# 016-5_spdif-simple_main_revb_sch-pcb.net
KiCad netlist of a schematic drawn in EAGLE
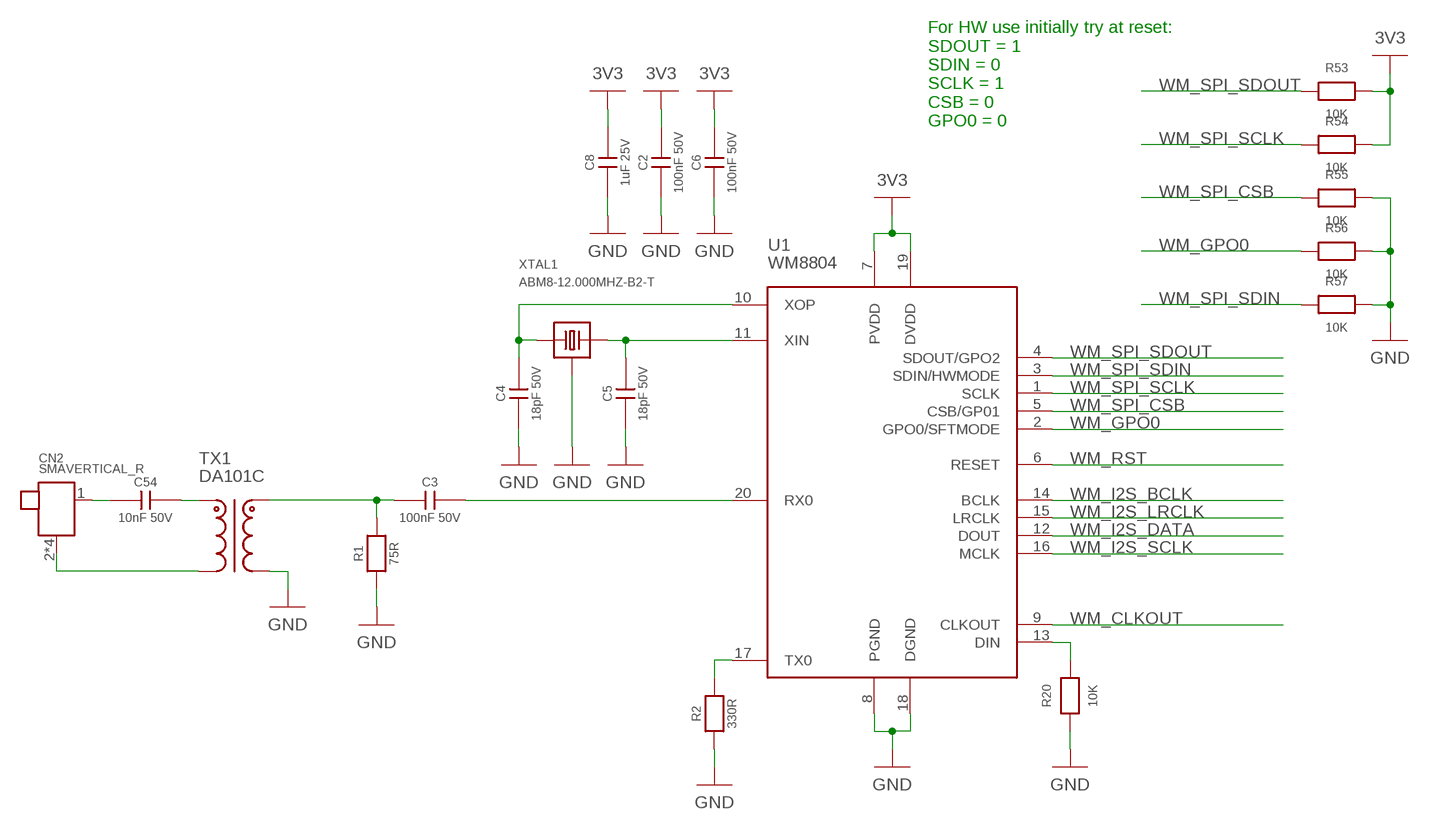
[diagram p0: schematic, sheet 1]
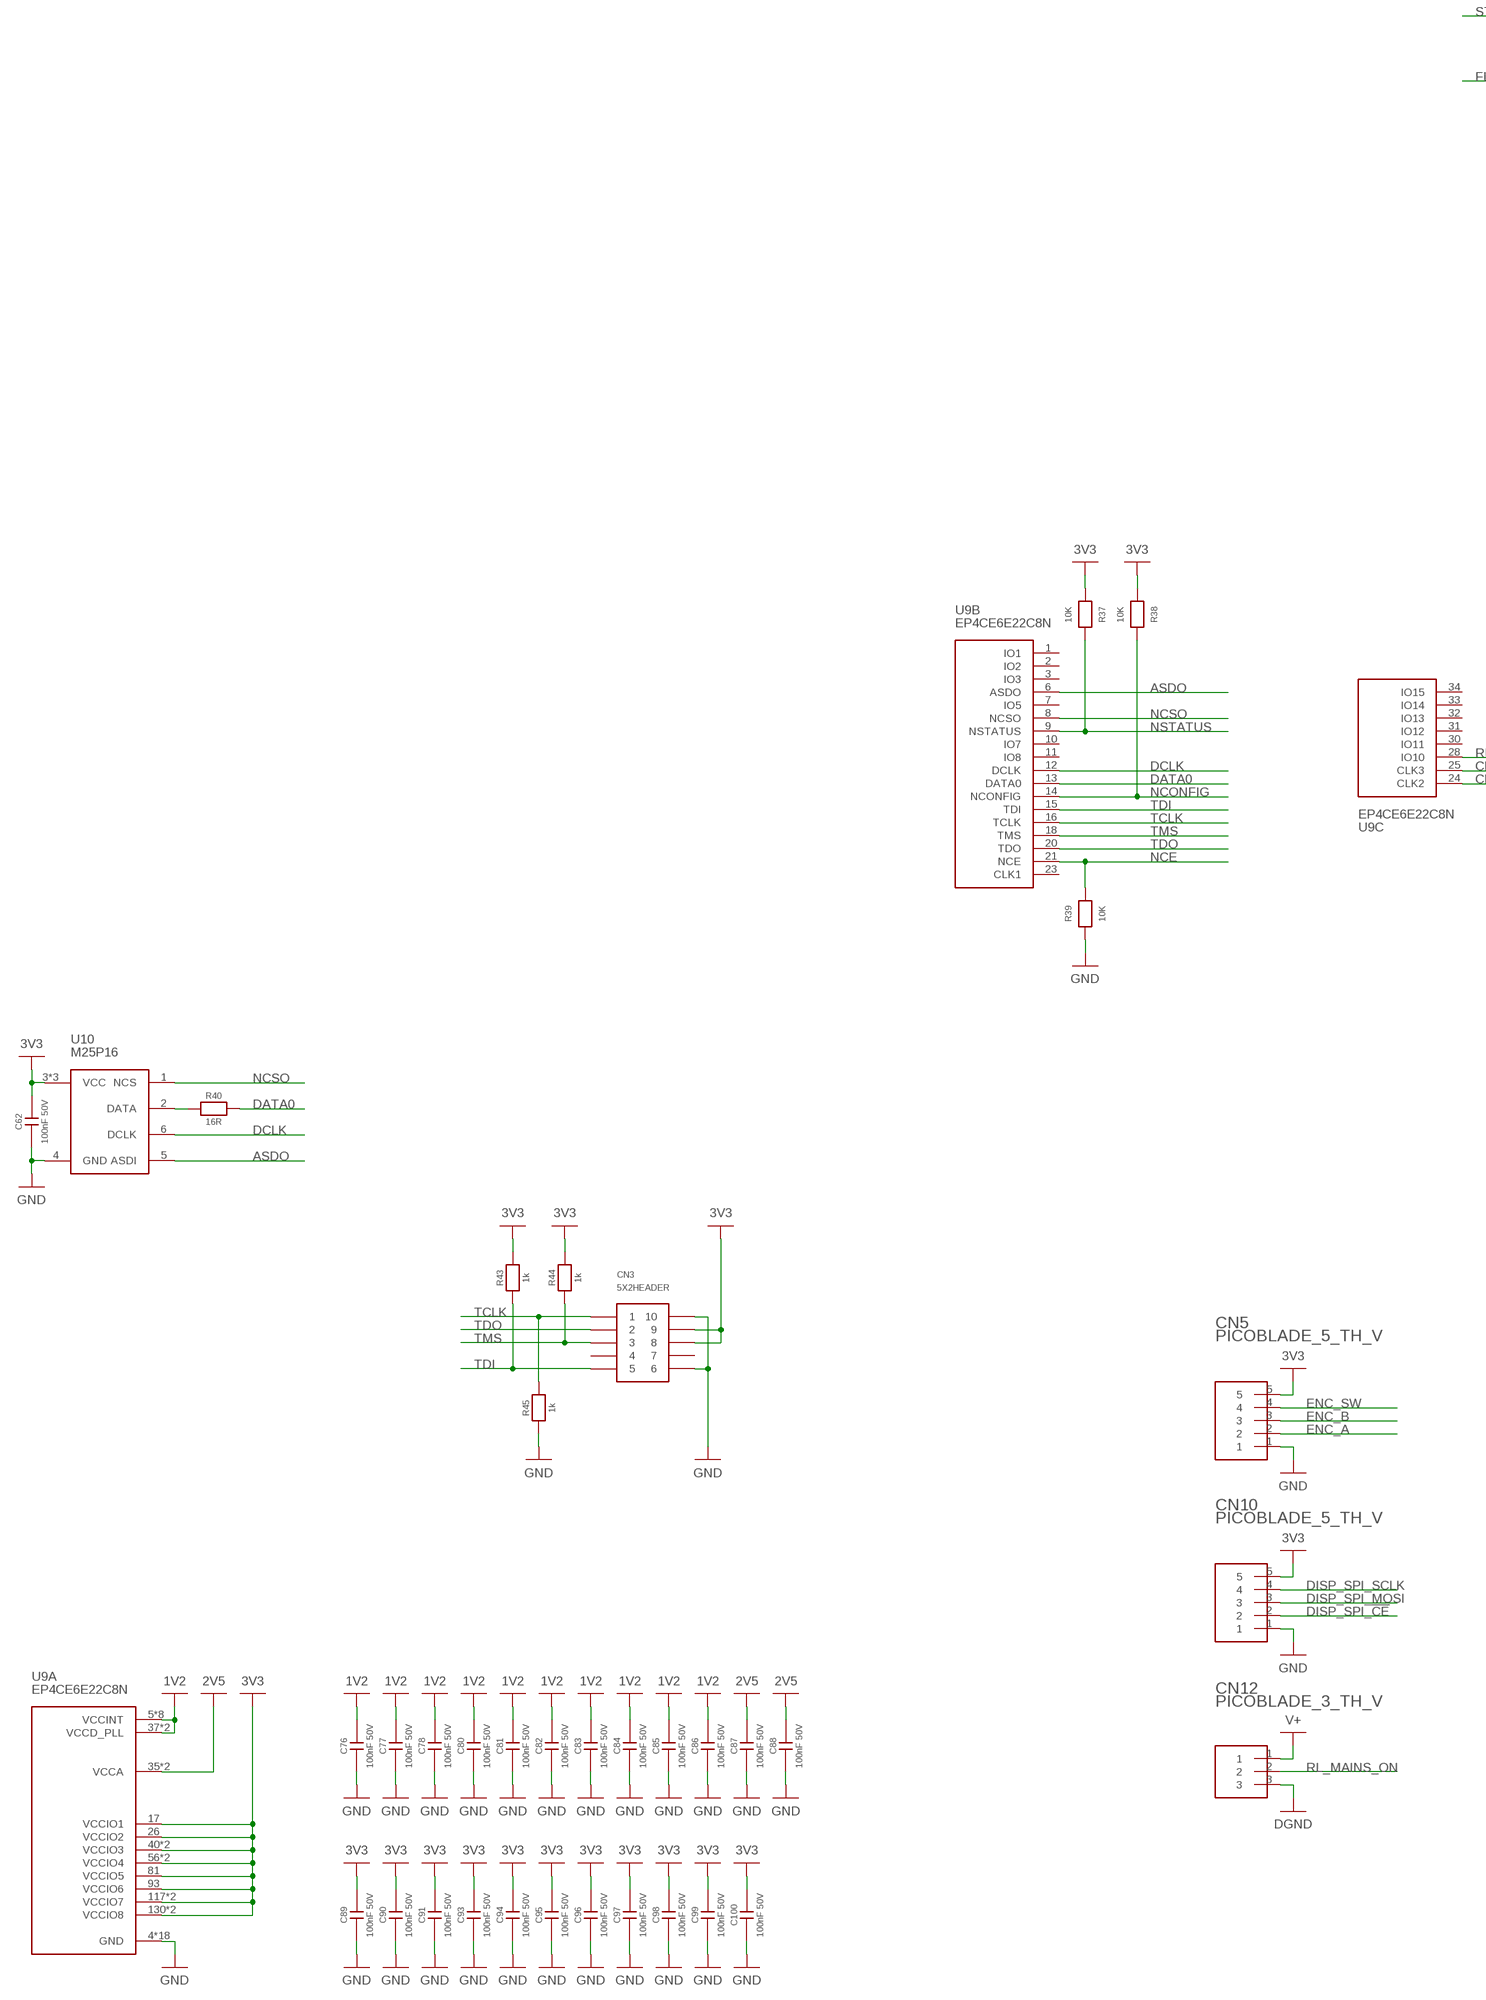
[diagram p1: schematic, sheet 2, part 1 of 2]
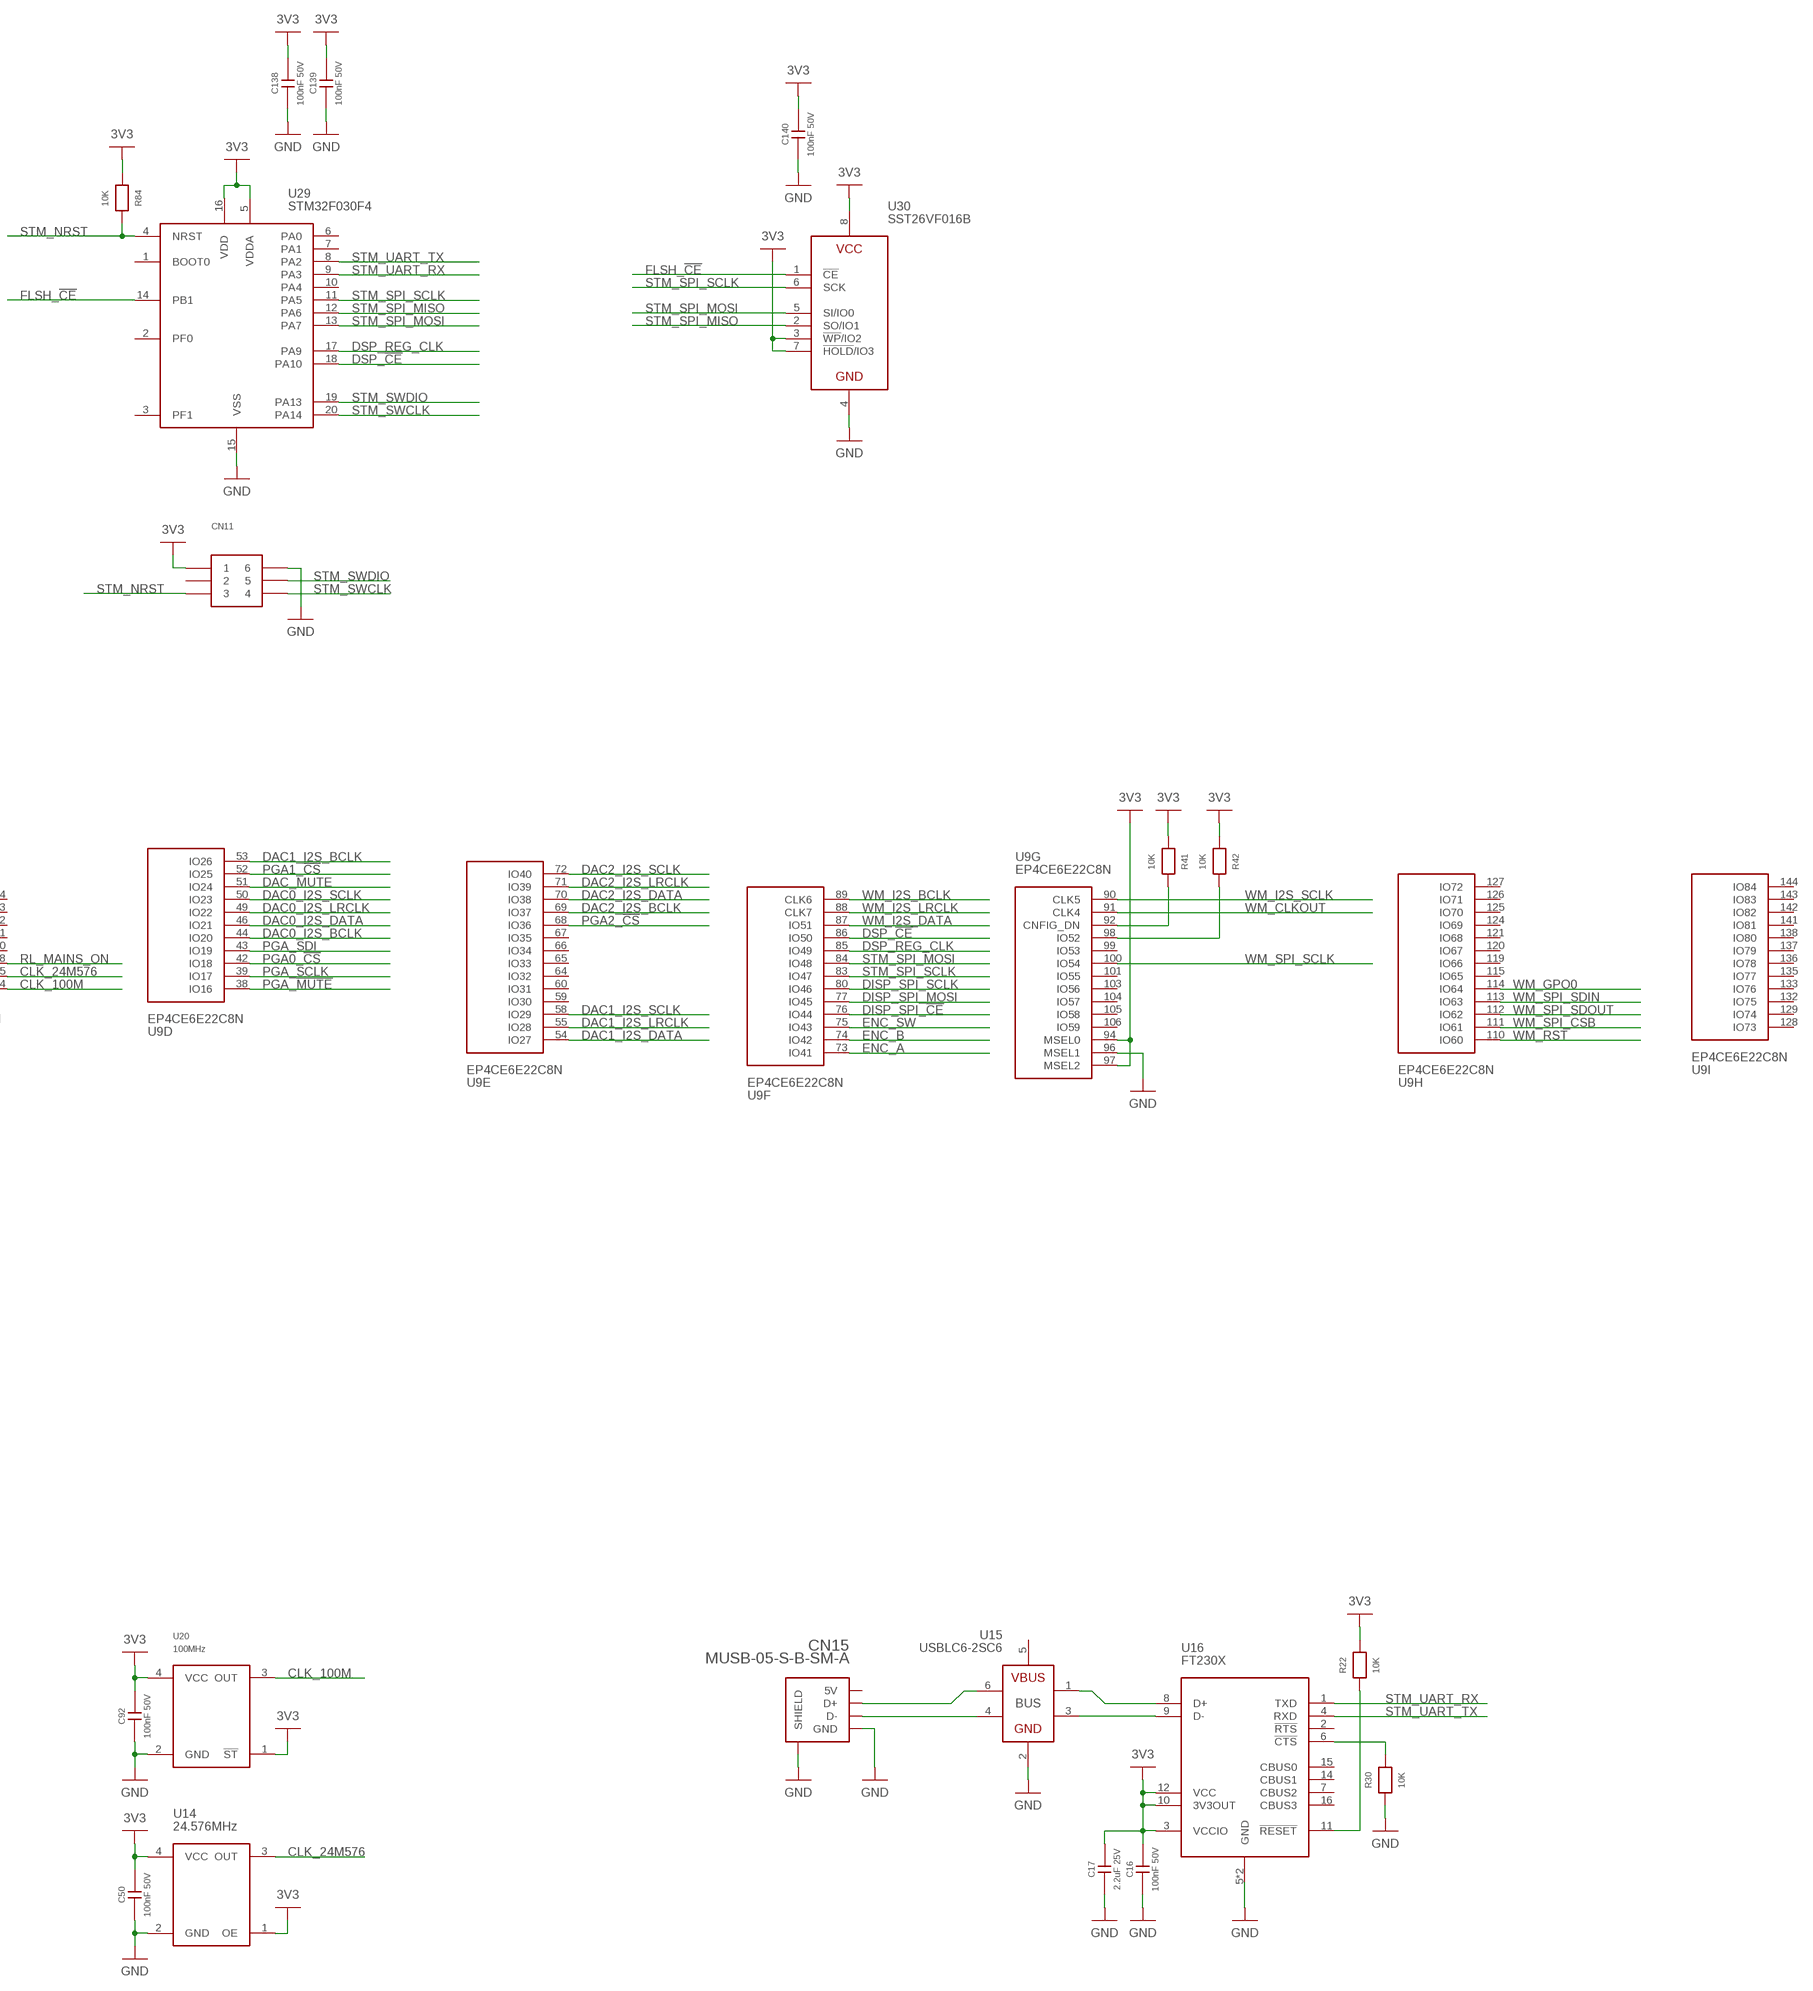
[diagram p2: schematic, sheet 2, part 2 of 2]
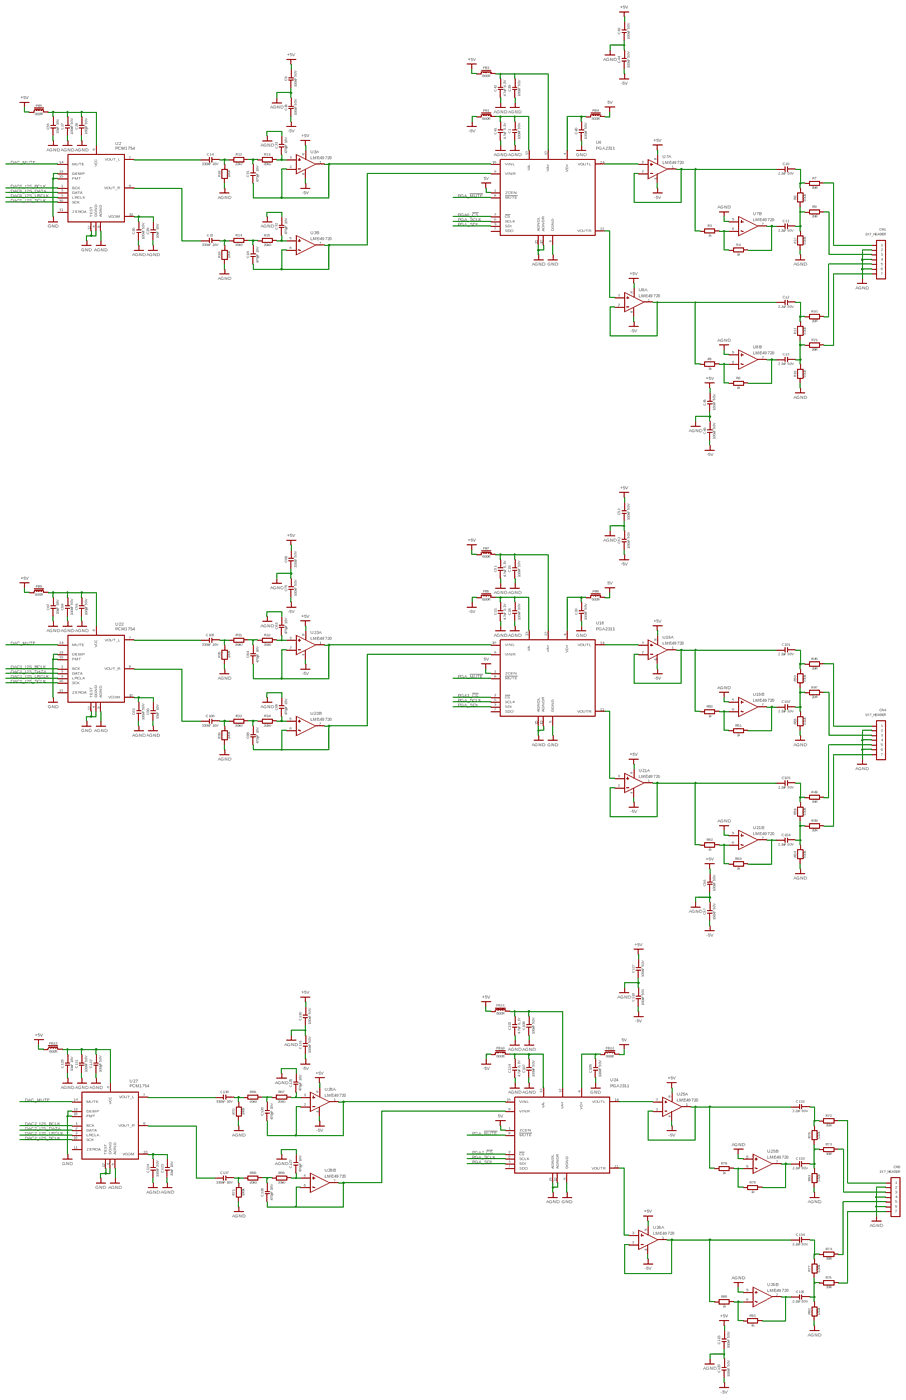
[diagram p3: schematic, sheet 3, overview]
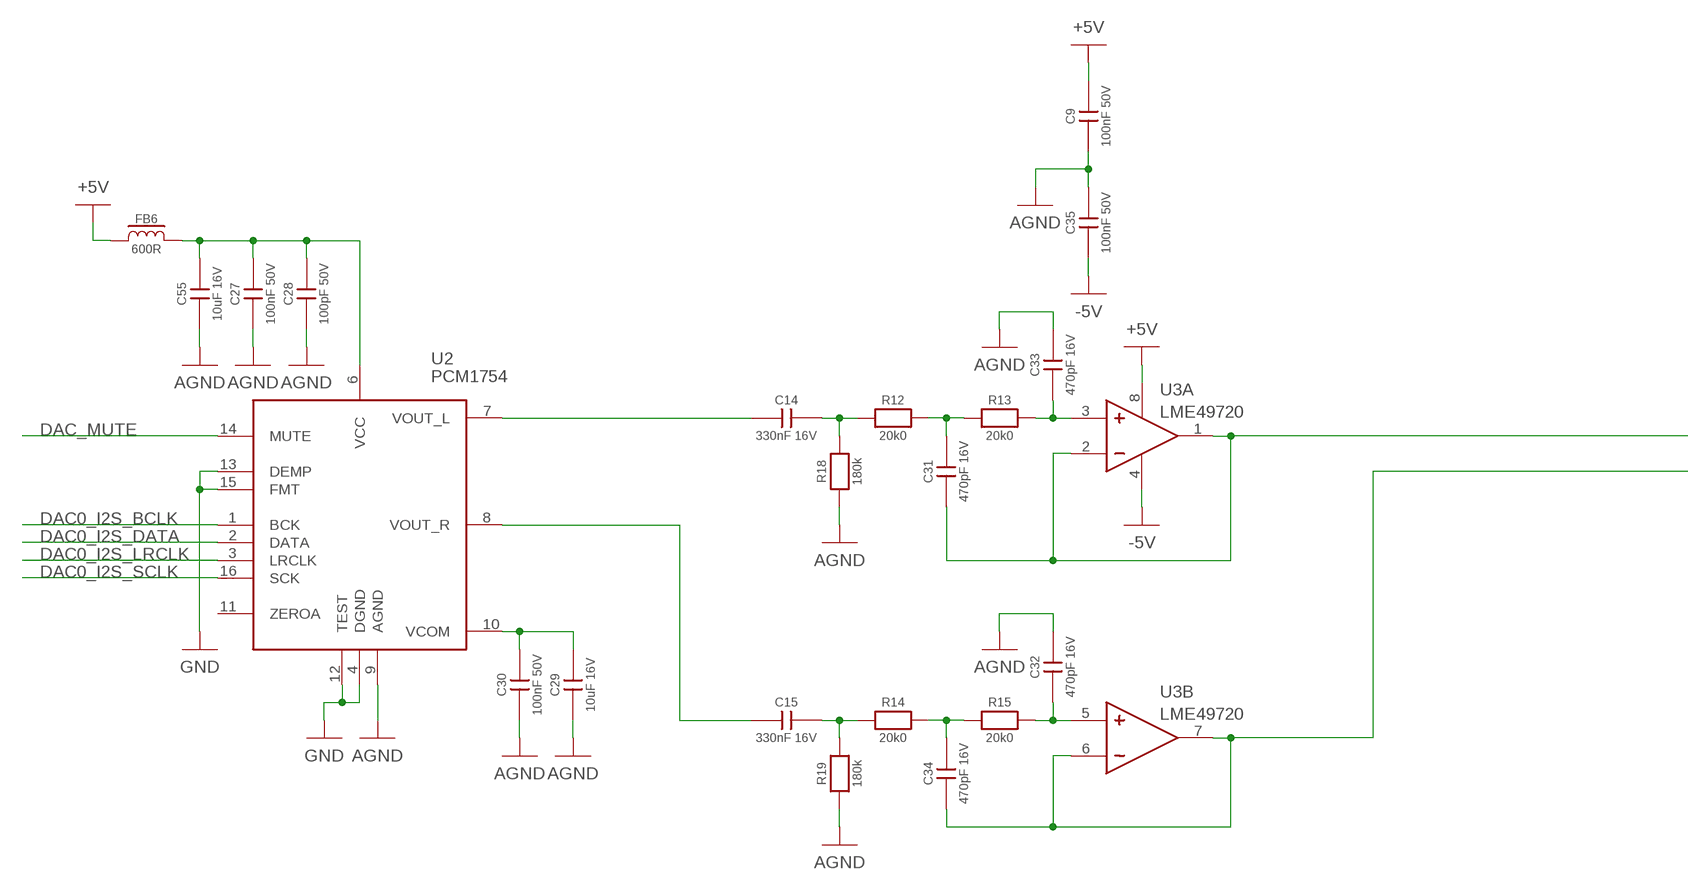
[diagram p4: schematic, sheet 3, part 1 of 4]
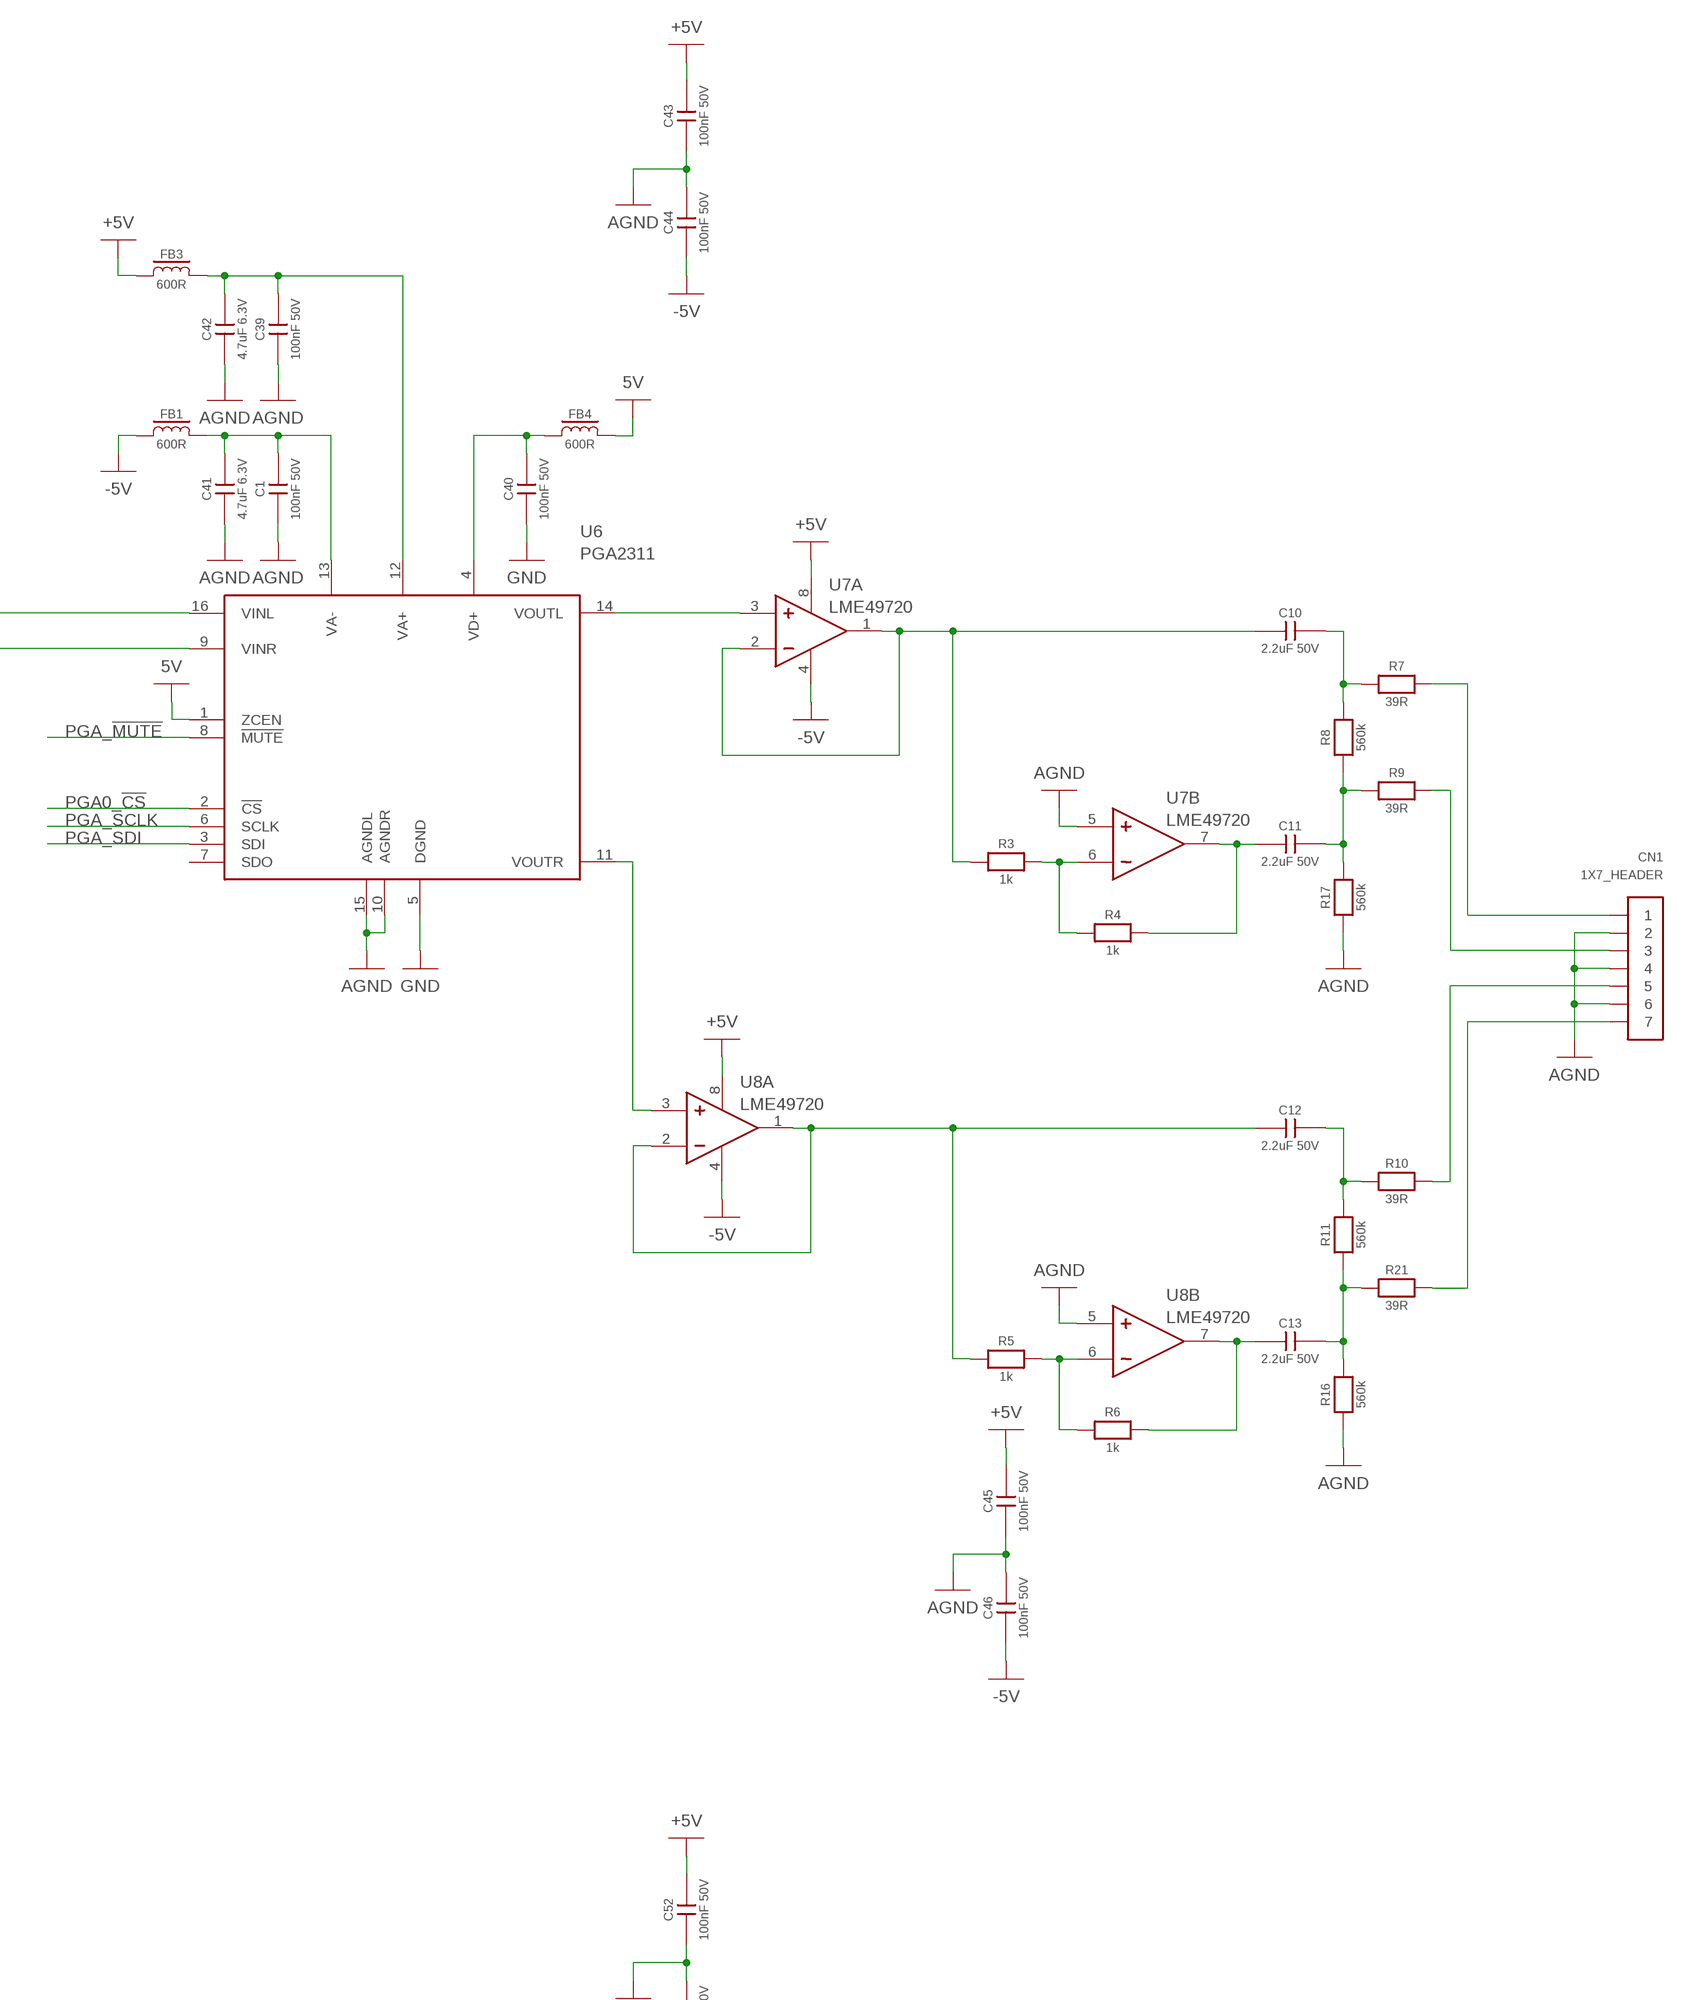
[diagram p5: schematic, sheet 3, part 2 of 4]
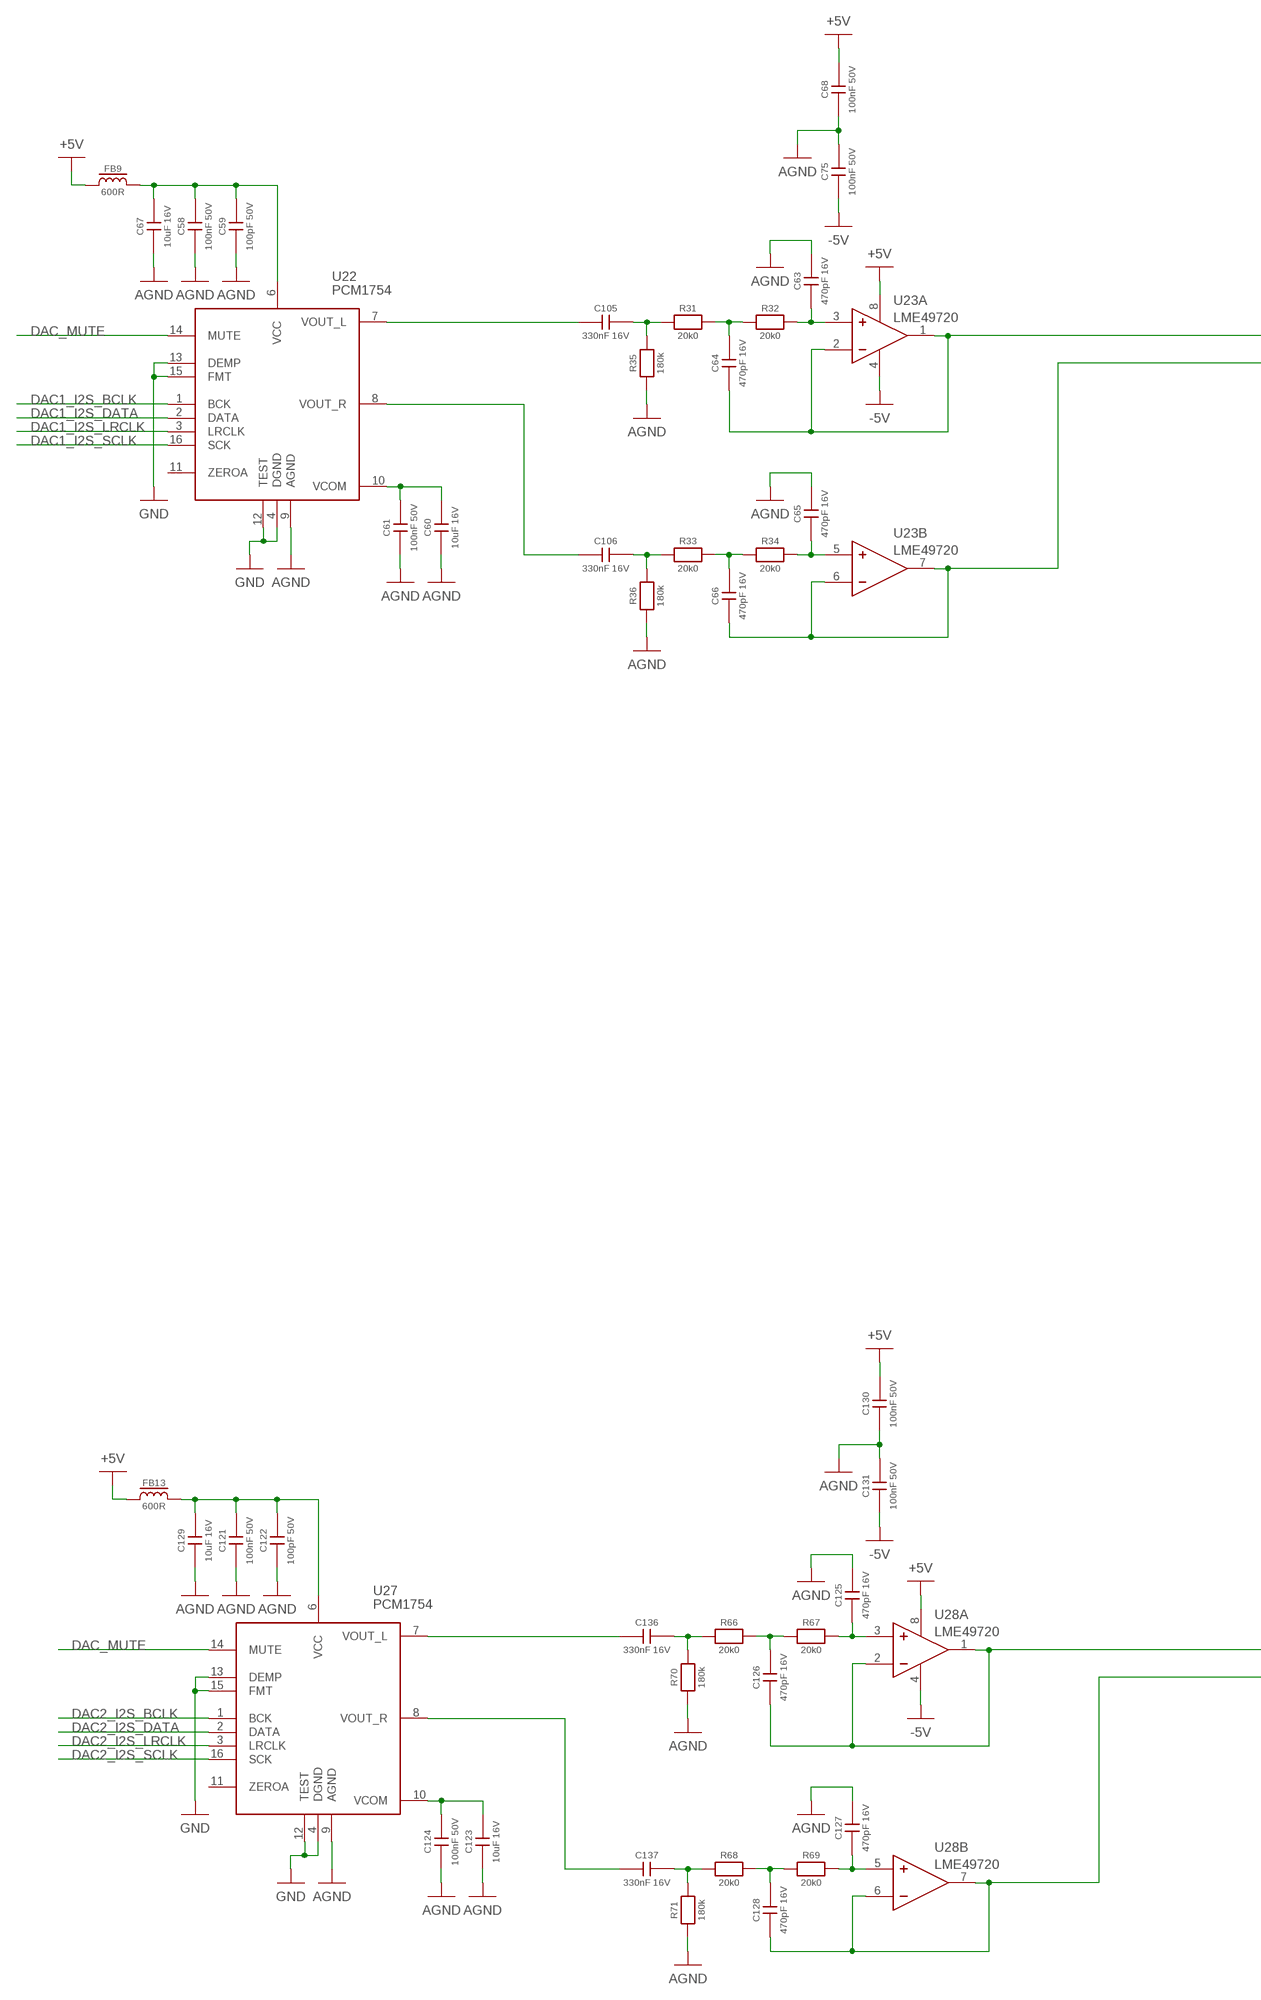
[diagram p6: schematic, sheet 3, part 3 of 4]
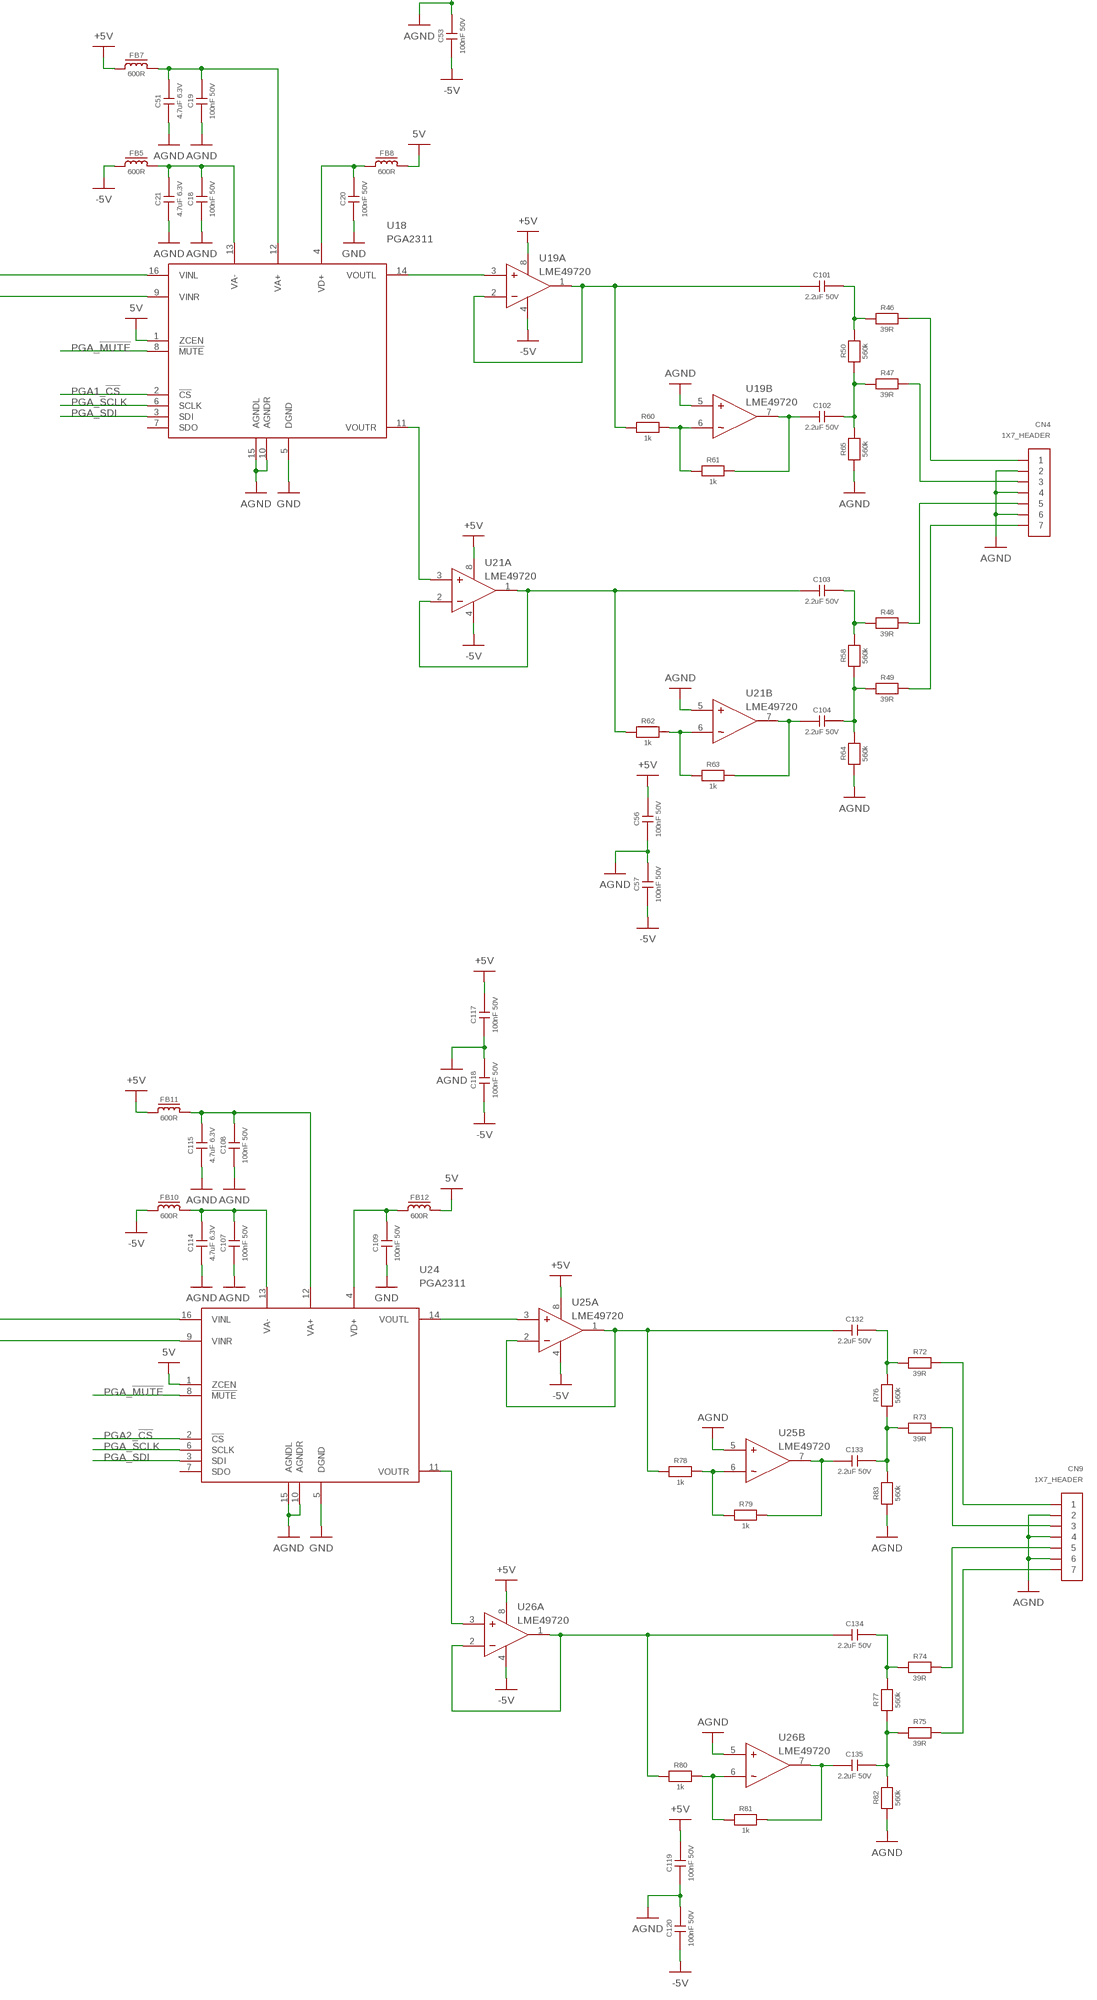
[diagram p7: schematic, sheet 3, part 4 of 4]
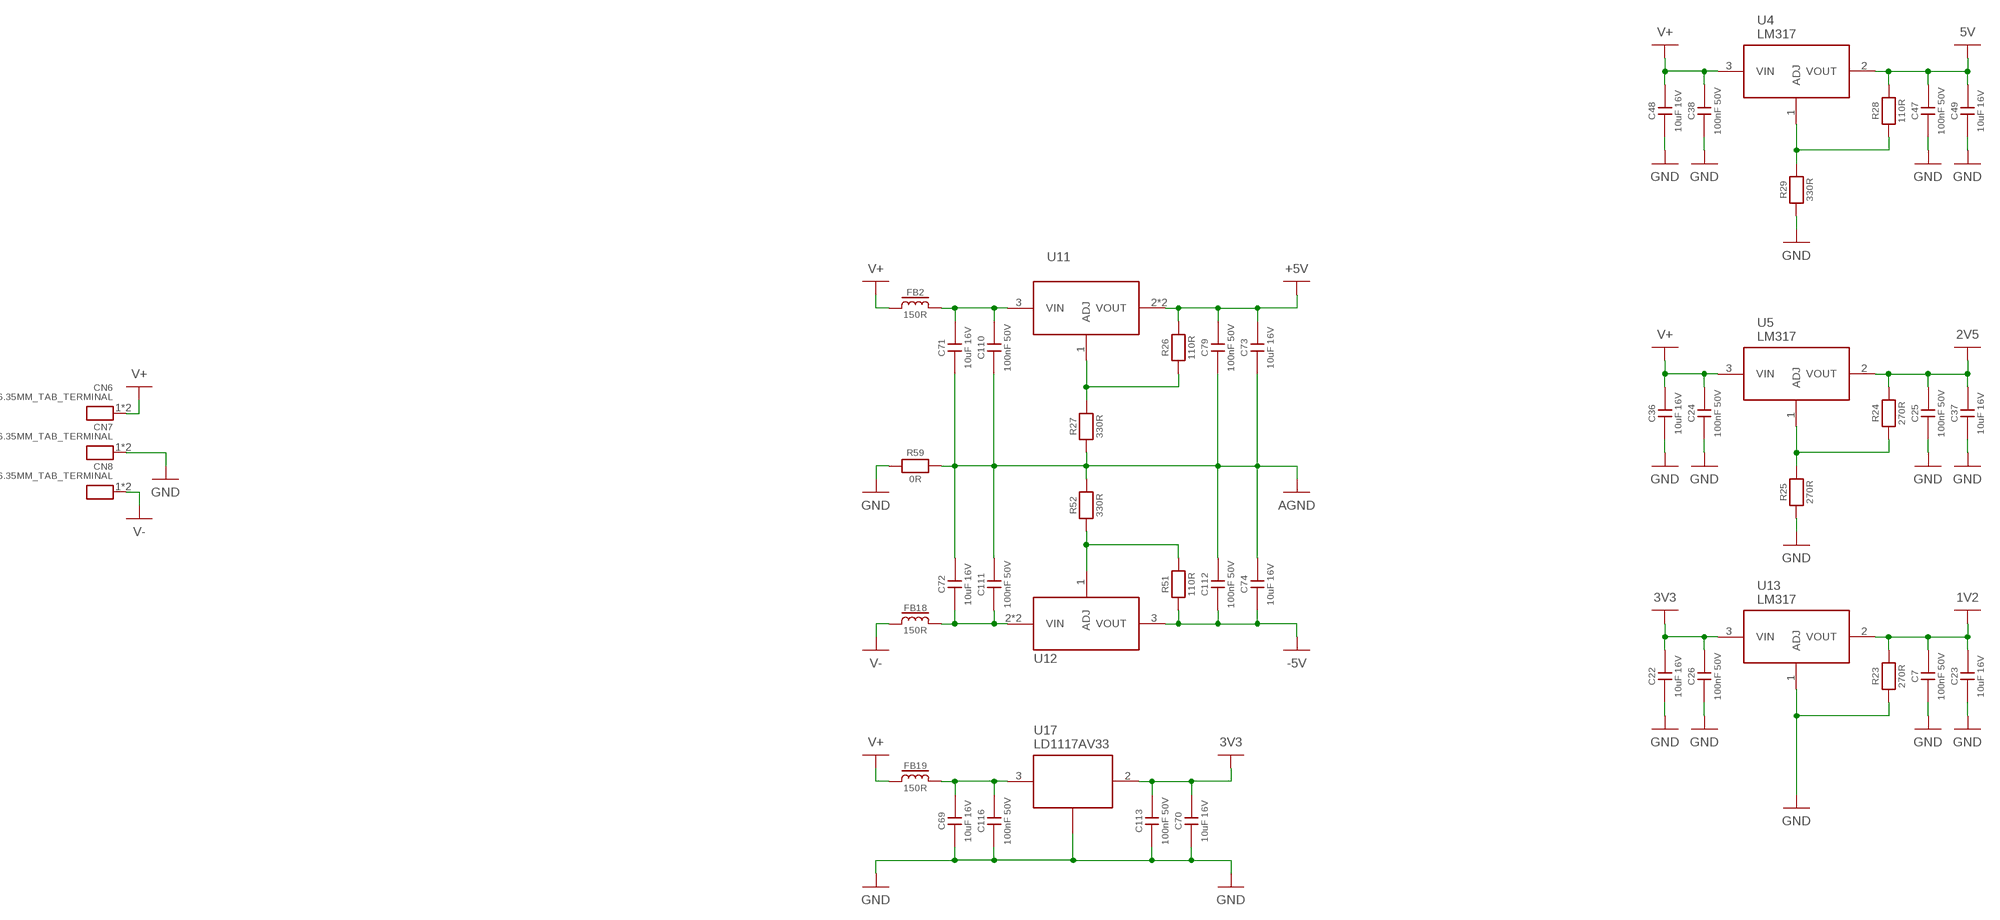
[diagram p8: schematic, sheet 4]
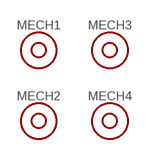
[diagram p9: schematic, sheet 5]

(export (version "E")
  (design (tool "Eeschema 10.0.6"))
  (components
    (comp (ref "C1")
      (value "100nF 50V")
      (footprint "eagle-import:0603")
      (libsource (lib "eagle-import") (part "VJ0603Y104KXACW1BC"))
    )
    (comp (ref "C9")
      (value "100nF 50V")
      (footprint "eagle-import:0603")
      (fields (field (name "FARNELL") "2407338") (field (name "PRICE_PER") "0.0085"))
      (libsource (lib "eagle-import") (part "VJ0603Y104KXACW1BC"))
    )
    (comp (ref "C10")
      (value "2.2uF 50V")
      (footprint "eagle-import:5X7.2BOX")
      (libsource (lib "eagle-import") (part "MKS2B042201F00KSSD"))
    )
    (comp (ref "C11")
      (value "2.2uF 50V")
      (footprint "eagle-import:5X7.2BOX")
      (libsource (lib "eagle-import") (part "MKS2B042201F00KSSD"))
    )
    (comp (ref "C12")
      (value "2.2uF 50V")
      (footprint "eagle-import:5X7.2BOX")
      (libsource (lib "eagle-import") (part "MKS2B042201F00KSSD"))
    )
    (comp (ref "C13")
      (value "2.2uF 50V")
      (footprint "eagle-import:5X7.2BOX")
      (libsource (lib "eagle-import") (part "MKS2B042201F00KSSD"))
    )
    (comp (ref "C14")
      (value "330nF 16V")
      (footprint "eagle-import:1206")
      (libsource (lib "eagle-import") (part "ECPU1C334MA5"))
    )
    (comp (ref "C15")
      (value "330nF 16V")
      (footprint "eagle-import:1206")
      (libsource (lib "eagle-import") (part "ECPU1C334MA5"))
    )
    (comp (ref "C18")
      (value "100nF 50V")
      (footprint "eagle-import:0603")
      (libsource (lib "eagle-import") (part "VJ0603Y104KXACW1BC"))
    )
    (comp (ref "C19")
      (value "100nF 50V")
      (footprint "eagle-import:0603")
      (libsource (lib "eagle-import") (part "VJ0603Y104KXACW1BC"))
    )
    (comp (ref "C20")
      (value "100nF 50V")
      (footprint "eagle-import:0603")
      (libsource (lib "eagle-import") (part "VJ0603Y104KXACW1BC"))
    )
    (comp (ref "C21")
      (value "4.7uF 6.3V")
      (footprint "eagle-import:0603")
      (libsource (lib "eagle-import") (part "GRM188R60J475ME19D"))
    )
    (comp (ref "C27")
      (value "100nF 50V")
      (footprint "eagle-import:0603")
      (libsource (lib "eagle-import") (part "VJ0603Y104KXACW1BC"))
    )
    (comp (ref "C28")
      (value "100pF 50V")
      (footprint "eagle-import:0603")
      (libsource (lib "eagle-import") (part "C0603C101K5GACTU"))
    )
    (comp (ref "C29")
      (value "10uF 16V")
      (footprint "eagle-import:1206")
      (libsource (lib "eagle-import") (part "MC1206B106K160CT"))
    )
    (comp (ref "C30")
      (value "100nF 50V")
      (footprint "eagle-import:0603")
      (libsource (lib "eagle-import") (part "VJ0603Y104KXACW1BC"))
    )
    (comp (ref "C31")
      (value "470pF 16V")
      (footprint "eagle-import:0603")
      (libsource (lib "eagle-import") (part "ECHU1C471GX5"))
    )
    (comp (ref "C32")
      (value "470pF 16V")
      (footprint "eagle-import:0603")
      (libsource (lib "eagle-import") (part "ECHU1C471GX5"))
    )
    (comp (ref "C33")
      (value "470pF 16V")
      (footprint "eagle-import:0603")
      (libsource (lib "eagle-import") (part "ECHU1C471GX5"))
    )
    (comp (ref "C34")
      (value "470pF 16V")
      (footprint "eagle-import:0603")
      (libsource (lib "eagle-import") (part "ECHU1C471GX5"))
    )
    (comp (ref "C35")
      (value "100nF 50V")
      (footprint "eagle-import:0603")
      (fields (field (name "FARNELL") "2407338") (field (name "PRICE_PER") "0.0085"))
      (libsource (lib "eagle-import") (part "VJ0603Y104KXACW1BC"))
    )
    (comp (ref "C39")
      (value "100nF 50V")
      (footprint "eagle-import:0603")
      (libsource (lib "eagle-import") (part "VJ0603Y104KXACW1BC"))
    )
    (comp (ref "C40")
      (value "100nF 50V")
      (footprint "eagle-import:0603")
      (libsource (lib "eagle-import") (part "VJ0603Y104KXACW1BC"))
    )
    (comp (ref "C41")
      (value "4.7uF 6.3V")
      (footprint "eagle-import:0603")
      (libsource (lib "eagle-import") (part "GRM188R60J475ME19D"))
    )
    (comp (ref "C42")
      (value "4.7uF 6.3V")
      (footprint "eagle-import:0603")
      (libsource (lib "eagle-import") (part "GRM188R60J475ME19D"))
    )
    (comp (ref "C43")
      (value "100nF 50V")
      (footprint "eagle-import:0603")
      (fields (field (name "FARNELL") "2407338") (field (name "PRICE_PER") "0.0085"))
      (libsource (lib "eagle-import") (part "VJ0603Y104KXACW1BC"))
    )
    (comp (ref "C44")
      (value "100nF 50V")
      (footprint "eagle-import:0603")
      (fields (field (name "FARNELL") "2407338") (field (name "PRICE_PER") "0.0085"))
      (libsource (lib "eagle-import") (part "VJ0603Y104KXACW1BC"))
    )
    (comp (ref "C45")
      (value "100nF 50V")
      (footprint "eagle-import:0603")
      (fields (field (name "FARNELL") "2407338") (field (name "PRICE_PER") "0.0085"))
      (libsource (lib "eagle-import") (part "VJ0603Y104KXACW1BC"))
    )
    (comp (ref "C46")
      (value "100nF 50V")
      (footprint "eagle-import:0603")
      (fields (field (name "FARNELL") "2407338") (field (name "PRICE_PER") "0.0085"))
      (libsource (lib "eagle-import") (part "VJ0603Y104KXACW1BC"))
    )
    (comp (ref "C51")
      (value "4.7uF 6.3V")
      (footprint "eagle-import:0603")
      (libsource (lib "eagle-import") (part "GRM188R60J475ME19D"))
    )
    (comp (ref "C52")
      (value "100nF 50V")
      (footprint "eagle-import:0603")
      (fields (field (name "FARNELL") "2407338") (field (name "PRICE_PER") "0.0085"))
      (libsource (lib "eagle-import") (part "VJ0603Y104KXACW1BC"))
    )
    (comp (ref "C53")
      (value "100nF 50V")
      (footprint "eagle-import:0603")
      (fields (field (name "FARNELL") "2407338") (field (name "PRICE_PER") "0.0085"))
      (libsource (lib "eagle-import") (part "VJ0603Y104KXACW1BC"))
    )
    (comp (ref "C55")
      (value "10uF 16V")
      (footprint "eagle-import:1206")
      (libsource (lib "eagle-import") (part "MC1206B106K160CT"))
    )
    (comp (ref "C56")
      (value "100nF 50V")
      (footprint "eagle-import:0603")
      (fields (field (name "FARNELL") "2407338") (field (name "PRICE_PER") "0.0085"))
      (libsource (lib "eagle-import") (part "VJ0603Y104KXACW1BC"))
    )
    (comp (ref "C57")
      (value "100nF 50V")
      (footprint "eagle-import:0603")
      (fields (field (name "FARNELL") "2407338") (field (name "PRICE_PER") "0.0085"))
      (libsource (lib "eagle-import") (part "VJ0603Y104KXACW1BC"))
    )
    (comp (ref "C58")
      (value "100nF 50V")
      (footprint "eagle-import:0603")
      (libsource (lib "eagle-import") (part "VJ0603Y104KXACW1BC"))
    )
    (comp (ref "C59")
      (value "100pF 50V")
      (footprint "eagle-import:0603")
      (libsource (lib "eagle-import") (part "C0603C101K5GACTU"))
    )
    (comp (ref "C60")
      (value "10uF 16V")
      (footprint "eagle-import:1206")
      (libsource (lib "eagle-import") (part "MC1206B106K160CT"))
    )
    (comp (ref "C61")
      (value "100nF 50V")
      (footprint "eagle-import:0603")
      (libsource (lib "eagle-import") (part "VJ0603Y104KXACW1BC"))
    )
    (comp (ref "C63")
      (value "470pF 16V")
      (footprint "eagle-import:0603")
      (libsource (lib "eagle-import") (part "ECHU1C471GX5"))
    )
    (comp (ref "C64")
      (value "470pF 16V")
      (footprint "eagle-import:0603")
      (libsource (lib "eagle-import") (part "ECHU1C471GX5"))
    )
    (comp (ref "C65")
      (value "470pF 16V")
      (footprint "eagle-import:0603")
      (libsource (lib "eagle-import") (part "ECHU1C471GX5"))
    )
    (comp (ref "C66")
      (value "470pF 16V")
      (footprint "eagle-import:0603")
      (libsource (lib "eagle-import") (part "ECHU1C471GX5"))
    )
    (comp (ref "C67")
      (value "10uF 16V")
      (footprint "eagle-import:1206")
      (libsource (lib "eagle-import") (part "MC1206B106K160CT"))
    )
    (comp (ref "C68")
      (value "100nF 50V")
      (footprint "eagle-import:0603")
      (fields (field (name "FARNELL") "2407338") (field (name "PRICE_PER") "0.0085"))
      (libsource (lib "eagle-import") (part "VJ0603Y104KXACW1BC"))
    )
    (comp (ref "C75")
      (value "100nF 50V")
      (footprint "eagle-import:0603")
      (fields (field (name "FARNELL") "2407338") (field (name "PRICE_PER") "0.0085"))
      (libsource (lib "eagle-import") (part "VJ0603Y104KXACW1BC"))
    )
    (comp (ref "C101")
      (value "2.2uF 50V")
      (footprint "eagle-import:5X7.2BOX")
      (libsource (lib "eagle-import") (part "MKS2B042201F00KSSD"))
    )
    (comp (ref "C102")
      (value "2.2uF 50V")
      (footprint "eagle-import:5X7.2BOX")
      (libsource (lib "eagle-import") (part "MKS2B042201F00KSSD"))
    )
    (comp (ref "C103")
      (value "2.2uF 50V")
      (footprint "eagle-import:5X7.2BOX")
      (libsource (lib "eagle-import") (part "MKS2B042201F00KSSD"))
    )
    (comp (ref "C104")
      (value "2.2uF 50V")
      (footprint "eagle-import:5X7.2BOX")
      (libsource (lib "eagle-import") (part "MKS2B042201F00KSSD"))
    )
    (comp (ref "C105")
      (value "330nF 16V")
      (footprint "eagle-import:1206")
      (libsource (lib "eagle-import") (part "ECPU1C334MA5"))
    )
    (comp (ref "C106")
      (value "330nF 16V")
      (footprint "eagle-import:1206")
      (libsource (lib "eagle-import") (part "ECPU1C334MA5"))
    )
    (comp (ref "C107")
      (value "100nF 50V")
      (footprint "eagle-import:0603")
      (libsource (lib "eagle-import") (part "VJ0603Y104KXACW1BC"))
    )
    (comp (ref "C108")
      (value "100nF 50V")
      (footprint "eagle-import:0603")
      (libsource (lib "eagle-import") (part "VJ0603Y104KXACW1BC"))
    )
    (comp (ref "C109")
      (value "100nF 50V")
      (footprint "eagle-import:0603")
      (libsource (lib "eagle-import") (part "VJ0603Y104KXACW1BC"))
    )
    (comp (ref "C114")
      (value "4.7uF 6.3V")
      (footprint "eagle-import:0603")
      (libsource (lib "eagle-import") (part "GRM188R60J475ME19D"))
    )
    (comp (ref "C115")
      (value "4.7uF 6.3V")
      (footprint "eagle-import:0603")
      (libsource (lib "eagle-import") (part "GRM188R60J475ME19D"))
    )
    (comp (ref "C117")
      (value "100nF 50V")
      (footprint "eagle-import:0603")
      (fields (field (name "FARNELL") "2407338") (field (name "PRICE_PER") "0.0085"))
      (libsource (lib "eagle-import") (part "VJ0603Y104KXACW1BC"))
    )
    (comp (ref "C118")
      (value "100nF 50V")
      (footprint "eagle-import:0603")
      (fields (field (name "FARNELL") "2407338") (field (name "PRICE_PER") "0.0085"))
      (libsource (lib "eagle-import") (part "VJ0603Y104KXACW1BC"))
    )
    (comp (ref "C119")
      (value "100nF 50V")
      (footprint "eagle-import:0603")
      (fields (field (name "FARNELL") "2407338") (field (name "PRICE_PER") "0.0085"))
      (libsource (lib "eagle-import") (part "VJ0603Y104KXACW1BC"))
    )
    (comp (ref "C120")
      (value "100nF 50V")
      (footprint "eagle-import:0603")
      (fields (field (name "FARNELL") "2407338") (field (name "PRICE_PER") "0.0085"))
      (libsource (lib "eagle-import") (part "VJ0603Y104KXACW1BC"))
    )
    (comp (ref "C121")
      (value "100nF 50V")
      (footprint "eagle-import:0603")
      (libsource (lib "eagle-import") (part "VJ0603Y104KXACW1BC"))
    )
    (comp (ref "C122")
      (value "100pF 50V")
      (footprint "eagle-import:0603")
      (libsource (lib "eagle-import") (part "C0603C101K5GACTU"))
    )
    (comp (ref "C123")
      (value "10uF 16V")
      (footprint "eagle-import:1206")
      (libsource (lib "eagle-import") (part "MC1206B106K160CT"))
    )
    (comp (ref "C124")
      (value "100nF 50V")
      (footprint "eagle-import:0603")
      (libsource (lib "eagle-import") (part "VJ0603Y104KXACW1BC"))
    )
    (comp (ref "C125")
      (value "470pF 16V")
      (footprint "eagle-import:0603")
      (libsource (lib "eagle-import") (part "ECHU1C471GX5"))
    )
    (comp (ref "C126")
      (value "470pF 16V")
      (footprint "eagle-import:0603")
      (libsource (lib "eagle-import") (part "ECHU1C471GX5"))
    )
    (comp (ref "C127")
      (value "470pF 16V")
      (footprint "eagle-import:0603")
      (libsource (lib "eagle-import") (part "ECHU1C471GX5"))
    )
    (comp (ref "C128")
      (value "470pF 16V")
      (footprint "eagle-import:0603")
      (libsource (lib "eagle-import") (part "ECHU1C471GX5"))
    )
    (comp (ref "C129")
      (value "10uF 16V")
      (footprint "eagle-import:1206")
      (libsource (lib "eagle-import") (part "MC1206B106K160CT"))
    )
    (comp (ref "C130")
      (value "100nF 50V")
      (footprint "eagle-import:0603")
      (fields (field (name "FARNELL") "2407338") (field (name "PRICE_PER") "0.0085"))
      (libsource (lib "eagle-import") (part "VJ0603Y104KXACW1BC"))
    )
    (comp (ref "C131")
      (value "100nF 50V")
      (footprint "eagle-import:0603")
      (fields (field (name "FARNELL") "2407338") (field (name "PRICE_PER") "0.0085"))
      (libsource (lib "eagle-import") (part "VJ0603Y104KXACW1BC"))
    )
    (comp (ref "C132")
      (value "2.2uF 50V")
      (footprint "eagle-import:5X7.2BOX")
      (libsource (lib "eagle-import") (part "MKS2B042201F00KSSD"))
    )
    (comp (ref "C133")
      (value "2.2uF 50V")
      (footprint "eagle-import:5X7.2BOX")
      (libsource (lib "eagle-import") (part "MKS2B042201F00KSSD"))
    )
    (comp (ref "C134")
      (value "2.2uF 50V")
      (footprint "eagle-import:5X7.2BOX")
      (libsource (lib "eagle-import") (part "MKS2B042201F00KSSD"))
    )
    (comp (ref "C135")
      (value "2.2uF 50V")
      (footprint "eagle-import:5X7.2BOX")
      (libsource (lib "eagle-import") (part "MKS2B042201F00KSSD"))
    )
    (comp (ref "C136")
      (value "330nF 16V")
      (footprint "eagle-import:1206")
      (libsource (lib "eagle-import") (part "ECPU1C334MA5"))
    )
    (comp (ref "C137")
      (value "330nF 16V")
      (footprint "eagle-import:1206")
      (libsource (lib "eagle-import") (part "ECPU1C334MA5"))
    )
    (comp (ref "CN1")
      (value "1X7_HEADER")
      (footprint "eagle-import:7PIN_HEADER")
      (libsource (lib "eagle-import") (part "1X7_HEADER"))
    )
    (comp (ref "CN4")
      (value "1X7_HEADER")
      (footprint "eagle-import:7PIN_HEADER")
      (libsource (lib "eagle-import") (part "1X7_HEADER"))
    )
    (comp (ref "CN9")
      (value "1X7_HEADER")
      (footprint "eagle-import:7PIN_HEADER")
      (libsource (lib "eagle-import") (part "1X7_HEADER"))
    )
    (comp (ref "FB1")
      (value "600R")
      (footprint "eagle-import:0603")
      (libsource (lib "eagle-import") (part "742792651"))
    )
    (comp (ref "FB3")
      (value "600R")
      (footprint "eagle-import:0603")
      (libsource (lib "eagle-import") (part "742792651"))
    )
    (comp (ref "FB4")
      (value "600R")
      (footprint "eagle-import:0603")
      (fields (field (name "FARNELL") "1635706"))
      (libsource (lib "eagle-import") (part "742792651"))
    )
    (comp (ref "FB5")
      (value "600R")
      (footprint "eagle-import:0603")
      (libsource (lib "eagle-import") (part "742792651"))
    )
    (comp (ref "FB6")
      (value "600R")
      (footprint "eagle-import:0603")
      (libsource (lib "eagle-import") (part "742792651"))
    )
    (comp (ref "FB7")
      (value "600R")
      (footprint "eagle-import:0603")
      (libsource (lib "eagle-import") (part "742792651"))
    )
    (comp (ref "FB8")
      (value "600R")
      (footprint "eagle-import:0603")
      (fields (field (name "FARNELL") "1635706"))
      (libsource (lib "eagle-import") (part "742792651"))
    )
    (comp (ref "FB9")
      (value "600R")
      (footprint "eagle-import:0603")
      (libsource (lib "eagle-import") (part "742792651"))
    )
    (comp (ref "FB10")
      (value "600R")
      (footprint "eagle-import:0603")
      (libsource (lib "eagle-import") (part "742792651"))
    )
    (comp (ref "FB11")
      (value "600R")
      (footprint "eagle-import:0603")
      (libsource (lib "eagle-import") (part "742792651"))
    )
    (comp (ref "FB12")
      (value "600R")
      (footprint "eagle-import:0603")
      (fields (field (name "FARNELL") "1635706"))
      (libsource (lib "eagle-import") (part "742792651"))
    )
    (comp (ref "FB13")
      (value "600R")
      (footprint "eagle-import:0603")
      (libsource (lib "eagle-import") (part "742792651"))
    )
    (comp (ref "R3")
      (value "1k")
      (footprint "eagle-import:0603")
      (libsource (lib "eagle-import") (part "CRCW06031K00FKEA"))
    )
    (comp (ref "R4")
      (value "1k")
      (footprint "eagle-import:0603")
      (libsource (lib "eagle-import") (part "CRCW06031K00FKEA"))
    )
    (comp (ref "R5")
      (value "1k")
      (footprint "eagle-import:0603")
      (libsource (lib "eagle-import") (part "CRCW06031K00FKEA"))
    )
    (comp (ref "R6")
      (value "1k")
      (footprint "eagle-import:0603")
      (libsource (lib "eagle-import") (part "CRCW06031K00FKEA"))
    )
    (comp (ref "R7")
      (value "39R")
      (footprint "eagle-import:0603")
      (libsource (lib "eagle-import") (part "CRCW060339R0FKEA"))
    )
    (comp (ref "R8")
      (value "560k")
      (footprint "eagle-import:0603")
      (libsource (lib "eagle-import") (part "CRCW0603560KFKEA"))
    )
    (comp (ref "R9")
      (value "39R")
      (footprint "eagle-import:0603")
      (libsource (lib "eagle-import") (part "CRCW060339R0FKEA"))
    )
    (comp (ref "R10")
      (value "39R")
      (footprint "eagle-import:0603")
      (libsource (lib "eagle-import") (part "CRCW060339R0FKEA"))
    )
    (comp (ref "R11")
      (value "560k")
      (footprint "eagle-import:0603")
      (libsource (lib "eagle-import") (part "CRCW0603560KFKEA"))
    )
    (comp (ref "R12")
      (value "20k0")
      (footprint "eagle-import:0603")
      (libsource (lib "eagle-import") (part "CRCW060320K0FKEA"))
    )
    (comp (ref "R13")
      (value "20k0")
      (footprint "eagle-import:0603")
      (libsource (lib "eagle-import") (part "CRCW060320K0FKEA"))
    )
    (comp (ref "R14")
      (value "20k0")
      (footprint "eagle-import:0603")
      (libsource (lib "eagle-import") (part "CRCW060320K0FKEA"))
    )
    (comp (ref "R15")
      (value "20k0")
      (footprint "eagle-import:0603")
      (libsource (lib "eagle-import") (part "CRCW060320K0FKEA"))
    )
    (comp (ref "R16")
      (value "560k")
      (footprint "eagle-import:0603")
      (libsource (lib "eagle-import") (part "CRCW0603560KFKEA"))
    )
    (comp (ref "R17")
      (value "560k")
      (footprint "eagle-import:0603")
      (libsource (lib "eagle-import") (part "CRCW0603560KFKEA"))
    )
    (comp (ref "R18")
      (value "180k")
      (footprint "eagle-import:0603")
      (libsource (lib "eagle-import") (part "CRCW0603180KFKEA"))
    )
    (comp (ref "R19")
      (value "180k")
      (footprint "eagle-import:0603")
      (libsource (lib "eagle-import") (part "CRCW0603180KFKEA"))
    )
    (comp (ref "R21")
      (value "39R")
      (footprint "eagle-import:0603")
      (libsource (lib "eagle-import") (part "CRCW060339R0FKEA"))
    )
    (comp (ref "R31")
      (value "20k0")
      (footprint "eagle-import:0603")
      (libsource (lib "eagle-import") (part "CRCW060320K0FKEA"))
    )
    (comp (ref "R32")
      (value "20k0")
      (footprint "eagle-import:0603")
      (libsource (lib "eagle-import") (part "CRCW060320K0FKEA"))
    )
    (comp (ref "R33")
      (value "20k0")
      (footprint "eagle-import:0603")
      (libsource (lib "eagle-import") (part "CRCW060320K0FKEA"))
    )
    (comp (ref "R34")
      (value "20k0")
      (footprint "eagle-import:0603")
      (libsource (lib "eagle-import") (part "CRCW060320K0FKEA"))
    )
    (comp (ref "R35")
      (value "180k")
      (footprint "eagle-import:0603")
      (libsource (lib "eagle-import") (part "CRCW0603180KFKEA"))
    )
    (comp (ref "R36")
      (value "180k")
      (footprint "eagle-import:0603")
      (libsource (lib "eagle-import") (part "CRCW0603180KFKEA"))
    )
    (comp (ref "R46")
      (value "39R")
      (footprint "eagle-import:0603")
      (libsource (lib "eagle-import") (part "CRCW060339R0FKEA"))
    )
    (comp (ref "R47")
      (value "39R")
      (footprint "eagle-import:0603")
      (libsource (lib "eagle-import") (part "CRCW060339R0FKEA"))
    )
    (comp (ref "R48")
      (value "39R")
      (footprint "eagle-import:0603")
      (libsource (lib "eagle-import") (part "CRCW060339R0FKEA"))
    )
    (comp (ref "R49")
      (value "39R")
      (footprint "eagle-import:0603")
      (libsource (lib "eagle-import") (part "CRCW060339R0FKEA"))
    )
    (comp (ref "R50")
      (value "560k")
      (footprint "eagle-import:0603")
      (libsource (lib "eagle-import") (part "CRCW0603560KFKEA"))
    )
    (comp (ref "R58")
      (value "560k")
      (footprint "eagle-import:0603")
      (libsource (lib "eagle-import") (part "CRCW0603560KFKEA"))
    )
    (comp (ref "R60")
      (value "1k")
      (footprint "eagle-import:0603")
      (libsource (lib "eagle-import") (part "CRCW06031K00FKEA"))
    )
    (comp (ref "R61")
      (value "1k")
      (footprint "eagle-import:0603")
      (libsource (lib "eagle-import") (part "CRCW06031K00FKEA"))
    )
    (comp (ref "R62")
      (value "1k")
      (footprint "eagle-import:0603")
      (libsource (lib "eagle-import") (part "CRCW06031K00FKEA"))
    )
    (comp (ref "R63")
      (value "1k")
      (footprint "eagle-import:0603")
      (libsource (lib "eagle-import") (part "CRCW06031K00FKEA"))
    )
    (comp (ref "R64")
      (value "560k")
      (footprint "eagle-import:0603")
      (libsource (lib "eagle-import") (part "CRCW0603560KFKEA"))
    )
    (comp (ref "R65")
      (value "560k")
      (footprint "eagle-import:0603")
      (libsource (lib "eagle-import") (part "CRCW0603560KFKEA"))
    )
    (comp (ref "R66")
      (value "20k0")
      (footprint "eagle-import:0603")
      (libsource (lib "eagle-import") (part "CRCW060320K0FKEA"))
    )
    (comp (ref "R67")
      (value "20k0")
      (footprint "eagle-import:0603")
      (libsource (lib "eagle-import") (part "CRCW060320K0FKEA"))
    )
    (comp (ref "R68")
      (value "20k0")
      (footprint "eagle-import:0603")
      (libsource (lib "eagle-import") (part "CRCW060320K0FKEA"))
    )
    (comp (ref "R69")
      (value "20k0")
      (footprint "eagle-import:0603")
      (libsource (lib "eagle-import") (part "CRCW060320K0FKEA"))
    )
    (comp (ref "R70")
      (value "180k")
      (footprint "eagle-import:0603")
      (libsource (lib "eagle-import") (part "CRCW0603180KFKEA"))
    )
    (comp (ref "R71")
      (value "180k")
      (footprint "eagle-import:0603")
      (libsource (lib "eagle-import") (part "CRCW0603180KFKEA"))
    )
    (comp (ref "R72")
      (value "39R")
      (footprint "eagle-import:0603")
      (libsource (lib "eagle-import") (part "CRCW060339R0FKEA"))
    )
    (comp (ref "R73")
      (value "39R")
      (footprint "eagle-import:0603")
      (libsource (lib "eagle-import") (part "CRCW060339R0FKEA"))
    )
    (comp (ref "R74")
      (value "39R")
      (footprint "eagle-import:0603")
      (libsource (lib "eagle-import") (part "CRCW060339R0FKEA"))
    )
    (comp (ref "R75")
      (value "39R")
      (footprint "eagle-import:0603")
      (libsource (lib "eagle-import") (part "CRCW060339R0FKEA"))
    )
    (comp (ref "R76")
      (value "560k")
      (footprint "eagle-import:0603")
      (libsource (lib "eagle-import") (part "CRCW0603560KFKEA"))
    )
    (comp (ref "R77")
      (value "560k")
      (footprint "eagle-import:0603")
      (libsource (lib "eagle-import") (part "CRCW0603560KFKEA"))
    )
    (comp (ref "R78")
      (value "1k")
      (footprint "eagle-import:0603")
      (libsource (lib "eagle-import") (part "CRCW06031K00FKEA"))
    )
    (comp (ref "R79")
      (value "1k")
      (footprint "eagle-import:0603")
      (libsource (lib "eagle-import") (part "CRCW06031K00FKEA"))
    )
    (comp (ref "R80")
      (value "1k")
      (footprint "eagle-import:0603")
      (libsource (lib "eagle-import") (part "CRCW06031K00FKEA"))
    )
    (comp (ref "R81")
      (value "1k")
      (footprint "eagle-import:0603")
      (libsource (lib "eagle-import") (part "CRCW06031K00FKEA"))
    )
    (comp (ref "R82")
      (value "560k")
      (footprint "eagle-import:0603")
      (libsource (lib "eagle-import") (part "CRCW0603560KFKEA"))
    )
    (comp (ref "R83")
      (value "560k")
      (footprint "eagle-import:0603")
      (libsource (lib "eagle-import") (part "CRCW0603560KFKEA"))
    )
    (comp (ref "U2")
      (value "PCM1754")
      (footprint "eagle-import:SSOP16-4MM@1")
      (libsource (lib "eagle-import") (part "PCM1754"))
    )
    (comp (ref "U3")
      (value "LME49720")
      (footprint "eagle-import:SO8")
      (libsource (lib "eagle-import") (part "LME49720MA/NOPB"))
    )
    (comp (ref "U6")
      (value "PGA2311")
      (footprint "eagle-import:SOL16")
      (libsource (lib "eagle-import") (part "PGA2311UA"))
    )
    (comp (ref "U7")
      (value "LME49720")
      (footprint "eagle-import:SO8")
      (libsource (lib "eagle-import") (part "LME49720MA/NOPB"))
    )
    (comp (ref "U8")
      (value "LME49720")
      (footprint "eagle-import:SO8")
      (libsource (lib "eagle-import") (part "LME49720MA/NOPB"))
    )
    (comp (ref "U18")
      (value "PGA2311")
      (footprint "eagle-import:SOL16")
      (libsource (lib "eagle-import") (part "PGA2311UA"))
    )
    (comp (ref "U19")
      (value "LME49720")
      (footprint "eagle-import:SO8")
      (libsource (lib "eagle-import") (part "LME49720MA/NOPB"))
    )
    (comp (ref "U21")
      (value "LME49720")
      (footprint "eagle-import:SO8")
      (libsource (lib "eagle-import") (part "LME49720MA/NOPB"))
    )
    (comp (ref "U22")
      (value "PCM1754")
      (footprint "eagle-import:SSOP16-4MM@1")
      (libsource (lib "eagle-import") (part "PCM1754"))
    )
    (comp (ref "U23")
      (value "LME49720")
      (footprint "eagle-import:SO8")
      (libsource (lib "eagle-import") (part "LME49720MA/NOPB"))
    )
    (comp (ref "U24")
      (value "PGA2311")
      (footprint "eagle-import:SOL16")
      (libsource (lib "eagle-import") (part "PGA2311UA"))
    )
    (comp (ref "U25")
      (value "LME49720")
      (footprint "eagle-import:SO8")
      (libsource (lib "eagle-import") (part "LME49720MA/NOPB"))
    )
    (comp (ref "U26")
      (value "LME49720")
      (footprint "eagle-import:SO8")
      (libsource (lib "eagle-import") (part "LME49720MA/NOPB"))
    )
    (comp (ref "U27")
      (value "PCM1754")
      (footprint "eagle-import:SSOP16-4MM@1")
      (libsource (lib "eagle-import") (part "PCM1754"))
    )
    (comp (ref "U28")
      (value "LME49720")
      (footprint "eagle-import:SO8")
      (libsource (lib "eagle-import") (part "LME49720MA/NOPB"))
    )
    (comp (ref "MECH1")
      (value "6mm x 3mm")
      (footprint "eagle-import:MOUNTHOLE_6X3")
      (libsource (lib "eagle-import") (part "MOUNTHOLE"))
    )
    (comp (ref "MECH2")
      (value "6mm x 3mm")
      (footprint "eagle-import:MOUNTHOLE_6X3")
      (libsource (lib "eagle-import") (part "MOUNTHOLE"))
    )
    (comp (ref "MECH3")
      (value "6mm x 3mm")
      (footprint "eagle-import:MOUNTHOLE_6X3")
      (libsource (lib "eagle-import") (part "MOUNTHOLE"))
    )
    (comp (ref "MECH4")
      (value "6mm x 3mm")
      (footprint "eagle-import:MOUNTHOLE_6X3")
      (libsource (lib "eagle-import") (part "MOUNTHOLE"))
    )
    (comp (ref "C7")
      (value "100nF 50V")
      (footprint "eagle-import:0603")
      (fields (field (name "FARNELL") "2407338") (field (name "PRICE_PER") "0.0085"))
      (libsource (lib "eagle-import") (part "VJ0603Y104KXACW1BC"))
    )
    (comp (ref "C22")
      (value "10uF 16V")
      (footprint "eagle-import:1206")
      (libsource (lib "eagle-import") (part "MC1206B106K160CT"))
    )
    (comp (ref "C23")
      (value "10uF 16V")
      (footprint "eagle-import:1206")
      (libsource (lib "eagle-import") (part "MC1206B106K160CT"))
    )
    (comp (ref "C24")
      (value "100nF 50V")
      (footprint "eagle-import:0603")
      (fields (field (name "FARNELL") "2407338") (field (name "PRICE_PER") "0.0085"))
      (libsource (lib "eagle-import") (part "VJ0603Y104KXACW1BC"))
    )
    (comp (ref "C25")
      (value "100nF 50V")
      (footprint "eagle-import:0603")
      (fields (field (name "FARNELL") "2407338") (field (name "PRICE_PER") "0.0085"))
      (libsource (lib "eagle-import") (part "VJ0603Y104KXACW1BC"))
    )
    (comp (ref "C26")
      (value "100nF 50V")
      (footprint "eagle-import:0603")
      (fields (field (name "FARNELL") "2407338") (field (name "PRICE_PER") "0.0085"))
      (libsource (lib "eagle-import") (part "VJ0603Y104KXACW1BC"))
    )
    (comp (ref "C36")
      (value "10uF 16V")
      (footprint "eagle-import:1206")
      (libsource (lib "eagle-import") (part "MC1206B106K160CT"))
    )
    (comp (ref "C37")
      (value "10uF 16V")
      (footprint "eagle-import:1206")
      (libsource (lib "eagle-import") (part "MC1206B106K160CT"))
    )
    (comp (ref "C38")
      (value "100nF 50V")
      (footprint "eagle-import:0603")
      (fields (field (name "FARNELL") "2407338") (field (name "PRICE_PER") "0.0085"))
      (libsource (lib "eagle-import") (part "VJ0603Y104KXACW1BC"))
    )
    (comp (ref "C47")
      (value "100nF 50V")
      (footprint "eagle-import:0603")
      (fields (field (name "FARNELL") "2407338") (field (name "PRICE_PER") "0.0085"))
      (libsource (lib "eagle-import") (part "VJ0603Y104KXACW1BC"))
    )
    (comp (ref "C48")
      (value "10uF 16V")
      (footprint "eagle-import:1206")
      (libsource (lib "eagle-import") (part "MC1206B106K160CT"))
    )
    (comp (ref "C49")
      (value "10uF 16V")
      (footprint "eagle-import:1206")
      (libsource (lib "eagle-import") (part "MC1206B106K160CT"))
    )
    (comp (ref "C69")
      (value "10uF 16V")
      (footprint "eagle-import:1206")
      (libsource (lib "eagle-import") (part "MC1206B106K160CT"))
    )
    (comp (ref "C70")
      (value "10uF 16V")
      (footprint "eagle-import:1206")
      (libsource (lib "eagle-import") (part "MC1206B106K160CT"))
    )
    (comp (ref "C71")
      (value "10uF 16V")
      (footprint "eagle-import:1206")
      (libsource (lib "eagle-import") (part "MC1206B106K160CT"))
    )
    (comp (ref "C72")
      (value "10uF 16V")
      (footprint "eagle-import:1206")
      (libsource (lib "eagle-import") (part "MC1206B106K160CT"))
    )
    (comp (ref "C73")
      (value "10uF 16V")
      (footprint "eagle-import:1206")
      (libsource (lib "eagle-import") (part "MC1206B106K160CT"))
    )
    (comp (ref "C74")
      (value "10uF 16V")
      (footprint "eagle-import:1206")
      (libsource (lib "eagle-import") (part "MC1206B106K160CT"))
    )
    (comp (ref "C79")
      (value "100nF 50V")
      (footprint "eagle-import:0603")
      (libsource (lib "eagle-import") (part "VJ0603Y104KXACW1BC"))
    )
    (comp (ref "C110")
      (value "100nF 50V")
      (footprint "eagle-import:0603")
      (libsource (lib "eagle-import") (part "VJ0603Y104KXACW1BC"))
    )
    (comp (ref "C111")
      (value "100nF 50V")
      (footprint "eagle-import:0603")
      (libsource (lib "eagle-import") (part "VJ0603Y104KXACW1BC"))
    )
    (comp (ref "C112")
      (value "100nF 50V")
      (footprint "eagle-import:0603")
      (libsource (lib "eagle-import") (part "VJ0603Y104KXACW1BC"))
    )
    (comp (ref "C113")
      (value "100nF 50V")
      (footprint "eagle-import:0603")
      (libsource (lib "eagle-import") (part "VJ0603Y104KXACW1BC"))
    )
    (comp (ref "C116")
      (value "100nF 50V")
      (footprint "eagle-import:0603")
      (libsource (lib "eagle-import") (part "VJ0603Y104KXACW1BC"))
    )
    (comp (ref "CN6")
      (value "6.35MM_TAB_TERMINAL")
      (footprint "eagle-import:6.35MM_TERMINAL")
      (libsource (lib "eagle-import") (part "6.35MM_TAB_TERMINAL"))
    )
    (comp (ref "CN7")
      (value "6.35MM_TAB_TERMINAL")
      (footprint "eagle-import:6.35MM_TERMINAL")
      (libsource (lib "eagle-import") (part "6.35MM_TAB_TERMINAL"))
    )
    (comp (ref "CN8")
      (value "6.35MM_TAB_TERMINAL")
      (footprint "eagle-import:6.35MM_TERMINAL")
      (libsource (lib "eagle-import") (part "6.35MM_TAB_TERMINAL"))
    )
    (comp (ref "FB2")
      (value "150R")
      (footprint "eagle-import:1206")
      (libsource (lib "eagle-import") (part "LI1206H151R-10"))
    )
    (comp (ref "FB18")
      (value "150R")
      (footprint "eagle-import:1206")
      (libsource (lib "eagle-import") (part "LI1206H151R-10"))
    )
    (comp (ref "FB19")
      (value "150R")
      (footprint "eagle-import:1206")
      (libsource (lib "eagle-import") (part "LI1206H151R-10"))
    )
    (comp (ref "R23")
      (value "270R")
      (footprint "eagle-import:0603")
      (libsource (lib "eagle-import") (part "CRCW0603270RFKEA"))
    )
    (comp (ref "R24")
      (value "270R")
      (footprint "eagle-import:0603")
      (libsource (lib "eagle-import") (part "CRCW0603270RFKEA"))
    )
    (comp (ref "R25")
      (value "270R")
      (footprint "eagle-import:0603")
      (libsource (lib "eagle-import") (part "CRCW0603270RFKEA"))
    )
    (comp (ref "R26")
      (value "110R")
      (footprint "eagle-import:0603")
      (libsource (lib "eagle-import") (part "CRCW0603110RFKEA"))
    )
    (comp (ref "R27")
      (value "330R")
      (footprint "eagle-import:0603")
      (libsource (lib "eagle-import") (part "CRCW0603330RFKEA"))
    )
    (comp (ref "R28")
      (value "110R")
      (footprint "eagle-import:0603")
      (libsource (lib "eagle-import") (part "CRCW0603110RFKEA"))
    )
    (comp (ref "R29")
      (value "330R")
      (footprint "eagle-import:0603")
      (libsource (lib "eagle-import") (part "CRCW0603330RFKEA"))
    )
    (comp (ref "R51")
      (value "110R")
      (footprint "eagle-import:0603")
      (libsource (lib "eagle-import") (part "CRCW0603110RFKEA"))
    )
    (comp (ref "R52")
      (value "330R")
      (footprint "eagle-import:0603")
      (libsource (lib "eagle-import") (part "CRCW0603330RFKEA"))
    )
    (comp (ref "R59")
      (value "0R")
      (footprint "eagle-import:0603")
      (libsource (lib "eagle-import") (part "CRCW06030000Z0EA"))
    )
    (comp (ref "U4")
      (value "LM317")
      (footprint "eagle-import:SOT89")
      (libsource (lib "eagle-import") (part "LM317LCPK"))
    )
    (comp (ref "U5")
      (value "LM317")
      (footprint "eagle-import:SOT89")
      (libsource (lib "eagle-import") (part "LM317LCPK"))
    )
    (comp (ref "U11")
      (value "LM317MQDCYR")
      (footprint "eagle-import:SOT223")
      (libsource (lib "eagle-import") (part "LM317MQDCYR"))
    )
    (comp (ref "U12")
      (value "LM337IMP")
      (footprint "eagle-import:SOT223")
      (libsource (lib "eagle-import") (part "LM337IMP"))
    )
    (comp (ref "U13")
      (value "LM317")
      (footprint "eagle-import:SOT89")
      (libsource (lib "eagle-import") (part "LM317LCPK"))
    )
    (comp (ref "U17")
      (value "LD1117AV33")
      (footprint "eagle-import:TO220")
      (libsource (lib "eagle-import") (part "LD1117AV33"))
    )
    (comp (ref "C2")
      (value "100nF 50V")
      (footprint "eagle-import:0603")
      (libsource (lib "eagle-import") (part "VJ0603Y104KXACW1BC"))
    )
    (comp (ref "C3")
      (value "100nF 50V")
      (footprint "eagle-import:0603")
      (libsource (lib "eagle-import") (part "VJ0603Y104KXACW1BC"))
    )
    (comp (ref "C4")
      (value "18pF 50V")
      (footprint "eagle-import:0603")
      (libsource (lib "eagle-import") (part "MC0603N180J500CT"))
    )
    (comp (ref "C5")
      (value "18pF 50V")
      (footprint "eagle-import:0603")
      (libsource (lib "eagle-import") (part "MC0603N180J500CT"))
    )
    (comp (ref "C6")
      (value "100nF 50V")
      (footprint "eagle-import:0603")
      (fields (field (name "FARNELL") "2407338") (field (name "PRICE_PER") "0.0085"))
      (libsource (lib "eagle-import") (part "VJ0603Y104KXACW1BC"))
    )
    (comp (ref "C8")
      (value "1uF 25V")
      (footprint "eagle-import:0603")
      (libsource (lib "eagle-import") (part "MC0603X105K250CT"))
    )
    (comp (ref "C54")
      (value "10nF 50V")
      (footprint "eagle-import:0603")
      (libsource (lib "eagle-import") (part "MC0603B103K500CT"))
    )
    (comp (ref "CN2")
      (value "SMAVERTICAL_R")
      (footprint "eagle-import:SMAVERTICAL")
      (libsource (lib "eagle-import") (part "SMAVERTICAL_R"))
    )
    (comp (ref "R1")
      (value "75R")
      (footprint "eagle-import:0603")
      (libsource (lib "eagle-import") (part "CRCW060375R0FKEA"))
    )
    (comp (ref "R2")
      (value "330R")
      (footprint "eagle-import:0603")
      (libsource (lib "eagle-import") (part "CRCW0603330RFKEA"))
    )
    (comp (ref "R20")
      (value "10K")
      (footprint "eagle-import:0603")
      (fields (field (name "FARNELL") "1469748") (field (name "PRICE_PER") "0.0095"))
      (libsource (lib "eagle-import") (part "CRCW060310K0FKEA"))
    )
    (comp (ref "R53")
      (value "10K")
      (footprint "eagle-import:0603")
      (libsource (lib "eagle-import") (part "CRCW060310K0FKEA"))
    )
    (comp (ref "R54")
      (value "10K")
      (footprint "eagle-import:0603")
      (libsource (lib "eagle-import") (part "CRCW060310K0FKEA"))
    )
    (comp (ref "R55")
      (value "10K")
      (footprint "eagle-import:0603")
      (libsource (lib "eagle-import") (part "CRCW060310K0FKEA"))
    )
    (comp (ref "R56")
      (value "10K")
      (footprint "eagle-import:0603")
      (libsource (lib "eagle-import") (part "CRCW060310K0FKEA"))
    )
    (comp (ref "R57")
      (value "10K")
      (footprint "eagle-import:0603")
      (libsource (lib "eagle-import") (part "CRCW060310K0FKEA"))
    )
    (comp (ref "TX1")
      (value "DA101C")
      (footprint "eagle-import:DA10XC")
      (libsource (lib "eagle-import") (part "DA101C"))
    )
    (comp (ref "U1")
      (value "WM8804")
      (footprint "eagle-import:SSOP20-5MM")
      (libsource (lib "eagle-import") (part "WM8804GEDS/RV"))
    )
    (comp (ref "XTAL1")
      (value "ABM8-12.000MHZ-B2-T")
      (footprint "eagle-import:3.2X3.5SMD")
      (libsource (lib "eagle-import") (part "ABM8-12.000MHZ-B2-T"))
    )
    (comp (ref "C16")
      (value "100nF 50V")
      (footprint "eagle-import:0603")
      (fields (field (name "FARNELL") "2407338") (field (name "PRICE_PER") "0.0085"))
      (libsource (lib "eagle-import") (part "VJ0603Y104KXACW1BC"))
    )
    (comp (ref "C17")
      (value "2.2uF 25V")
      (footprint "eagle-import:0603")
      (fields (field (name "FARNELL") "1845734") (field (name "PRICE_PER") "0.0832"))
      (libsource (lib "eagle-import") (part "GRM188R61E225KA12D"))
    )
    (comp (ref "C50")
      (value "100nF 50V")
      (footprint "eagle-import:0603")
      (fields (field (name "FARNELL") "2407338") (field (name "PRICE_PER") "0.0085"))
      (libsource (lib "eagle-import") (part "VJ0603Y104KXACW1BC"))
    )
    (comp (ref "C62")
      (value "100nF 50V")
      (footprint "eagle-import:0603")
      (libsource (lib "eagle-import") (part "VJ0603Y104KXACW1BC"))
    )
    (comp (ref "C76")
      (value "100nF 50V")
      (footprint "eagle-import:0603")
      (fields (field (name "FARNELL") "2407338") (field (name "PRICE_PER") "0.0085"))
      (libsource (lib "eagle-import") (part "VJ0603Y104KXACW1BC"))
    )
    (comp (ref "C77")
      (value "100nF 50V")
      (footprint "eagle-import:0603")
      (fields (field (name "FARNELL") "2407338") (field (name "PRICE_PER") "0.0085"))
      (libsource (lib "eagle-import") (part "VJ0603Y104KXACW1BC"))
    )
    (comp (ref "C78")
      (value "100nF 50V")
      (footprint "eagle-import:0603")
      (fields (field (name "FARNELL") "2407338") (field (name "PRICE_PER") "0.0085"))
      (libsource (lib "eagle-import") (part "VJ0603Y104KXACW1BC"))
    )
    (comp (ref "C80")
      (value "100nF 50V")
      (footprint "eagle-import:0603")
      (fields (field (name "FARNELL") "2407338") (field (name "PRICE_PER") "0.0085"))
      (libsource (lib "eagle-import") (part "VJ0603Y104KXACW1BC"))
    )
    (comp (ref "C81")
      (value "100nF 50V")
      (footprint "eagle-import:0603")
      (fields (field (name "FARNELL") "2407338") (field (name "PRICE_PER") "0.0085"))
      (libsource (lib "eagle-import") (part "VJ0603Y104KXACW1BC"))
    )
    (comp (ref "C82")
      (value "100nF 50V")
      (footprint "eagle-import:0603")
      (fields (field (name "FARNELL") "2407338") (field (name "PRICE_PER") "0.0085"))
      (libsource (lib "eagle-import") (part "VJ0603Y104KXACW1BC"))
    )
    (comp (ref "C83")
      (value "100nF 50V")
      (footprint "eagle-import:0603")
      (fields (field (name "FARNELL") "2407338") (field (name "PRICE_PER") "0.0085"))
      (libsource (lib "eagle-import") (part "VJ0603Y104KXACW1BC"))
    )
    (comp (ref "C84")
      (value "100nF 50V")
      (footprint "eagle-import:0603")
      (fields (field (name "FARNELL") "2407338") (field (name "PRICE_PER") "0.0085"))
      (libsource (lib "eagle-import") (part "VJ0603Y104KXACW1BC"))
    )
    (comp (ref "C85")
      (value "100nF 50V")
      (footprint "eagle-import:0603")
      (fields (field (name "FARNELL") "2407338") (field (name "PRICE_PER") "0.0085"))
      (libsource (lib "eagle-import") (part "VJ0603Y104KXACW1BC"))
    )
    (comp (ref "C86")
      (value "100nF 50V")
      (footprint "eagle-import:0603")
      (fields (field (name "FARNELL") "2407338") (field (name "PRICE_PER") "0.0085"))
      (libsource (lib "eagle-import") (part "VJ0603Y104KXACW1BC"))
    )
    (comp (ref "C87")
      (value "100nF 50V")
      (footprint "eagle-import:0603")
      (fields (field (name "FARNELL") "2407338") (field (name "PRICE_PER") "0.0085"))
      (libsource (lib "eagle-import") (part "VJ0603Y104KXACW1BC"))
    )
    (comp (ref "C88")
      (value "100nF 50V")
      (footprint "eagle-import:0603")
      (fields (field (name "FARNELL") "2407338") (field (name "PRICE_PER") "0.0085"))
      (libsource (lib "eagle-import") (part "VJ0603Y104KXACW1BC"))
    )
    (comp (ref "C89")
      (value "100nF 50V")
      (footprint "eagle-import:0603")
      (fields (field (name "FARNELL") "2407338") (field (name "PRICE_PER") "0.0085"))
      (libsource (lib "eagle-import") (part "VJ0603Y104KXACW1BC"))
    )
    (comp (ref "C90")
      (value "100nF 50V")
      (footprint "eagle-import:0603")
      (fields (field (name "FARNELL") "2407338") (field (name "PRICE_PER") "0.0085"))
      (libsource (lib "eagle-import") (part "VJ0603Y104KXACW1BC"))
    )
    (comp (ref "C91")
      (value "100nF 50V")
      (footprint "eagle-import:0603")
      (fields (field (name "FARNELL") "2407338") (field (name "PRICE_PER") "0.0085"))
      (libsource (lib "eagle-import") (part "VJ0603Y104KXACW1BC"))
    )
    (comp (ref "C92")
      (value "100nF 50V")
      (footprint "eagle-import:0603")
      (fields (field (name "FARNELL") "2407338") (field (name "PRICE_PER") "0.0085"))
      (libsource (lib "eagle-import") (part "VJ0603Y104KXACW1BC"))
    )
    (comp (ref "C93")
      (value "100nF 50V")
      (footprint "eagle-import:0603")
      (fields (field (name "FARNELL") "2407338") (field (name "PRICE_PER") "0.0085"))
      (libsource (lib "eagle-import") (part "VJ0603Y104KXACW1BC"))
    )
    (comp (ref "C94")
      (value "100nF 50V")
      (footprint "eagle-import:0603")
      (fields (field (name "FARNELL") "2407338") (field (name "PRICE_PER") "0.0085"))
      (libsource (lib "eagle-import") (part "VJ0603Y104KXACW1BC"))
    )
    (comp (ref "C95")
      (value "100nF 50V")
      (footprint "eagle-import:0603")
      (fields (field (name "FARNELL") "2407338") (field (name "PRICE_PER") "0.0085"))
      (libsource (lib "eagle-import") (part "VJ0603Y104KXACW1BC"))
    )
    (comp (ref "C96")
      (value "100nF 50V")
      (footprint "eagle-import:0603")
      (fields (field (name "FARNELL") "2407338") (field (name "PRICE_PER") "0.0085"))
      (libsource (lib "eagle-import") (part "VJ0603Y104KXACW1BC"))
    )
    (comp (ref "C97")
      (value "100nF 50V")
      (footprint "eagle-import:0603")
      (fields (field (name "FARNELL") "2407338") (field (name "PRICE_PER") "0.0085"))
      (libsource (lib "eagle-import") (part "VJ0603Y104KXACW1BC"))
    )
    (comp (ref "C98")
      (value "100nF 50V")
      (footprint "eagle-import:0603")
      (fields (field (name "FARNELL") "2407338") (field (name "PRICE_PER") "0.0085"))
      (libsource (lib "eagle-import") (part "VJ0603Y104KXACW1BC"))
    )
    (comp (ref "C99")
      (value "100nF 50V")
      (footprint "eagle-import:0603")
      (fields (field (name "FARNELL") "2407338") (field (name "PRICE_PER") "0.0085"))
      (libsource (lib "eagle-import") (part "VJ0603Y104KXACW1BC"))
    )
    (comp (ref "C100")
      (value "100nF 50V")
      (footprint "eagle-import:0603")
      (fields (field (name "FARNELL") "2407338") (field (name "PRICE_PER") "0.0085"))
      (libsource (lib "eagle-import") (part "VJ0603Y104KXACW1BC"))
    )
    (comp (ref "C138")
      (value "100nF 50V")
      (footprint "eagle-import:0603")
      (fields (field (name "FARNELL") "2407338") (field (name "PRICE_PER") "0.0085"))
      (libsource (lib "eagle-import") (part "VJ0603Y104KXACW1BC"))
    )
    (comp (ref "C139")
      (value "100nF 50V")
      (footprint "eagle-import:0603")
      (fields (field (name "FARNELL") "2407338") (field (name "PRICE_PER") "0.0085"))
      (libsource (lib "eagle-import") (part "VJ0603Y104KXACW1BC"))
    )
    (comp (ref "C140")
      (value "100nF 50V")
      (footprint "eagle-import:0603")
      (fields (field (name "FARNELL") "2407338") (field (name "PRICE_PER") "0.0085"))
      (libsource (lib "eagle-import") (part "VJ0603Y104KXACW1BC"))
    )
    (comp (ref "CN3")
      (value "5X2HEADER")
      (footprint "eagle-import:5X2_2.54MMHEADER")
      (libsource (lib "eagle-import") (part "5X2HEADER"))
    )
    (comp (ref "CN5")
      (value "PICOBLADE_5_TH_V")
      (footprint "eagle-import:MOLEX_530470510")
      (libsource (lib "eagle-import") (part "PICOBLADE_5_TH_V"))
    )
    (comp (ref "CN10")
      (value "PICOBLADE_5_TH_V")
      (footprint "eagle-import:MOLEX_530470510")
      (libsource (lib "eagle-import") (part "PICOBLADE_5_TH_V"))
    )
    (comp (ref "CN11")
      (value "2X3_HEADER")
      (footprint "eagle-import:2X3HEADER")
      (libsource (lib "eagle-import") (part "2X3_HEADER"))
    )
    (comp (ref "CN12")
      (value "PICOBLADE_3_TH_V")
      (footprint "eagle-import:MOLEX_530470310")
      (libsource (lib "eagle-import") (part "PICOBLADE_3_TH_V"))
    )
    (comp (ref "CN15")
      (value "MUSB-05-S-B-SM-A")
      (footprint "eagle-import:MUSB-05-S-B-SM-A")
      (libsource (lib "eagle-import") (part "MUSB-05-S-B-SM-A"))
    )
    (comp (ref "R22")
      (value "10K")
      (footprint "eagle-import:0603")
      (fields (field (name "FARNELL") "1469748") (field (name "PRICE_PER") "0.0095"))
      (libsource (lib "eagle-import") (part "CRCW060310K0FKEA"))
    )
    (comp (ref "R30")
      (value "10K")
      (footprint "eagle-import:0603")
      (fields (field (name "FARNELL") "1469748") (field (name "PRICE_PER") "0.0095"))
      (libsource (lib "eagle-import") (part "CRCW060310K0FKEA"))
    )
    (comp (ref "R37")
      (value "10K")
      (footprint "eagle-import:0603")
      (libsource (lib "eagle-import") (part "CRCW060310K0FKEA"))
    )
    (comp (ref "R38")
      (value "10K")
      (footprint "eagle-import:0603")
      (libsource (lib "eagle-import") (part "CRCW060310K0FKEA"))
    )
    (comp (ref "R39")
      (value "10K")
      (footprint "eagle-import:0603")
      (libsource (lib "eagle-import") (part "CRCW060310K0FKEA"))
    )
    (comp (ref "R40")
      (value "16R")
      (footprint "eagle-import:0603")
      (libsource (lib "eagle-import") (part "CRCW060316R0FKEA"))
    )
    (comp (ref "R41")
      (value "10K")
      (footprint "eagle-import:0603")
      (fields (field (name "FARNELL") "1469748") (field (name "PRICE_PER") "0.0095"))
      (libsource (lib "eagle-import") (part "CRCW060310K0FKEA"))
    )
    (comp (ref "R42")
      (value "10K")
      (footprint "eagle-import:0603")
      (fields (field (name "FARNELL") "1469748") (field (name "PRICE_PER") "0.0095"))
      (libsource (lib "eagle-import") (part "CRCW060310K0FKEA"))
    )
    (comp (ref "R43")
      (value "1k")
      (footprint "eagle-import:0603")
      (libsource (lib "eagle-import") (part "CRCW06031K00FKEA"))
    )
    (comp (ref "R44")
      (value "1k")
      (footprint "eagle-import:0603")
      (libsource (lib "eagle-import") (part "CRCW06031K00FKEA"))
    )
    (comp (ref "R45")
      (value "1k")
      (footprint "eagle-import:0603")
      (libsource (lib "eagle-import") (part "CRCW06031K00FKEA"))
    )
    (comp (ref "R84")
      (value "10K")
      (footprint "eagle-import:0603")
      (libsource (lib "eagle-import") (part "CRCW060310K0FKEA"))
    )
    (comp (ref "U9")
      (value "EP4CE6E22C8N")
      (footprint "eagle-import:QFP144_PP")
      (libsource (lib "eagle-import") (part "EP4CE6E22C8N"))
    )
    (comp (ref "U10")
      (value "M25P16")
      (footprint "eagle-import:SO8")
      (libsource (lib "eagle-import") (part "M25P16-VMN6P"))
    )
    (comp (ref "U14")
      (value "24.576MHz")
      (footprint "eagle-import:ASEMB")
      (libsource (lib "eagle-import") (part "ASEMB-24.576MHZ"))
    )
    (comp (ref "U15")
      (value "USBLC6-2SC6")
      (footprint "eagle-import:SOT23-6")
      (libsource (lib "eagle-import") (part "USBLC6-2SC6"))
    )
    (comp (ref "U16")
      (value "FT230X")
      (footprint "eagle-import:SSOP16-4MM")
      (libsource (lib "eagle-import") (part "FT230XS"))
    )
    (comp (ref "U20")
      (value "100MHz")
      (footprint "eagle-import:5X3.2SEAM")
      (libsource (lib "eagle-import") (part "510BBA100M000BAG"))
    )
    (comp (ref "U29")
      (value "STM32F030F4")
      (footprint "eagle-import:SSOP20-4.5MM")
      (libsource (lib "eagle-import") (part "STM32F030F4"))
    )
    (comp (ref "U30")
      (value "SST26VF016B")
      (footprint "eagle-import:SO8")
      (libsource (lib "eagle-import") (part "SST26VF016B-104I/SN"))
    )
  )
  (nets
    (net (code "1") (name "+5V") (class "Default")
      (node (ref "C117") (pin "2") (pinfunction "2_2") (pintype "bidirectional"))
      (node (ref "C119") (pin "2") (pinfunction "2_2") (pintype "bidirectional"))
      (node (ref "C130") (pin "2") (pinfunction "2_2") (pintype "bidirectional"))
      (node (ref "C43") (pin "2") (pinfunction "2_2") (pintype "bidirectional"))
      (node (ref "C45") (pin "2") (pinfunction "2_2") (pintype "bidirectional"))
      (node (ref "C52") (pin "2") (pinfunction "2_2") (pintype "bidirectional"))
      (node (ref "C56") (pin "2") (pinfunction "2_2") (pintype "bidirectional"))
      (node (ref "C68") (pin "2") (pinfunction "2_2") (pintype "bidirectional"))
      (node (ref "C73") (pin "2") (pinfunction "2_2") (pintype "bidirectional"))
      (node (ref "C79") (pin "2") (pinfunction "2_2") (pintype "bidirectional"))
      (node (ref "C9") (pin "2") (pinfunction "2_2") (pintype "bidirectional"))
      (node (ref "FB11") (pin "1") (pinfunction "1_1") (pintype "bidirectional"))
      (node (ref "FB13") (pin "2") (pinfunction "2_2") (pintype "bidirectional"))
      (node (ref "FB3") (pin "1") (pinfunction "1_1") (pintype "bidirectional"))
      (node (ref "FB6") (pin "2") (pinfunction "2_2") (pintype "bidirectional"))
      (node (ref "FB7") (pin "1") (pinfunction "1_1") (pintype "bidirectional"))
      (node (ref "FB9") (pin "2") (pinfunction "2_2") (pintype "bidirectional"))
      (node (ref "R26") (pin "2") (pinfunction "2_2") (pintype "bidirectional"))
      (node (ref "U11") (pin "2") (pinfunction "VOUT_2") (pintype "bidirectional"))
      (node (ref "U11") (pin "4") (pinfunction "VOUT_4") (pintype "bidirectional"))
      (node (ref "U19") (pin "8") (pinfunction "V+_8") (pintype "bidirectional"))
      (node (ref "U21") (pin "8") (pinfunction "V+_8") (pintype "bidirectional"))
      (node (ref "U23") (pin "8") (pinfunction "V+_8") (pintype "bidirectional"))
      (node (ref "U25") (pin "8") (pinfunction "V+_8") (pintype "bidirectional"))
      (node (ref "U26") (pin "8") (pinfunction "V+_8") (pintype "bidirectional"))
      (node (ref "U28") (pin "8") (pinfunction "V+_8") (pintype "bidirectional"))
      (node (ref "U3") (pin "8") (pinfunction "V+_8") (pintype "bidirectional"))
      (node (ref "U7") (pin "8") (pinfunction "V+_8") (pintype "bidirectional"))
      (node (ref "U8") (pin "8") (pinfunction "V+_8") (pintype "bidirectional"))
    )
    (net (code "2") (name "-5V") (class "Default")
      (node (ref "C112") (pin "1") (pinfunction "1_1") (pintype "bidirectional"))
      (node (ref "C118") (pin "1") (pinfunction "1_1") (pintype "bidirectional"))
      (node (ref "C120") (pin "1") (pinfunction "1_1") (pintype "bidirectional"))
      (node (ref "C131") (pin "1") (pinfunction "1_1") (pintype "bidirectional"))
      (node (ref "C35") (pin "1") (pinfunction "1_1") (pintype "bidirectional"))
      (node (ref "C44") (pin "1") (pinfunction "1_1") (pintype "bidirectional"))
      (node (ref "C46") (pin "1") (pinfunction "1_1") (pintype "bidirectional"))
      (node (ref "C53") (pin "1") (pinfunction "1_1") (pintype "bidirectional"))
      (node (ref "C57") (pin "1") (pinfunction "1_1") (pintype "bidirectional"))
      (node (ref "C74") (pin "1") (pinfunction "1_1") (pintype "bidirectional"))
      (node (ref "C75") (pin "1") (pinfunction "1_1") (pintype "bidirectional"))
      (node (ref "FB1") (pin "1") (pinfunction "1_1") (pintype "bidirectional"))
      (node (ref "FB10") (pin "1") (pinfunction "1_1") (pintype "bidirectional"))
      (node (ref "FB5") (pin "1") (pinfunction "1_1") (pintype "bidirectional"))
      (node (ref "R51") (pin "1") (pinfunction "1_1") (pintype "bidirectional"))
      (node (ref "U12") (pin "3") (pinfunction "VOUT_3") (pintype "bidirectional"))
      (node (ref "U19") (pin "4") (pinfunction "V-_4") (pintype "bidirectional"))
      (node (ref "U21") (pin "4") (pinfunction "V-_4") (pintype "bidirectional"))
      (node (ref "U23") (pin "4") (pinfunction "V-_4") (pintype "bidirectional"))
      (node (ref "U25") (pin "4") (pinfunction "V-_4") (pintype "bidirectional"))
      (node (ref "U26") (pin "4") (pinfunction "V-_4") (pintype "bidirectional"))
      (node (ref "U28") (pin "4") (pinfunction "V-_4") (pintype "bidirectional"))
      (node (ref "U3") (pin "4") (pinfunction "V-_4") (pintype "bidirectional"))
      (node (ref "U7") (pin "4") (pinfunction "V-_4") (pintype "bidirectional"))
      (node (ref "U8") (pin "4") (pinfunction "V-_4") (pintype "bidirectional"))
    )
    (net (code "3") (name "1V2") (class "Default")
      (node (ref "C23") (pin "2") (pinfunction "2_2") (pintype "bidirectional"))
      (node (ref "C7") (pin "2") (pinfunction "2_2") (pintype "bidirectional"))
      (node (ref "C76") (pin "2") (pinfunction "2_2") (pintype "bidirectional"))
      (node (ref "C77") (pin "2") (pinfunction "2_2") (pintype "bidirectional"))
      (node (ref "C78") (pin "2") (pinfunction "2_2") (pintype "bidirectional"))
      (node (ref "C80") (pin "2") (pinfunction "2_2") (pintype "bidirectional"))
      (node (ref "C81") (pin "2") (pinfunction "2_2") (pintype "bidirectional"))
      (node (ref "C82") (pin "2") (pinfunction "2_2") (pintype "bidirectional"))
      (node (ref "C83") (pin "2") (pinfunction "2_2") (pintype "bidirectional"))
      (node (ref "C84") (pin "2") (pinfunction "2_2") (pintype "bidirectional"))
      (node (ref "C85") (pin "2") (pinfunction "2_2") (pintype "bidirectional"))
      (node (ref "C86") (pin "2") (pinfunction "2_2") (pintype "bidirectional"))
      (node (ref "R23") (pin "2") (pinfunction "2_2") (pintype "bidirectional"))
      (node (ref "U13") (pin "2") (pinfunction "VOUT_2") (pintype "bidirectional"))
      (node (ref "U9") (pin "102") (pinfunction "VCCINT_102") (pintype "bidirectional"))
      (node (ref "U9") (pin "109") (pinfunction "VCCD_PLL_109") (pintype "bidirectional"))
      (node (ref "U9") (pin "116") (pinfunction "VCCINT_116") (pintype "bidirectional"))
      (node (ref "U9") (pin "134") (pinfunction "VCCINT_134") (pintype "bidirectional"))
      (node (ref "U9") (pin "29") (pinfunction "VCCINT_29") (pintype "bidirectional"))
      (node (ref "U9") (pin "37") (pinfunction "VCCD_PLL_37") (pintype "bidirectional"))
      (node (ref "U9") (pin "45") (pinfunction "VCCINT_45") (pintype "bidirectional"))
      (node (ref "U9") (pin "5") (pinfunction "VCCINT_5") (pintype "bidirectional"))
      (node (ref "U9") (pin "61") (pinfunction "VCCINT_61") (pintype "bidirectional"))
      (node (ref "U9") (pin "78") (pinfunction "VCCINT_78") (pintype "bidirectional"))
    )
    (net (code "4") (name "2V5") (class "Default")
      (node (ref "C25") (pin "2") (pinfunction "2_2") (pintype "bidirectional"))
      (node (ref "C37") (pin "2") (pinfunction "2_2") (pintype "bidirectional"))
      (node (ref "C87") (pin "2") (pinfunction "2_2") (pintype "bidirectional"))
      (node (ref "C88") (pin "2") (pinfunction "2_2") (pintype "bidirectional"))
      (node (ref "R24") (pin "2") (pinfunction "2_2") (pintype "bidirectional"))
      (node (ref "U5") (pin "2") (pinfunction "VOUT_2") (pintype "bidirectional"))
      (node (ref "U9") (pin "107") (pinfunction "VCCA_107") (pintype "bidirectional"))
      (node (ref "U9") (pin "35") (pinfunction "VCCA_35") (pintype "bidirectional"))
    )
    (net (code "5") (name "3V3") (class "Default")
      (node (ref "C100") (pin "2") (pinfunction "2_2") (pintype "bidirectional"))
      (node (ref "C113") (pin "2") (pinfunction "2_2") (pintype "bidirectional"))
      (node (ref "C138") (pin "2") (pinfunction "2_2") (pintype "bidirectional"))
      (node (ref "C139") (pin "2") (pinfunction "2_2") (pintype "bidirectional"))
      (node (ref "C140") (pin "2") (pinfunction "2_2") (pintype "bidirectional"))
      (node (ref "C16") (pin "2") (pinfunction "2_2") (pintype "bidirectional"))
      (node (ref "C17") (pin "2") (pinfunction "2_2") (pintype "bidirectional"))
      (node (ref "C2") (pin "2") (pinfunction "2_2") (pintype "bidirectional"))
      (node (ref "C22") (pin "2") (pinfunction "2_2") (pintype "bidirectional"))
      (node (ref "C26") (pin "2") (pinfunction "2_2") (pintype "bidirectional"))
      (node (ref "C50") (pin "2") (pinfunction "2_2") (pintype "bidirectional"))
      (node (ref "C6") (pin "2") (pinfunction "2_2") (pintype "bidirectional"))
      (node (ref "C62") (pin "2") (pinfunction "2_2") (pintype "bidirectional"))
      (node (ref "C70") (pin "2") (pinfunction "2_2") (pintype "bidirectional"))
      (node (ref "C8") (pin "2") (pinfunction "2_2") (pintype "bidirectional"))
      (node (ref "C89") (pin "2") (pinfunction "2_2") (pintype "bidirectional"))
      (node (ref "C90") (pin "2") (pinfunction "2_2") (pintype "bidirectional"))
      (node (ref "C91") (pin "2") (pinfunction "2_2") (pintype "bidirectional"))
      (node (ref "C92") (pin "2") (pinfunction "2_2") (pintype "bidirectional"))
      (node (ref "C93") (pin "2") (pinfunction "2_2") (pintype "bidirectional"))
      (node (ref "C94") (pin "2") (pinfunction "2_2") (pintype "bidirectional"))
      (node (ref "C95") (pin "2") (pinfunction "2_2") (pintype "bidirectional"))
      (node (ref "C96") (pin "2") (pinfunction "2_2") (pintype "bidirectional"))
      (node (ref "C97") (pin "2") (pinfunction "2_2") (pintype "bidirectional"))
      (node (ref "C98") (pin "2") (pinfunction "2_2") (pintype "bidirectional"))
      (node (ref "C99") (pin "2") (pinfunction "2_2") (pintype "bidirectional"))
      (node (ref "CN10") (pin "5") (pinfunction "5_5") (pintype "bidirectional"))
      (node (ref "CN11") (pin "1") (pinfunction "1_1") (pintype "bidirectional"))
      (node (ref "CN3") (pin "8") (pinfunction "8_8") (pintype "bidirectional"))
      (node (ref "CN3") (pin "9") (pinfunction "9_9") (pintype "bidirectional"))
      (node (ref "CN5") (pin "5") (pinfunction "5_5") (pintype "bidirectional"))
      (node (ref "R22") (pin "2") (pinfunction "2_2") (pintype "bidirectional"))
      (node (ref "R37") (pin "1") (pinfunction "1_1") (pintype "bidirectional"))
      (node (ref "R38") (pin "1") (pinfunction "1_1") (pintype "bidirectional"))
      (node (ref "R41") (pin "1") (pinfunction "1_1") (pintype "bidirectional"))
      (node (ref "R42") (pin "1") (pinfunction "1_1") (pintype "bidirectional"))
      (node (ref "R43") (pin "2") (pinfunction "2_2") (pintype "bidirectional"))
      (node (ref "R44") (pin "2") (pinfunction "2_2") (pintype "bidirectional"))
      (node (ref "R53") (pin "2") (pinfunction "2_2") (pintype "bidirectional"))
      (node (ref "R54") (pin "2") (pinfunction "2_2") (pintype "bidirectional"))
      (node (ref "R84") (pin "1") (pinfunction "1_1") (pintype "bidirectional"))
      (node (ref "U1") (pin "19") (pinfunction "DVDD_19") (pintype "bidirectional"))
      (node (ref "U1") (pin "7") (pinfunction "PVDD_7") (pintype "bidirectional"))
      (node (ref "U10") (pin "3") (pinfunction "VCC_3") (pintype "bidirectional"))
      (node (ref "U10") (pin "7") (pinfunction "VCC_7") (pintype "bidirectional"))
      (node (ref "U10") (pin "8") (pinfunction "VCC_8") (pintype "bidirectional"))
      (node (ref "U13") (pin "3") (pinfunction "VIN_3") (pintype "bidirectional"))
      (node (ref "U14") (pin "1") (pinfunction "OE_1") (pintype "bidirectional"))
      (node (ref "U14") (pin "4") (pinfunction "VCC_4") (pintype "bidirectional"))
      (node (ref "U16") (pin "10") (pinfunction "3V3OUT_10") (pintype "bidirectional"))
      (node (ref "U16") (pin "12") (pinfunction "VCC_12") (pintype "bidirectional"))
      (node (ref "U16") (pin "3") (pinfunction "VCCIO_3") (pintype "bidirectional"))
      (node (ref "U17") (pin "2") (pinfunction "VOUT_2") (pintype "bidirectional"))
      (node (ref "U20") (pin "1") (pinfunction "~{ST}_1") (pintype "bidirectional"))
      (node (ref "U20") (pin "4") (pinfunction "VCC_4") (pintype "bidirectional"))
      (node (ref "U29") (pin "16") (pinfunction "VDD_16") (pintype "bidirectional"))
      (node (ref "U29") (pin "5") (pinfunction "VDDA_5") (pintype "bidirectional"))
      (node (ref "U30") (pin "3") (pinfunction "~{WP}/IO2_3") (pintype "bidirectional"))
      (node (ref "U30") (pin "7") (pinfunction "~{HOLD}/IO3_7") (pintype "bidirectional"))
      (node (ref "U30") (pin "8") (pinfunction "VCC_8") (pintype "bidirectional"))
      (node (ref "U9") (pin "117") (pinfunction "VCCIO7_117") (pintype "bidirectional"))
      (node (ref "U9") (pin "122") (pinfunction "VCCIO7_122") (pintype "bidirectional"))
      (node (ref "U9") (pin "130") (pinfunction "VCCIO8_130") (pintype "bidirectional"))
      (node (ref "U9") (pin "139") (pinfunction "VCCIO8_139") (pintype "bidirectional"))
      (node (ref "U9") (pin "17") (pinfunction "VCCIO1_17") (pintype "bidirectional"))
      (node (ref "U9") (pin "26") (pinfunction "VCCIO2_26") (pintype "bidirectional"))
      (node (ref "U9") (pin "40") (pinfunction "VCCIO3_40") (pintype "bidirectional"))
      (node (ref "U9") (pin "47") (pinfunction "VCCIO3_47") (pintype "bidirectional"))
      (node (ref "U9") (pin "56") (pinfunction "VCCIO4_56") (pintype "bidirectional"))
      (node (ref "U9") (pin "62") (pinfunction "VCCIO4_62") (pintype "bidirectional"))
      (node (ref "U9") (pin "81") (pinfunction "VCCIO5_81") (pintype "bidirectional"))
      (node (ref "U9") (pin "93") (pinfunction "VCCIO6_93") (pintype "bidirectional"))
      (node (ref "U9") (pin "94") (pinfunction "MSEL0_94") (pintype "bidirectional"))
      (node (ref "U9") (pin "97") (pinfunction "MSEL2_97") (pintype "bidirectional"))
    )
    (net (code "6") (name "5V") (class "Default")
      (node (ref "C47") (pin "2") (pinfunction "2_2") (pintype "bidirectional"))
      (node (ref "C49") (pin "2") (pinfunction "2_2") (pintype "bidirectional"))
      (node (ref "FB12") (pin "2") (pinfunction "2_2") (pintype "bidirectional"))
      (node (ref "FB4") (pin "2") (pinfunction "2_2") (pintype "bidirectional"))
      (node (ref "FB8") (pin "2") (pinfunction "2_2") (pintype "bidirectional"))
      (node (ref "R28") (pin "2") (pinfunction "2_2") (pintype "bidirectional"))
      (node (ref "U18") (pin "1") (pinfunction "ZCEN_1") (pintype "bidirectional"))
      (node (ref "U24") (pin "1") (pinfunction "ZCEN_1") (pintype "bidirectional"))
      (node (ref "U4") (pin "2") (pinfunction "VOUT_2") (pintype "bidirectional"))
      (node (ref "U6") (pin "1") (pinfunction "ZCEN_1") (pintype "bidirectional"))
    )
    (net (code "7") (name "AGND") (class "Default")
      (node (ref "C1") (pin "1") (pinfunction "1_1") (pintype "bidirectional"))
      (node (ref "C107") (pin "1") (pinfunction "1_1") (pintype "bidirectional"))
      (node (ref "C108") (pin "1") (pinfunction "1_1") (pintype "bidirectional"))
      (node (ref "C110") (pin "1") (pinfunction "1_1") (pintype "bidirectional"))
      (node (ref "C111") (pin "2") (pinfunction "2_2") (pintype "bidirectional"))
      (node (ref "C112") (pin "2") (pinfunction "2_2") (pintype "bidirectional"))
      (node (ref "C114") (pin "1") (pinfunction "1_1") (pintype "bidirectional"))
      (node (ref "C115") (pin "1") (pinfunction "1_1") (pintype "bidirectional"))
      (node (ref "C117") (pin "1") (pinfunction "1_1") (pintype "bidirectional"))
      (node (ref "C118") (pin "2") (pinfunction "2_2") (pintype "bidirectional"))
      (node (ref "C119") (pin "1") (pinfunction "1_1") (pintype "bidirectional"))
      (node (ref "C120") (pin "2") (pinfunction "2_2") (pintype "bidirectional"))
      (node (ref "C121") (pin "1") (pinfunction "1_1") (pintype "bidirectional"))
      (node (ref "C122") (pin "1") (pinfunction "1_1") (pintype "bidirectional"))
      (node (ref "C123") (pin "1") (pinfunction "1_1") (pintype "bidirectional"))
      (node (ref "C124") (pin "1") (pinfunction "1_1") (pintype "bidirectional"))
      (node (ref "C125") (pin "2") (pinfunction "2_2") (pintype "bidirectional"))
      (node (ref "C127") (pin "2") (pinfunction "2_2") (pintype "bidirectional"))
      (node (ref "C129") (pin "1") (pinfunction "1_1") (pintype "bidirectional"))
      (node (ref "C130") (pin "1") (pinfunction "1_1") (pintype "bidirectional"))
      (node (ref "C131") (pin "2") (pinfunction "2_2") (pintype "bidirectional"))
      (node (ref "C18") (pin "1") (pinfunction "1_1") (pintype "bidirectional"))
      (node (ref "C19") (pin "1") (pinfunction "1_1") (pintype "bidirectional"))
      (node (ref "C21") (pin "1") (pinfunction "1_1") (pintype "bidirectional"))
      (node (ref "C27") (pin "1") (pinfunction "1_1") (pintype "bidirectional"))
      (node (ref "C28") (pin "1") (pinfunction "1_1") (pintype "bidirectional"))
      (node (ref "C29") (pin "1") (pinfunction "1_1") (pintype "bidirectional"))
      (node (ref "C30") (pin "1") (pinfunction "1_1") (pintype "bidirectional"))
      (node (ref "C32") (pin "2") (pinfunction "2_2") (pintype "bidirectional"))
      (node (ref "C33") (pin "2") (pinfunction "2_2") (pintype "bidirectional"))
      (node (ref "C35") (pin "2") (pinfunction "2_2") (pintype "bidirectional"))
      (node (ref "C39") (pin "1") (pinfunction "1_1") (pintype "bidirectional"))
      (node (ref "C41") (pin "1") (pinfunction "1_1") (pintype "bidirectional"))
      (node (ref "C42") (pin "1") (pinfunction "1_1") (pintype "bidirectional"))
      (node (ref "C43") (pin "1") (pinfunction "1_1") (pintype "bidirectional"))
      (node (ref "C44") (pin "2") (pinfunction "2_2") (pintype "bidirectional"))
      (node (ref "C45") (pin "1") (pinfunction "1_1") (pintype "bidirectional"))
      (node (ref "C46") (pin "2") (pinfunction "2_2") (pintype "bidirectional"))
      (node (ref "C51") (pin "1") (pinfunction "1_1") (pintype "bidirectional"))
      (node (ref "C52") (pin "1") (pinfunction "1_1") (pintype "bidirectional"))
      (node (ref "C53") (pin "2") (pinfunction "2_2") (pintype "bidirectional"))
      (node (ref "C55") (pin "1") (pinfunction "1_1") (pintype "bidirectional"))
      (node (ref "C56") (pin "1") (pinfunction "1_1") (pintype "bidirectional"))
      (node (ref "C57") (pin "2") (pinfunction "2_2") (pintype "bidirectional"))
      (node (ref "C58") (pin "1") (pinfunction "1_1") (pintype "bidirectional"))
      (node (ref "C59") (pin "1") (pinfunction "1_1") (pintype "bidirectional"))
      (node (ref "C60") (pin "1") (pinfunction "1_1") (pintype "bidirectional"))
      (node (ref "C61") (pin "1") (pinfunction "1_1") (pintype "bidirectional"))
      (node (ref "C63") (pin "2") (pinfunction "2_2") (pintype "bidirectional"))
      (node (ref "C65") (pin "2") (pinfunction "2_2") (pintype "bidirectional"))
      (node (ref "C67") (pin "1") (pinfunction "1_1") (pintype "bidirectional"))
      (node (ref "C68") (pin "1") (pinfunction "1_1") (pintype "bidirectional"))
      (node (ref "C71") (pin "1") (pinfunction "1_1") (pintype "bidirectional"))
      (node (ref "C72") (pin "2") (pinfunction "2_2") (pintype "bidirectional"))
      (node (ref "C73") (pin "1") (pinfunction "1_1") (pintype "bidirectional"))
      (node (ref "C74") (pin "2") (pinfunction "2_2") (pintype "bidirectional"))
      (node (ref "C75") (pin "2") (pinfunction "2_2") (pintype "bidirectional"))
      (node (ref "C79") (pin "1") (pinfunction "1_1") (pintype "bidirectional"))
      (node (ref "C9") (pin "1") (pinfunction "1_1") (pintype "bidirectional"))
      (node (ref "CN1") (pin "2") (pinfunction "2_2") (pintype "bidirectional"))
      (node (ref "CN1") (pin "4") (pinfunction "4_4") (pintype "bidirectional"))
      (node (ref "CN1") (pin "6") (pinfunction "6_6") (pintype "bidirectional"))
      (node (ref "CN4") (pin "2") (pinfunction "2_2") (pintype "bidirectional"))
      (node (ref "CN4") (pin "4") (pinfunction "4_4") (pintype "bidirectional"))
      (node (ref "CN4") (pin "6") (pinfunction "6_6") (pintype "bidirectional"))
      (node (ref "CN9") (pin "2") (pinfunction "2_2") (pintype "bidirectional"))
      (node (ref "CN9") (pin "4") (pinfunction "4_4") (pintype "bidirectional"))
      (node (ref "CN9") (pin "6") (pinfunction "6_6") (pintype "bidirectional"))
      (node (ref "R16") (pin "1") (pinfunction "1_1") (pintype "bidirectional"))
      (node (ref "R17") (pin "1") (pinfunction "1_1") (pintype "bidirectional"))
      (node (ref "R18") (pin "1") (pinfunction "1_1") (pintype "bidirectional"))
      (node (ref "R19") (pin "1") (pinfunction "1_1") (pintype "bidirectional"))
      (node (ref "R27") (pin "1") (pinfunction "1_1") (pintype "bidirectional"))
      (node (ref "R35") (pin "1") (pinfunction "1_1") (pintype "bidirectional"))
      (node (ref "R36") (pin "1") (pinfunction "1_1") (pintype "bidirectional"))
      (node (ref "R52") (pin "2") (pinfunction "2_2") (pintype "bidirectional"))
      (node (ref "R59") (pin "2") (pinfunction "2_2") (pintype "bidirectional"))
      (node (ref "R64") (pin "1") (pinfunction "1_1") (pintype "bidirectional"))
      (node (ref "R65") (pin "1") (pinfunction "1_1") (pintype "bidirectional"))
      (node (ref "R70") (pin "1") (pinfunction "1_1") (pintype "bidirectional"))
      (node (ref "R71") (pin "1") (pinfunction "1_1") (pintype "bidirectional"))
      (node (ref "R82") (pin "1") (pinfunction "1_1") (pintype "bidirectional"))
      (node (ref "R83") (pin "1") (pinfunction "1_1") (pintype "bidirectional"))
      (node (ref "U18") (pin "10") (pinfunction "AGNDR_10") (pintype "bidirectional"))
      (node (ref "U18") (pin "15") (pinfunction "AGNDL_15") (pintype "bidirectional"))
      (node (ref "U19") (pin "5") (pinfunction "+_5") (pintype "bidirectional"))
      (node (ref "U2") (pin "9") (pinfunction "AGND_9") (pintype "bidirectional"))
      (node (ref "U21") (pin "5") (pinfunction "+_5") (pintype "bidirectional"))
      (node (ref "U22") (pin "9") (pinfunction "AGND_9") (pintype "bidirectional"))
      (node (ref "U24") (pin "10") (pinfunction "AGNDR_10") (pintype "bidirectional"))
      (node (ref "U24") (pin "15") (pinfunction "AGNDL_15") (pintype "bidirectional"))
      (node (ref "U25") (pin "5") (pinfunction "+_5") (pintype "bidirectional"))
      (node (ref "U26") (pin "5") (pinfunction "+_5") (pintype "bidirectional"))
      (node (ref "U27") (pin "9") (pinfunction "AGND_9") (pintype "bidirectional"))
      (node (ref "U6") (pin "10") (pinfunction "AGNDR_10") (pintype "bidirectional"))
      (node (ref "U6") (pin "15") (pinfunction "AGNDL_15") (pintype "bidirectional"))
      (node (ref "U7") (pin "5") (pinfunction "+_5") (pintype "bidirectional"))
      (node (ref "U8") (pin "5") (pinfunction "+_5") (pintype "bidirectional"))
    )
    (net (code "8") (name "ASDO") (class "Default")
      (node (ref "U10") (pin "5") (pinfunction "ASDI_5") (pintype "bidirectional"))
      (node (ref "U9") (pin "6") (pinfunction "ASDO_6") (pintype "bidirectional"))
    )
    (net (code "9") (name "CLK_24M576") (class "Default")
      (node (ref "U14") (pin "3") (pinfunction "OUT_3") (pintype "bidirectional"))
      (node (ref "U9") (pin "25") (pinfunction "CLK3_25") (pintype "bidirectional"))
    )
    (net (code "10") (name "CLK_100M") (class "Default")
      (node (ref "U20") (pin "3") (pinfunction "OUT_3") (pintype "bidirectional"))
      (node (ref "U9") (pin "24") (pinfunction "CLK2_24") (pintype "bidirectional"))
    )
    (net (code "11") (name "DAC0_I2S_BCLK") (class "Default")
      (node (ref "U2") (pin "1") (pinfunction "BCK_1") (pintype "bidirectional"))
      (node (ref "U9") (pin "44") (pinfunction "IO20_44") (pintype "bidirectional"))
    )
    (net (code "12") (name "DAC0_I2S_DATA") (class "Default")
      (node (ref "U2") (pin "2") (pinfunction "DATA_2") (pintype "bidirectional"))
      (node (ref "U9") (pin "46") (pinfunction "IO21_46") (pintype "bidirectional"))
    )
    (net (code "13") (name "DAC0_I2S_LRCLK") (class "Default")
      (node (ref "U2") (pin "3") (pinfunction "LRCLK_3") (pintype "bidirectional"))
      (node (ref "U9") (pin "49") (pinfunction "IO22_49") (pintype "bidirectional"))
    )
    (net (code "14") (name "DAC0_I2S_SCLK") (class "Default")
      (node (ref "U2") (pin "16") (pinfunction "SCK_16") (pintype "bidirectional"))
      (node (ref "U9") (pin "50") (pinfunction "IO23_50") (pintype "bidirectional"))
    )
    (net (code "15") (name "DAC1_I2S_BCLK") (class "Default")
      (node (ref "U22") (pin "1") (pinfunction "BCK_1") (pintype "bidirectional"))
      (node (ref "U9") (pin "53") (pinfunction "IO26_53") (pintype "bidirectional"))
    )
    (net (code "16") (name "DAC1_I2S_DATA") (class "Default")
      (node (ref "U22") (pin "2") (pinfunction "DATA_2") (pintype "bidirectional"))
      (node (ref "U9") (pin "54") (pinfunction "IO27_54") (pintype "bidirectional"))
    )
    (net (code "17") (name "DAC1_I2S_LRCLK") (class "Default")
      (node (ref "U22") (pin "3") (pinfunction "LRCLK_3") (pintype "bidirectional"))
      (node (ref "U9") (pin "55") (pinfunction "IO28_55") (pintype "bidirectional"))
    )
    (net (code "18") (name "DAC1_I2S_SCLK") (class "Default")
      (node (ref "U22") (pin "16") (pinfunction "SCK_16") (pintype "bidirectional"))
      (node (ref "U9") (pin "58") (pinfunction "IO29_58") (pintype "bidirectional"))
    )
    (net (code "19") (name "DAC2_I2S_BCLK") (class "Default")
      (node (ref "U27") (pin "1") (pinfunction "BCK_1") (pintype "bidirectional"))
      (node (ref "U9") (pin "69") (pinfunction "IO37_69") (pintype "bidirectional"))
    )
    (net (code "20") (name "DAC2_I2S_DATA") (class "Default")
      (node (ref "U27") (pin "2") (pinfunction "DATA_2") (pintype "bidirectional"))
      (node (ref "U9") (pin "70") (pinfunction "IO38_70") (pintype "bidirectional"))
    )
    (net (code "21") (name "DAC2_I2S_LRCLK") (class "Default")
      (node (ref "U27") (pin "3") (pinfunction "LRCLK_3") (pintype "bidirectional"))
      (node (ref "U9") (pin "71") (pinfunction "IO39_71") (pintype "bidirectional"))
    )
    (net (code "22") (name "DAC2_I2S_SCLK") (class "Default")
      (node (ref "U27") (pin "16") (pinfunction "SCK_16") (pintype "bidirectional"))
      (node (ref "U9") (pin "72") (pinfunction "IO40_72") (pintype "bidirectional"))
    )
    (net (code "23") (name "DAC_MUTE") (class "Default")
      (node (ref "U2") (pin "14") (pinfunction "MUTE_14") (pintype "bidirectional"))
      (node (ref "U22") (pin "14") (pinfunction "MUTE_14") (pintype "bidirectional"))
      (node (ref "U27") (pin "14") (pinfunction "MUTE_14") (pintype "bidirectional"))
      (node (ref "U9") (pin "51") (pinfunction "IO24_51") (pintype "bidirectional"))
    )
    (net (code "24") (name "DATA0") (class "Default")
      (node (ref "R40") (pin "2") (pinfunction "2_2") (pintype "bidirectional"))
      (node (ref "U9") (pin "13") (pinfunction "DATA0_13") (pintype "bidirectional"))
    )
    (net (code "25") (name "DCLK") (class "Default")
      (node (ref "U10") (pin "6") (pinfunction "DCLK_6") (pintype "bidirectional"))
      (node (ref "U9") (pin "12") (pinfunction "DCLK_12") (pintype "bidirectional"))
    )
    (net (code "26") (name "DGND") (class "Default")
      (node (ref "CN12") (pin "3") (pinfunction "3_3") (pintype "bidirectional"))
    )
    (net (code "27") (name "DISP_SPI_MOSI") (class "Default")
      (node (ref "CN10") (pin "3") (pinfunction "3_3") (pintype "bidirectional"))
      (node (ref "U9") (pin "77") (pinfunction "IO45_77") (pintype "bidirectional"))
    )
    (net (code "28") (name "DISP_SPI_SCLK") (class "Default")
      (node (ref "CN10") (pin "4") (pinfunction "4_4") (pintype "bidirectional"))
      (node (ref "U9") (pin "80") (pinfunction "IO46_80") (pintype "bidirectional"))
    )
    (net (code "29") (name "DISP_SPI_~{CE}") (class "Default")
      (node (ref "CN10") (pin "2") (pinfunction "2_2") (pintype "bidirectional"))
      (node (ref "U9") (pin "76") (pinfunction "IO44_76") (pintype "bidirectional"))
    )
    (net (code "30") (name "DSP_REG_CLK") (class "Default")
      (node (ref "U29") (pin "17") (pinfunction "PA9_17") (pintype "bidirectional"))
      (node (ref "U9") (pin "85") (pinfunction "IO49_85") (pintype "bidirectional"))
    )
    (net (code "31") (name "DSP_~{CE}") (class "Default")
      (node (ref "U29") (pin "18") (pinfunction "PA10_18") (pintype "bidirectional"))
      (node (ref "U9") (pin "86") (pinfunction "IO50_86") (pintype "bidirectional"))
    )
    (net (code "32") (name "ENC_A") (class "Default")
      (node (ref "CN5") (pin "2") (pinfunction "2_2") (pintype "bidirectional"))
      (node (ref "U9") (pin "73") (pinfunction "IO41_73") (pintype "bidirectional"))
    )
    (net (code "33") (name "ENC_B") (class "Default")
      (node (ref "CN5") (pin "3") (pinfunction "3_3") (pintype "bidirectional"))
      (node (ref "U9") (pin "74") (pinfunction "IO42_74") (pintype "bidirectional"))
    )
    (net (code "34") (name "ENC_SW") (class "Default")
      (node (ref "CN5") (pin "4") (pinfunction "4_4") (pintype "bidirectional"))
      (node (ref "U9") (pin "75") (pinfunction "IO43_75") (pintype "bidirectional"))
    )
    (net (code "35") (name "FLSH_~{CE}") (class "Default")
      (node (ref "U29") (pin "14") (pinfunction "PB1_14") (pintype "bidirectional"))
      (node (ref "U30") (pin "1") (pinfunction "~{CE}_1") (pintype "bidirectional"))
    )
    (net (code "36") (name "GND") (class "Default")
      (node (ref "C100") (pin "1") (pinfunction "1_1") (pintype "bidirectional"))
      (node (ref "C109") (pin "1") (pinfunction "1_1") (pintype "bidirectional"))
      (node (ref "C113") (pin "1") (pinfunction "1_1") (pintype "bidirectional"))
      (node (ref "C116") (pin "1") (pinfunction "1_1") (pintype "bidirectional"))
      (node (ref "C138") (pin "1") (pinfunction "1_1") (pintype "bidirectional"))
      (node (ref "C139") (pin "1") (pinfunction "1_1") (pintype "bidirectional"))
      (node (ref "C140") (pin "1") (pinfunction "1_1") (pintype "bidirectional"))
      (node (ref "C16") (pin "1") (pinfunction "1_1") (pintype "bidirectional"))
      (node (ref "C17") (pin "1") (pinfunction "1_1") (pintype "bidirectional"))
      (node (ref "C2") (pin "1") (pinfunction "1_1") (pintype "bidirectional"))
      (node (ref "C20") (pin "1") (pinfunction "1_1") (pintype "bidirectional"))
      (node (ref "C22") (pin "1") (pinfunction "1_1") (pintype "bidirectional"))
      (node (ref "C23") (pin "1") (pinfunction "1_1") (pintype "bidirectional"))
      (node (ref "C24") (pin "1") (pinfunction "1_1") (pintype "bidirectional"))
      (node (ref "C25") (pin "1") (pinfunction "1_1") (pintype "bidirectional"))
      (node (ref "C26") (pin "1") (pinfunction "1_1") (pintype "bidirectional"))
      (node (ref "C36") (pin "1") (pinfunction "1_1") (pintype "bidirectional"))
      (node (ref "C37") (pin "1") (pinfunction "1_1") (pintype "bidirectional"))
      (node (ref "C38") (pin "1") (pinfunction "1_1") (pintype "bidirectional"))
      (node (ref "C4") (pin "1") (pinfunction "1_1") (pintype "bidirectional"))
      (node (ref "C40") (pin "1") (pinfunction "1_1") (pintype "bidirectional"))
      (node (ref "C47") (pin "1") (pinfunction "1_1") (pintype "bidirectional"))
      (node (ref "C48") (pin "1") (pinfunction "1_1") (pintype "bidirectional"))
      (node (ref "C49") (pin "1") (pinfunction "1_1") (pintype "bidirectional"))
      (node (ref "C5") (pin "1") (pinfunction "1_1") (pintype "bidirectional"))
      (node (ref "C50") (pin "1") (pinfunction "1_1") (pintype "bidirectional"))
      (node (ref "C6") (pin "1") (pinfunction "1_1") (pintype "bidirectional"))
      (node (ref "C62") (pin "1") (pinfunction "1_1") (pintype "bidirectional"))
      (node (ref "C69") (pin "1") (pinfunction "1_1") (pintype "bidirectional"))
      (node (ref "C7") (pin "1") (pinfunction "1_1") (pintype "bidirectional"))
      (node (ref "C70") (pin "1") (pinfunction "1_1") (pintype "bidirectional"))
      (node (ref "C76") (pin "1") (pinfunction "1_1") (pintype "bidirectional"))
      (node (ref "C77") (pin "1") (pinfunction "1_1") (pintype "bidirectional"))
      (node (ref "C78") (pin "1") (pinfunction "1_1") (pintype "bidirectional"))
      (node (ref "C8") (pin "1") (pinfunction "1_1") (pintype "bidirectional"))
      (node (ref "C80") (pin "1") (pinfunction "1_1") (pintype "bidirectional"))
      (node (ref "C81") (pin "1") (pinfunction "1_1") (pintype "bidirectional"))
      (node (ref "C82") (pin "1") (pinfunction "1_1") (pintype "bidirectional"))
      (node (ref "C83") (pin "1") (pinfunction "1_1") (pintype "bidirectional"))
      (node (ref "C84") (pin "1") (pinfunction "1_1") (pintype "bidirectional"))
      (node (ref "C85") (pin "1") (pinfunction "1_1") (pintype "bidirectional"))
      (node (ref "C86") (pin "1") (pinfunction "1_1") (pintype "bidirectional"))
      (node (ref "C87") (pin "1") (pinfunction "1_1") (pintype "bidirectional"))
      (node (ref "C88") (pin "1") (pinfunction "1_1") (pintype "bidirectional"))
      (node (ref "C89") (pin "1") (pinfunction "1_1") (pintype "bidirectional"))
      (node (ref "C90") (pin "1") (pinfunction "1_1") (pintype "bidirectional"))
      (node (ref "C91") (pin "1") (pinfunction "1_1") (pintype "bidirectional"))
      (node (ref "C92") (pin "1") (pinfunction "1_1") (pintype "bidirectional"))
      (node (ref "C93") (pin "1") (pinfunction "1_1") (pintype "bidirectional"))
      (node (ref "C94") (pin "1") (pinfunction "1_1") (pintype "bidirectional"))
      (node (ref "C95") (pin "1") (pinfunction "1_1") (pintype "bidirectional"))
      (node (ref "C96") (pin "1") (pinfunction "1_1") (pintype "bidirectional"))
      (node (ref "C97") (pin "1") (pinfunction "1_1") (pintype "bidirectional"))
      (node (ref "C98") (pin "1") (pinfunction "1_1") (pintype "bidirectional"))
      (node (ref "C99") (pin "1") (pinfunction "1_1") (pintype "bidirectional"))
      (node (ref "CN10") (pin "1") (pinfunction "1_1") (pintype "bidirectional"))
      (node (ref "CN11") (pin "6") (pinfunction "6_6") (pintype "bidirectional"))
      (node (ref "CN15") (pin "GND") (pinfunction "GND_GND") (pintype "bidirectional"))
      (node (ref "CN15") (pin "SHIELD1") (pinfunction "SHIELD_SHIELD1") (pintype "bidirectional"))
      (node (ref "CN15") (pin "SHIELD2") (pinfunction "SHIELD_SHIELD2") (pintype "bidirectional"))
      (node (ref "CN15") (pin "SHIELD3") (pinfunction "SHIELD_SHIELD3") (pintype "bidirectional"))
      (node (ref "CN15") (pin "SHIELD4") (pinfunction "SHIELD_SHIELD4") (pintype "bidirectional"))
      (node (ref "CN3") (pin "10") (pinfunction "10_10") (pintype "bidirectional"))
      (node (ref "CN3") (pin "6") (pinfunction "6_6") (pintype "bidirectional"))
      (node (ref "CN5") (pin "1") (pinfunction "1_1") (pintype "bidirectional"))
      (node (ref "CN7") (pin "1") (pinfunction "1_1") (pintype "bidirectional"))
      (node (ref "CN7") (pin "2") (pinfunction "1_2") (pintype "bidirectional"))
      (node (ref "R1") (pin "1") (pinfunction "1_1") (pintype "bidirectional"))
      (node (ref "R2") (pin "1") (pinfunction "1_1") (pintype "bidirectional"))
      (node (ref "R20") (pin "1") (pinfunction "1_1") (pintype "bidirectional"))
      (node (ref "R23") (pin "1") (pinfunction "1_1") (pintype "bidirectional"))
      (node (ref "R25") (pin "1") (pinfunction "1_1") (pintype "bidirectional"))
      (node (ref "R29") (pin "1") (pinfunction "1_1") (pintype "bidirectional"))
      (node (ref "R30") (pin "1") (pinfunction "1_1") (pintype "bidirectional"))
      (node (ref "R39") (pin "1") (pinfunction "1_1") (pintype "bidirectional"))
      (node (ref "R45") (pin "1") (pinfunction "1_1") (pintype "bidirectional"))
      (node (ref "R55") (pin "2") (pinfunction "2_2") (pintype "bidirectional"))
      (node (ref "R56") (pin "2") (pinfunction "2_2") (pintype "bidirectional"))
      (node (ref "R57") (pin "2") (pinfunction "2_2") (pintype "bidirectional"))
      (node (ref "R59") (pin "1") (pinfunction "1_1") (pintype "bidirectional"))
      (node (ref "TX1") (pin "4") (pinfunction "B2_4") (pintype "bidirectional"))
      (node (ref "U1") (pin "18") (pinfunction "DGND_18") (pintype "bidirectional"))
      (node (ref "U1") (pin "8") (pinfunction "PGND_8") (pintype "bidirectional"))
      (node (ref "U10") (pin "4") (pinfunction "GND_4") (pintype "bidirectional"))
      (node (ref "U13") (pin "1") (pinfunction "ADJ_1") (pintype "bidirectional"))
      (node (ref "U14") (pin "2") (pinfunction "GND_2") (pintype "bidirectional"))
      (node (ref "U15") (pin "2") (pinfunction "GND_2") (pintype "bidirectional"))
      (node (ref "U16") (pin "13") (pinfunction "GND_13") (pintype "bidirectional"))
      (node (ref "U16") (pin "5") (pinfunction "GND_5") (pintype "bidirectional"))
      (node (ref "U17") (pin "1") (pinfunction "GND_1") (pintype "bidirectional"))
      (node (ref "U18") (pin "5") (pinfunction "DGND_5") (pintype "bidirectional"))
      (node (ref "U2") (pin "12") (pinfunction "TEST_12") (pintype "bidirectional"))
      (node (ref "U2") (pin "13") (pinfunction "DEMP_13") (pintype "bidirectional"))
      (node (ref "U2") (pin "15") (pinfunction "FMT_15") (pintype "bidirectional"))
      (node (ref "U2") (pin "4") (pinfunction "DGND_4") (pintype "bidirectional"))
      (node (ref "U20") (pin "2") (pinfunction "GND_2") (pintype "bidirectional"))
      (node (ref "U22") (pin "12") (pinfunction "TEST_12") (pintype "bidirectional"))
      (node (ref "U22") (pin "13") (pinfunction "DEMP_13") (pintype "bidirectional"))
      (node (ref "U22") (pin "15") (pinfunction "FMT_15") (pintype "bidirectional"))
      (node (ref "U22") (pin "4") (pinfunction "DGND_4") (pintype "bidirectional"))
      (node (ref "U24") (pin "5") (pinfunction "DGND_5") (pintype "bidirectional"))
      (node (ref "U27") (pin "12") (pinfunction "TEST_12") (pintype "bidirectional"))
      (node (ref "U27") (pin "13") (pinfunction "DEMP_13") (pintype "bidirectional"))
      (node (ref "U27") (pin "15") (pinfunction "FMT_15") (pintype "bidirectional"))
      (node (ref "U27") (pin "4") (pinfunction "DGND_4") (pintype "bidirectional"))
      (node (ref "U29") (pin "15") (pinfunction "VSS_15") (pintype "bidirectional"))
      (node (ref "U30") (pin "4") (pinfunction "GND_4") (pintype "bidirectional"))
      (node (ref "U6") (pin "5") (pinfunction "DGND_5") (pintype "bidirectional"))
      (node (ref "U9") (pin "108") (pinfunction "GND_108") (pintype "bidirectional"))
      (node (ref "U9") (pin "118") (pinfunction "GND_118") (pintype "bidirectional"))
      (node (ref "U9") (pin "123") (pinfunction "GND_123") (pintype "bidirectional"))
      (node (ref "U9") (pin "131") (pinfunction "GND_131") (pintype "bidirectional"))
      (node (ref "U9") (pin "140") (pinfunction "GND_140") (pintype "bidirectional"))
      (node (ref "U9") (pin "19") (pinfunction "GND_19") (pintype "bidirectional"))
      (node (ref "U9") (pin "22") (pinfunction "GND_22") (pintype "bidirectional"))
      (node (ref "U9") (pin "27") (pinfunction "GND_27") (pintype "bidirectional"))
      (node (ref "U9") (pin "36") (pinfunction "GND_36") (pintype "bidirectional"))
      (node (ref "U9") (pin "4") (pinfunction "GND_4") (pintype "bidirectional"))
      (node (ref "U9") (pin "41") (pinfunction "GND_41") (pintype "bidirectional"))
      (node (ref "U9") (pin "48") (pinfunction "GND_48") (pintype "bidirectional"))
      (node (ref "U9") (pin "57") (pinfunction "GND_57") (pintype "bidirectional"))
      (node (ref "U9") (pin "63") (pinfunction "GND_63") (pintype "bidirectional"))
      (node (ref "U9") (pin "79") (pinfunction "GND_79") (pintype "bidirectional"))
      (node (ref "U9") (pin "82") (pinfunction "GND_82") (pintype "bidirectional"))
      (node (ref "U9") (pin "95") (pinfunction "GND_95") (pintype "bidirectional"))
      (node (ref "U9") (pin "96") (pinfunction "MSEL1_96") (pintype "bidirectional"))
      (node (ref "U9") (pin "GND") (pinfunction "GND_GND") (pintype "bidirectional"))
      (node (ref "XTAL1") (pin "2") (pinfunction "GND_2") (pintype "bidirectional"))
      (node (ref "XTAL1") (pin "4") (pinfunction "GND_4") (pintype "bidirectional"))
    )
    (net (code "37") (name "NCE") (class "Default")
      (node (ref "R39") (pin "2") (pinfunction "2_2") (pintype "bidirectional"))
      (node (ref "U9") (pin "21") (pinfunction "NCE_21") (pintype "bidirectional"))
    )
    (net (code "38") (name "NCONFIG") (class "Default")
      (node (ref "R38") (pin "2") (pinfunction "2_2") (pintype "bidirectional"))
      (node (ref "U9") (pin "14") (pinfunction "NCONFIG_14") (pintype "bidirectional"))
    )
    (net (code "39") (name "NCSO") (class "Default")
      (node (ref "U10") (pin "1") (pinfunction "NCS_1") (pintype "bidirectional"))
      (node (ref "U9") (pin "8") (pinfunction "NCSO_8") (pintype "bidirectional"))
    )
    (net (code "40") (name "NSTATUS") (class "Default")
      (node (ref "R37") (pin "2") (pinfunction "2_2") (pintype "bidirectional"))
      (node (ref "U9") (pin "9") (pinfunction "NSTATUS_9") (pintype "bidirectional"))
    )
    (net (code "41") (name "Net-(C10-Pad2)") (class "Default")
      (node (ref "C10") (pin "2") (pinfunction "2_2") (pintype "bidirectional"))
      (node (ref "R7") (pin "1") (pinfunction "1_1") (pintype "bidirectional"))
      (node (ref "R8") (pin "2") (pinfunction "2_2") (pintype "bidirectional"))
    )
    (net (code "42") (name "Net-(C11-Pad2)") (class "Default")
      (node (ref "C11") (pin "2") (pinfunction "2_2") (pintype "bidirectional"))
      (node (ref "R17") (pin "2") (pinfunction "2_2") (pintype "bidirectional"))
      (node (ref "R8") (pin "1") (pinfunction "1_1") (pintype "bidirectional"))
      (node (ref "R9") (pin "1") (pinfunction "1_1") (pintype "bidirectional"))
    )
    (net (code "43") (name "Net-(C12-Pad2)") (class "Default")
      (node (ref "C12") (pin "2") (pinfunction "2_2") (pintype "bidirectional"))
      (node (ref "R10") (pin "1") (pinfunction "1_1") (pintype "bidirectional"))
      (node (ref "R11") (pin "2") (pinfunction "2_2") (pintype "bidirectional"))
    )
    (net (code "44") (name "Net-(C13-Pad2)") (class "Default")
      (node (ref "C13") (pin "2") (pinfunction "2_2") (pintype "bidirectional"))
      (node (ref "R11") (pin "1") (pinfunction "1_1") (pintype "bidirectional"))
      (node (ref "R16") (pin "2") (pinfunction "2_2") (pintype "bidirectional"))
      (node (ref "R21") (pin "1") (pinfunction "1_1") (pintype "bidirectional"))
    )
    (net (code "45") (name "Net-(C14-Pad2)") (class "Default")
      (node (ref "C14") (pin "2") (pinfunction "2_2") (pintype "bidirectional"))
      (node (ref "R12") (pin "1") (pinfunction "1_1") (pintype "bidirectional"))
      (node (ref "R18") (pin "2") (pinfunction "2_2") (pintype "bidirectional"))
    )
    (net (code "46") (name "Net-(C15-Pad2)") (class "Default")
      (node (ref "C15") (pin "2") (pinfunction "2_2") (pintype "bidirectional"))
      (node (ref "R14") (pin "1") (pinfunction "1_1") (pintype "bidirectional"))
      (node (ref "R19") (pin "2") (pinfunction "2_2") (pintype "bidirectional"))
    )
    (net (code "47") (name "Net-(C31-Pad2)") (class "Default")
      (node (ref "C31") (pin "2") (pinfunction "2_2") (pintype "bidirectional"))
      (node (ref "R12") (pin "2") (pinfunction "2_2") (pintype "bidirectional"))
      (node (ref "R13") (pin "1") (pinfunction "1_1") (pintype "bidirectional"))
    )
    (net (code "48") (name "Net-(C34-Pad2)") (class "Default")
      (node (ref "C34") (pin "2") (pinfunction "2_2") (pintype "bidirectional"))
      (node (ref "R14") (pin "2") (pinfunction "2_2") (pintype "bidirectional"))
      (node (ref "R15") (pin "1") (pinfunction "1_1") (pintype "bidirectional"))
    )
    (net (code "49") (name "Net-(C54-Pad1)") (class "Default")
      (node (ref "C54") (pin "1") (pinfunction "1_1") (pintype "bidirectional"))
      (node (ref "CN2") (pin "1") (pinfunction "1_1") (pintype "bidirectional"))
    )
    (net (code "50") (name "Net-(C64-Pad2)") (class "Default")
      (node (ref "C64") (pin "2") (pinfunction "2_2") (pintype "bidirectional"))
      (node (ref "R31") (pin "2") (pinfunction "2_2") (pintype "bidirectional"))
      (node (ref "R32") (pin "1") (pinfunction "1_1") (pintype "bidirectional"))
    )
    (net (code "51") (name "Net-(C66-Pad2)") (class "Default")
      (node (ref "C66") (pin "2") (pinfunction "2_2") (pintype "bidirectional"))
      (node (ref "R33") (pin "2") (pinfunction "2_2") (pintype "bidirectional"))
      (node (ref "R34") (pin "1") (pinfunction "1_1") (pintype "bidirectional"))
    )
    (net (code "52") (name "Net-(C101-Pad2)") (class "Default")
      (node (ref "C101") (pin "2") (pinfunction "2_2") (pintype "bidirectional"))
      (node (ref "R46") (pin "1") (pinfunction "1_1") (pintype "bidirectional"))
      (node (ref "R50") (pin "2") (pinfunction "2_2") (pintype "bidirectional"))
    )
    (net (code "53") (name "Net-(C102-Pad2)") (class "Default")
      (node (ref "C102") (pin "2") (pinfunction "2_2") (pintype "bidirectional"))
      (node (ref "R47") (pin "1") (pinfunction "1_1") (pintype "bidirectional"))
      (node (ref "R50") (pin "1") (pinfunction "1_1") (pintype "bidirectional"))
      (node (ref "R65") (pin "2") (pinfunction "2_2") (pintype "bidirectional"))
    )
    (net (code "54") (name "Net-(C103-Pad2)") (class "Default")
      (node (ref "C103") (pin "2") (pinfunction "2_2") (pintype "bidirectional"))
      (node (ref "R48") (pin "1") (pinfunction "1_1") (pintype "bidirectional"))
      (node (ref "R58") (pin "2") (pinfunction "2_2") (pintype "bidirectional"))
    )
    (net (code "55") (name "Net-(C104-Pad2)") (class "Default")
      (node (ref "C104") (pin "2") (pinfunction "2_2") (pintype "bidirectional"))
      (node (ref "R49") (pin "1") (pinfunction "1_1") (pintype "bidirectional"))
      (node (ref "R58") (pin "1") (pinfunction "1_1") (pintype "bidirectional"))
      (node (ref "R64") (pin "2") (pinfunction "2_2") (pintype "bidirectional"))
    )
    (net (code "56") (name "Net-(C105-Pad2)") (class "Default")
      (node (ref "C105") (pin "2") (pinfunction "2_2") (pintype "bidirectional"))
      (node (ref "R31") (pin "1") (pinfunction "1_1") (pintype "bidirectional"))
      (node (ref "R35") (pin "2") (pinfunction "2_2") (pintype "bidirectional"))
    )
    (net (code "57") (name "Net-(C106-Pad2)") (class "Default")
      (node (ref "C106") (pin "2") (pinfunction "2_2") (pintype "bidirectional"))
      (node (ref "R33") (pin "1") (pinfunction "1_1") (pintype "bidirectional"))
      (node (ref "R36") (pin "2") (pinfunction "2_2") (pintype "bidirectional"))
    )
    (net (code "58") (name "Net-(C111-Pad1)") (class "Default")
      (node (ref "C111") (pin "1") (pinfunction "1_1") (pintype "bidirectional"))
      (node (ref "C72") (pin "1") (pinfunction "1_1") (pintype "bidirectional"))
      (node (ref "FB18") (pin "2") (pinfunction "2_2") (pintype "bidirectional"))
      (node (ref "U12") (pin "2") (pinfunction "VIN_2") (pintype "bidirectional"))
      (node (ref "U12") (pin "4") (pinfunction "VIN_4") (pintype "bidirectional"))
    )
    (net (code "59") (name "Net-(C126-Pad2)") (class "Default")
      (node (ref "C126") (pin "2") (pinfunction "2_2") (pintype "bidirectional"))
      (node (ref "R66") (pin "2") (pinfunction "2_2") (pintype "bidirectional"))
      (node (ref "R67") (pin "1") (pinfunction "1_1") (pintype "bidirectional"))
    )
    (net (code "60") (name "Net-(C128-Pad2)") (class "Default")
      (node (ref "C128") (pin "2") (pinfunction "2_2") (pintype "bidirectional"))
      (node (ref "R68") (pin "2") (pinfunction "2_2") (pintype "bidirectional"))
      (node (ref "R69") (pin "1") (pinfunction "1_1") (pintype "bidirectional"))
    )
    (net (code "61") (name "Net-(C132-Pad2)") (class "Default")
      (node (ref "C132") (pin "2") (pinfunction "2_2") (pintype "bidirectional"))
      (node (ref "R72") (pin "1") (pinfunction "1_1") (pintype "bidirectional"))
      (node (ref "R76") (pin "2") (pinfunction "2_2") (pintype "bidirectional"))
    )
    (net (code "62") (name "Net-(C133-Pad2)") (class "Default")
      (node (ref "C133") (pin "2") (pinfunction "2_2") (pintype "bidirectional"))
      (node (ref "R73") (pin "1") (pinfunction "1_1") (pintype "bidirectional"))
      (node (ref "R76") (pin "1") (pinfunction "1_1") (pintype "bidirectional"))
      (node (ref "R83") (pin "2") (pinfunction "2_2") (pintype "bidirectional"))
    )
    (net (code "63") (name "Net-(C134-Pad2)") (class "Default")
      (node (ref "C134") (pin "2") (pinfunction "2_2") (pintype "bidirectional"))
      (node (ref "R74") (pin "1") (pinfunction "1_1") (pintype "bidirectional"))
      (node (ref "R77") (pin "2") (pinfunction "2_2") (pintype "bidirectional"))
    )
    (net (code "64") (name "Net-(C135-Pad2)") (class "Default")
      (node (ref "C135") (pin "2") (pinfunction "2_2") (pintype "bidirectional"))
      (node (ref "R75") (pin "1") (pinfunction "1_1") (pintype "bidirectional"))
      (node (ref "R77") (pin "1") (pinfunction "1_1") (pintype "bidirectional"))
      (node (ref "R82") (pin "2") (pinfunction "2_2") (pintype "bidirectional"))
    )
    (net (code "65") (name "Net-(C136-Pad2)") (class "Default")
      (node (ref "C136") (pin "2") (pinfunction "2_2") (pintype "bidirectional"))
      (node (ref "R66") (pin "1") (pinfunction "1_1") (pintype "bidirectional"))
      (node (ref "R70") (pin "2") (pinfunction "2_2") (pintype "bidirectional"))
    )
    (net (code "66") (name "Net-(C137-Pad2)") (class "Default")
      (node (ref "C137") (pin "2") (pinfunction "2_2") (pintype "bidirectional"))
      (node (ref "R68") (pin "1") (pinfunction "1_1") (pintype "bidirectional"))
      (node (ref "R71") (pin "2") (pinfunction "2_2") (pintype "bidirectional"))
    )
    (net (code "67") (name "Net-(CN1-Pad1)") (class "Default")
      (node (ref "CN1") (pin "1") (pinfunction "1_1") (pintype "bidirectional"))
      (node (ref "R7") (pin "2") (pinfunction "2_2") (pintype "bidirectional"))
    )
    (net (code "68") (name "Net-(CN1-Pad3)") (class "Default")
      (node (ref "CN1") (pin "3") (pinfunction "3_3") (pintype "bidirectional"))
      (node (ref "R9") (pin "2") (pinfunction "2_2") (pintype "bidirectional"))
    )
    (net (code "69") (name "Net-(CN1-Pad5)") (class "Default")
      (node (ref "CN1") (pin "5") (pinfunction "5_5") (pintype "bidirectional"))
      (node (ref "R10") (pin "2") (pinfunction "2_2") (pintype "bidirectional"))
    )
    (net (code "70") (name "Net-(CN1-Pad7)") (class "Default")
      (node (ref "CN1") (pin "7") (pinfunction "7_7") (pintype "bidirectional"))
      (node (ref "R21") (pin "2") (pinfunction "2_2") (pintype "bidirectional"))
    )
    (net (code "71") (name "Net-(CN4-Pad1)") (class "Default")
      (node (ref "CN4") (pin "1") (pinfunction "1_1") (pintype "bidirectional"))
      (node (ref "R46") (pin "2") (pinfunction "2_2") (pintype "bidirectional"))
    )
    (net (code "72") (name "Net-(CN4-Pad3)") (class "Default")
      (node (ref "CN4") (pin "3") (pinfunction "3_3") (pintype "bidirectional"))
      (node (ref "R47") (pin "2") (pinfunction "2_2") (pintype "bidirectional"))
    )
    (net (code "73") (name "Net-(CN4-Pad5)") (class "Default")
      (node (ref "CN4") (pin "5") (pinfunction "5_5") (pintype "bidirectional"))
      (node (ref "R48") (pin "2") (pinfunction "2_2") (pintype "bidirectional"))
    )
    (net (code "74") (name "Net-(CN4-Pad7)") (class "Default")
      (node (ref "CN4") (pin "7") (pinfunction "7_7") (pintype "bidirectional"))
      (node (ref "R49") (pin "2") (pinfunction "2_2") (pintype "bidirectional"))
    )
    (net (code "75") (name "Net-(CN9-Pad1)") (class "Default")
      (node (ref "CN9") (pin "1") (pinfunction "1_1") (pintype "bidirectional"))
      (node (ref "R72") (pin "2") (pinfunction "2_2") (pintype "bidirectional"))
    )
    (net (code "76") (name "Net-(CN9-Pad3)") (class "Default")
      (node (ref "CN9") (pin "3") (pinfunction "3_3") (pintype "bidirectional"))
      (node (ref "R73") (pin "2") (pinfunction "2_2") (pintype "bidirectional"))
    )
    (net (code "77") (name "Net-(CN9-Pad5)") (class "Default")
      (node (ref "CN9") (pin "5") (pinfunction "5_5") (pintype "bidirectional"))
      (node (ref "R74") (pin "2") (pinfunction "2_2") (pintype "bidirectional"))
    )
    (net (code "78") (name "Net-(CN9-Pad7)") (class "Default")
      (node (ref "CN9") (pin "7") (pinfunction "7_7") (pintype "bidirectional"))
      (node (ref "R75") (pin "2") (pinfunction "2_2") (pintype "bidirectional"))
    )
    (net (code "79") (name "Net-(TX1-A1)") (class "Default")
      (node (ref "C54") (pin "2") (pinfunction "2_2") (pintype "bidirectional"))
      (node (ref "TX1") (pin "1") (pinfunction "A1_1") (pintype "bidirectional"))
    )
    (net (code "80") (name "Net-(TX1-A2)") (class "Default")
      (node (ref "CN2") (pin "2") (pinfunction "5_2") (pintype "bidirectional"))
      (node (ref "CN2") (pin "3") (pinfunction "5_3") (pintype "bidirectional"))
      (node (ref "CN2") (pin "4") (pinfunction "5_4") (pintype "bidirectional"))
      (node (ref "CN2") (pin "5") (pinfunction "5_5") (pintype "bidirectional"))
      (node (ref "TX1") (pin "3") (pinfunction "A2_3") (pintype "bidirectional"))
    )
    (net (code "81") (name "Net-(TX1-B1)") (class "Default")
      (node (ref "C3") (pin "1") (pinfunction "1_1") (pintype "bidirectional"))
      (node (ref "R1") (pin "2") (pinfunction "2_2") (pintype "bidirectional"))
      (node (ref "TX1") (pin "6") (pinfunction "B1_6") (pintype "bidirectional"))
    )
    (net (code "82") (name "Net-(U1-DIN)") (class "Default")
      (node (ref "R20") (pin "2") (pinfunction "2_2") (pintype "bidirectional"))
      (node (ref "U1") (pin "13") (pinfunction "DIN_13") (pintype "bidirectional"))
    )
    (net (code "83") (name "Net-(U1-RX0)") (class "Default")
      (node (ref "C3") (pin "2") (pinfunction "2_2") (pintype "bidirectional"))
      (node (ref "U1") (pin "20") (pinfunction "RX0_20") (pintype "bidirectional"))
    )
    (net (code "84") (name "Net-(U1-TX0)") (class "Default")
      (node (ref "R2") (pin "2") (pinfunction "2_2") (pintype "bidirectional"))
      (node (ref "U1") (pin "17") (pinfunction "TX0_17") (pintype "bidirectional"))
    )
    (net (code "85") (name "Net-(U1-XIN)") (class "Default")
      (node (ref "C5") (pin "2") (pinfunction "2_2") (pintype "bidirectional"))
      (node (ref "U1") (pin "11") (pinfunction "XIN_11") (pintype "bidirectional"))
      (node (ref "XTAL1") (pin "1") (pinfunction "P$1_1") (pintype "bidirectional"))
    )
    (net (code "86") (name "Net-(U1-XOP)") (class "Default")
      (node (ref "C4") (pin "2") (pinfunction "2_2") (pintype "bidirectional"))
      (node (ref "U1") (pin "10") (pinfunction "XOP_10") (pintype "bidirectional"))
      (node (ref "XTAL1") (pin "3") (pinfunction "P$2_3") (pintype "bidirectional"))
    )
    (net (code "87") (name "Net-(U2-VCC)") (class "Default")
      (node (ref "C27") (pin "2") (pinfunction "2_2") (pintype "bidirectional"))
      (node (ref "C28") (pin "2") (pinfunction "2_2") (pintype "bidirectional"))
      (node (ref "C55") (pin "2") (pinfunction "2_2") (pintype "bidirectional"))
      (node (ref "FB6") (pin "1") (pinfunction "1_1") (pintype "bidirectional"))
      (node (ref "U2") (pin "6") (pinfunction "VCC_6") (pintype "bidirectional"))
    )
    (net (code "88") (name "Net-(U2-VCOM)") (class "Default")
      (node (ref "C29") (pin "2") (pinfunction "2_2") (pintype "bidirectional"))
      (node (ref "C30") (pin "2") (pinfunction "2_2") (pintype "bidirectional"))
      (node (ref "U2") (pin "10") (pinfunction "VCOM_10") (pintype "bidirectional"))
    )
    (net (code "89") (name "Net-(U2-VOUT_L)") (class "Default")
      (node (ref "C14") (pin "1") (pinfunction "1_1") (pintype "bidirectional"))
      (node (ref "U2") (pin "7") (pinfunction "VOUT_L_7") (pintype "bidirectional"))
    )
    (net (code "90") (name "Net-(U2-VOUT_R)") (class "Default")
      (node (ref "C15") (pin "1") (pinfunction "1_1") (pintype "bidirectional"))
      (node (ref "U2") (pin "8") (pinfunction "VOUT_R_8") (pintype "bidirectional"))
    )
    (net (code "91") (name "Net-(U3A-+)") (class "Default")
      (node (ref "C33") (pin "1") (pinfunction "1_1") (pintype "bidirectional"))
      (node (ref "R13") (pin "2") (pinfunction "2_2") (pintype "bidirectional"))
      (node (ref "U3") (pin "3") (pinfunction "+_3") (pintype "bidirectional"))
    )
    (net (code "92") (name "Net-(U3A--)") (class "Default")
      (node (ref "C31") (pin "1") (pinfunction "1_1") (pintype "bidirectional"))
      (node (ref "U3") (pin "1") (pinfunction "OUT_1") (pintype "bidirectional"))
      (node (ref "U3") (pin "2") (pinfunction "-_2") (pintype "bidirectional"))
      (node (ref "U6") (pin "16") (pinfunction "VINL_16") (pintype "bidirectional"))
    )
    (net (code "93") (name "Net-(U3B-+)") (class "Default")
      (node (ref "C32") (pin "1") (pinfunction "1_1") (pintype "bidirectional"))
      (node (ref "R15") (pin "2") (pinfunction "2_2") (pintype "bidirectional"))
      (node (ref "U3") (pin "5") (pinfunction "+_5") (pintype "bidirectional"))
    )
    (net (code "94") (name "Net-(U3B--)") (class "Default")
      (node (ref "C34") (pin "1") (pinfunction "1_1") (pintype "bidirectional"))
      (node (ref "U3") (pin "6") (pinfunction "-_6") (pintype "bidirectional"))
      (node (ref "U3") (pin "7") (pinfunction "OUT_7") (pintype "bidirectional"))
      (node (ref "U6") (pin "9") (pinfunction "VINR_9") (pintype "bidirectional"))
    )
    (net (code "95") (name "Net-(U4-ADJ)") (class "Default")
      (node (ref "R28") (pin "1") (pinfunction "1_1") (pintype "bidirectional"))
      (node (ref "R29") (pin "2") (pinfunction "2_2") (pintype "bidirectional"))
      (node (ref "U4") (pin "1") (pinfunction "ADJ_1") (pintype "bidirectional"))
    )
    (net (code "96") (name "Net-(U5-ADJ)") (class "Default")
      (node (ref "R24") (pin "1") (pinfunction "1_1") (pintype "bidirectional"))
      (node (ref "R25") (pin "2") (pinfunction "2_2") (pintype "bidirectional"))
      (node (ref "U5") (pin "1") (pinfunction "ADJ_1") (pintype "bidirectional"))
    )
    (net (code "97") (name "Net-(U6-VA+)") (class "Default")
      (node (ref "C39") (pin "2") (pinfunction "2_2") (pintype "bidirectional"))
      (node (ref "C42") (pin "2") (pinfunction "2_2") (pintype "bidirectional"))
      (node (ref "FB3") (pin "2") (pinfunction "2_2") (pintype "bidirectional"))
      (node (ref "U6") (pin "12") (pinfunction "VA+_12") (pintype "bidirectional"))
    )
    (net (code "98") (name "Net-(U6-VA-)") (class "Default")
      (node (ref "C1") (pin "2") (pinfunction "2_2") (pintype "bidirectional"))
      (node (ref "C41") (pin "2") (pinfunction "2_2") (pintype "bidirectional"))
      (node (ref "FB1") (pin "2") (pinfunction "2_2") (pintype "bidirectional"))
      (node (ref "U6") (pin "13") (pinfunction "VA-_13") (pintype "bidirectional"))
    )
    (net (code "99") (name "Net-(U6-VD+)") (class "Default")
      (node (ref "C40") (pin "2") (pinfunction "2_2") (pintype "bidirectional"))
      (node (ref "FB4") (pin "1") (pinfunction "1_1") (pintype "bidirectional"))
      (node (ref "U6") (pin "4") (pinfunction "VD+_4") (pintype "bidirectional"))
    )
    (net (code "100") (name "Net-(U6-VOUTL)") (class "Default")
      (node (ref "U6") (pin "14") (pinfunction "VOUTL_14") (pintype "bidirectional"))
      (node (ref "U7") (pin "3") (pinfunction "+_3") (pintype "bidirectional"))
    )
    (net (code "101") (name "Net-(U6-VOUTR)") (class "Default")
      (node (ref "U6") (pin "11") (pinfunction "VOUTR_11") (pintype "bidirectional"))
      (node (ref "U8") (pin "3") (pinfunction "+_3") (pintype "bidirectional"))
    )
    (net (code "102") (name "Net-(U7A--)") (class "Default")
      (node (ref "C10") (pin "1") (pinfunction "1_1") (pintype "bidirectional"))
      (node (ref "R3") (pin "1") (pinfunction "1_1") (pintype "bidirectional"))
      (node (ref "U7") (pin "1") (pinfunction "OUT_1") (pintype "bidirectional"))
      (node (ref "U7") (pin "2") (pinfunction "-_2") (pintype "bidirectional"))
    )
    (net (code "103") (name "Net-(U7B--)") (class "Default")
      (node (ref "R3") (pin "2") (pinfunction "2_2") (pintype "bidirectional"))
      (node (ref "R4") (pin "1") (pinfunction "1_1") (pintype "bidirectional"))
      (node (ref "U7") (pin "6") (pinfunction "-_6") (pintype "bidirectional"))
    )
    (net (code "104") (name "Net-(U7B-OUT)") (class "Default")
      (node (ref "C11") (pin "1") (pinfunction "1_1") (pintype "bidirectional"))
      (node (ref "R4") (pin "2") (pinfunction "2_2") (pintype "bidirectional"))
      (node (ref "U7") (pin "7") (pinfunction "OUT_7") (pintype "bidirectional"))
    )
    (net (code "105") (name "Net-(U8A--)") (class "Default")
      (node (ref "C12") (pin "1") (pinfunction "1_1") (pintype "bidirectional"))
      (node (ref "R5") (pin "1") (pinfunction "1_1") (pintype "bidirectional"))
      (node (ref "U8") (pin "1") (pinfunction "OUT_1") (pintype "bidirectional"))
      (node (ref "U8") (pin "2") (pinfunction "-_2") (pintype "bidirectional"))
    )
    (net (code "106") (name "Net-(U8B--)") (class "Default")
      (node (ref "R5") (pin "2") (pinfunction "2_2") (pintype "bidirectional"))
      (node (ref "R6") (pin "1") (pinfunction "1_1") (pintype "bidirectional"))
      (node (ref "U8") (pin "6") (pinfunction "-_6") (pintype "bidirectional"))
    )
    (net (code "107") (name "Net-(U8B-OUT)") (class "Default")
      (node (ref "C13") (pin "1") (pinfunction "1_1") (pintype "bidirectional"))
      (node (ref "R6") (pin "2") (pinfunction "2_2") (pintype "bidirectional"))
      (node (ref "U8") (pin "7") (pinfunction "OUT_7") (pintype "bidirectional"))
    )
    (net (code "108") (name "Net-(U9G-CNFIG_DN)") (class "Default")
      (node (ref "R41") (pin "2") (pinfunction "2_2") (pintype "bidirectional"))
      (node (ref "U9") (pin "92") (pinfunction "CNFIG_DN_92") (pintype "bidirectional"))
    )
    (net (code "109") (name "Net-(U9G-IO52)") (class "Default")
      (node (ref "R42") (pin "2") (pinfunction "2_2") (pintype "bidirectional"))
      (node (ref "U9") (pin "98") (pinfunction "IO52_98") (pintype "bidirectional"))
    )
    (net (code "110") (name "Net-(U10-DATA)") (class "Default")
      (node (ref "R40") (pin "1") (pinfunction "1_1") (pintype "bidirectional"))
      (node (ref "U10") (pin "2") (pinfunction "DATA_2") (pintype "bidirectional"))
    )
    (net (code "111") (name "Net-(U11-ADJ)") (class "Default")
      (node (ref "R26") (pin "1") (pinfunction "1_1") (pintype "bidirectional"))
      (node (ref "R27") (pin "2") (pinfunction "2_2") (pintype "bidirectional"))
      (node (ref "U11") (pin "1") (pinfunction "ADJ_1") (pintype "bidirectional"))
    )
    (net (code "112") (name "Net-(U11-VIN)") (class "Default")
      (node (ref "C110") (pin "2") (pinfunction "2_2") (pintype "bidirectional"))
      (node (ref "C71") (pin "2") (pinfunction "2_2") (pintype "bidirectional"))
      (node (ref "FB2") (pin "2") (pinfunction "2_2") (pintype "bidirectional"))
      (node (ref "U11") (pin "3") (pinfunction "VIN_3") (pintype "bidirectional"))
    )
    (net (code "113") (name "Net-(U12-ADJ)") (class "Default")
      (node (ref "R51") (pin "2") (pinfunction "2_2") (pintype "bidirectional"))
      (node (ref "R52") (pin "1") (pinfunction "1_1") (pintype "bidirectional"))
      (node (ref "U12") (pin "1") (pinfunction "ADJ_1") (pintype "bidirectional"))
    )
    (net (code "114") (name "Net-(U15-D+_IN)") (class "Default")
      (node (ref "U15") (pin "1") (pinfunction "D+_IN_1") (pintype "bidirectional"))
      (node (ref "U16") (pin "8") (pinfunction "D+_8") (pintype "bidirectional"))
    )
    (net (code "115") (name "Net-(U15-D+_OUT)") (class "Default")
      (node (ref "CN15") (pin "D+") (pinfunction "D+_D+") (pintype "bidirectional"))
      (node (ref "U15") (pin "6") (pinfunction "D+_OUT_6") (pintype "bidirectional"))
    )
    (net (code "116") (name "Net-(U15-D-OUT)") (class "Default")
      (node (ref "CN15") (pin "D-") (pinfunction "D-_D-") (pintype "bidirectional"))
      (node (ref "U15") (pin "4") (pinfunction "D-OUT_4") (pintype "bidirectional"))
    )
    (net (code "117") (name "Net-(U15-D-_IN)") (class "Default")
      (node (ref "U15") (pin "3") (pinfunction "D-_IN_3") (pintype "bidirectional"))
      (node (ref "U16") (pin "9") (pinfunction "D-_9") (pintype "bidirectional"))
    )
    (net (code "118") (name "Net-(U16-~{CTS})") (class "Default")
      (node (ref "R30") (pin "2") (pinfunction "2_2") (pintype "bidirectional"))
      (node (ref "U16") (pin "6") (pinfunction "~{CTS}_6") (pintype "bidirectional"))
    )
    (net (code "119") (name "Net-(U16-~{RESET})") (class "Default")
      (node (ref "R22") (pin "1") (pinfunction "1_1") (pintype "bidirectional"))
      (node (ref "U16") (pin "11") (pinfunction "~{RESET}_11") (pintype "bidirectional"))
    )
    (net (code "120") (name "Net-(U17-VIN)") (class "Default")
      (node (ref "C116") (pin "2") (pinfunction "2_2") (pintype "bidirectional"))
      (node (ref "C69") (pin "2") (pinfunction "2_2") (pintype "bidirectional"))
      (node (ref "FB19") (pin "2") (pinfunction "2_2") (pintype "bidirectional"))
      (node (ref "U17") (pin "3") (pinfunction "VIN_3") (pintype "bidirectional"))
    )
    (net (code "121") (name "Net-(U18-VA+)") (class "Default")
      (node (ref "C19") (pin "2") (pinfunction "2_2") (pintype "bidirectional"))
      (node (ref "C51") (pin "2") (pinfunction "2_2") (pintype "bidirectional"))
      (node (ref "FB7") (pin "2") (pinfunction "2_2") (pintype "bidirectional"))
      (node (ref "U18") (pin "12") (pinfunction "VA+_12") (pintype "bidirectional"))
    )
    (net (code "122") (name "Net-(U18-VA-)") (class "Default")
      (node (ref "C18") (pin "2") (pinfunction "2_2") (pintype "bidirectional"))
      (node (ref "C21") (pin "2") (pinfunction "2_2") (pintype "bidirectional"))
      (node (ref "FB5") (pin "2") (pinfunction "2_2") (pintype "bidirectional"))
      (node (ref "U18") (pin "13") (pinfunction "VA-_13") (pintype "bidirectional"))
    )
    (net (code "123") (name "Net-(U18-VD+)") (class "Default")
      (node (ref "C20") (pin "2") (pinfunction "2_2") (pintype "bidirectional"))
      (node (ref "FB8") (pin "1") (pinfunction "1_1") (pintype "bidirectional"))
      (node (ref "U18") (pin "4") (pinfunction "VD+_4") (pintype "bidirectional"))
    )
    (net (code "124") (name "Net-(U18-VINL)") (class "Default")
      (node (ref "C64") (pin "1") (pinfunction "1_1") (pintype "bidirectional"))
      (node (ref "U18") (pin "16") (pinfunction "VINL_16") (pintype "bidirectional"))
      (node (ref "U23") (pin "1") (pinfunction "OUT_1") (pintype "bidirectional"))
      (node (ref "U23") (pin "2") (pinfunction "-_2") (pintype "bidirectional"))
    )
    (net (code "125") (name "Net-(U18-VINR)") (class "Default")
      (node (ref "C66") (pin "1") (pinfunction "1_1") (pintype "bidirectional"))
      (node (ref "U18") (pin "9") (pinfunction "VINR_9") (pintype "bidirectional"))
      (node (ref "U23") (pin "6") (pinfunction "-_6") (pintype "bidirectional"))
      (node (ref "U23") (pin "7") (pinfunction "OUT_7") (pintype "bidirectional"))
    )
    (net (code "126") (name "Net-(U18-VOUTL)") (class "Default")
      (node (ref "U18") (pin "14") (pinfunction "VOUTL_14") (pintype "bidirectional"))
      (node (ref "U19") (pin "3") (pinfunction "+_3") (pintype "bidirectional"))
    )
    (net (code "127") (name "Net-(U18-VOUTR)") (class "Default")
      (node (ref "U18") (pin "11") (pinfunction "VOUTR_11") (pintype "bidirectional"))
      (node (ref "U21") (pin "3") (pinfunction "+_3") (pintype "bidirectional"))
    )
    (net (code "128") (name "Net-(U19A--)") (class "Default")
      (node (ref "C101") (pin "1") (pinfunction "1_1") (pintype "bidirectional"))
      (node (ref "R60") (pin "1") (pinfunction "1_1") (pintype "bidirectional"))
      (node (ref "U19") (pin "1") (pinfunction "OUT_1") (pintype "bidirectional"))
      (node (ref "U19") (pin "2") (pinfunction "-_2") (pintype "bidirectional"))
    )
    (net (code "129") (name "Net-(U19B--)") (class "Default")
      (node (ref "R60") (pin "2") (pinfunction "2_2") (pintype "bidirectional"))
      (node (ref "R61") (pin "1") (pinfunction "1_1") (pintype "bidirectional"))
      (node (ref "U19") (pin "6") (pinfunction "-_6") (pintype "bidirectional"))
    )
    (net (code "130") (name "Net-(U19B-OUT)") (class "Default")
      (node (ref "C102") (pin "1") (pinfunction "1_1") (pintype "bidirectional"))
      (node (ref "R61") (pin "2") (pinfunction "2_2") (pintype "bidirectional"))
      (node (ref "U19") (pin "7") (pinfunction "OUT_7") (pintype "bidirectional"))
    )
    (net (code "131") (name "Net-(U21A--)") (class "Default")
      (node (ref "C103") (pin "1") (pinfunction "1_1") (pintype "bidirectional"))
      (node (ref "R62") (pin "1") (pinfunction "1_1") (pintype "bidirectional"))
      (node (ref "U21") (pin "1") (pinfunction "OUT_1") (pintype "bidirectional"))
      (node (ref "U21") (pin "2") (pinfunction "-_2") (pintype "bidirectional"))
    )
    (net (code "132") (name "Net-(U21B--)") (class "Default")
      (node (ref "R62") (pin "2") (pinfunction "2_2") (pintype "bidirectional"))
      (node (ref "R63") (pin "1") (pinfunction "1_1") (pintype "bidirectional"))
      (node (ref "U21") (pin "6") (pinfunction "-_6") (pintype "bidirectional"))
    )
    (net (code "133") (name "Net-(U21B-OUT)") (class "Default")
      (node (ref "C104") (pin "1") (pinfunction "1_1") (pintype "bidirectional"))
      (node (ref "R63") (pin "2") (pinfunction "2_2") (pintype "bidirectional"))
      (node (ref "U21") (pin "7") (pinfunction "OUT_7") (pintype "bidirectional"))
    )
    (net (code "134") (name "Net-(U22-VCC)") (class "Default")
      (node (ref "C58") (pin "2") (pinfunction "2_2") (pintype "bidirectional"))
      (node (ref "C59") (pin "2") (pinfunction "2_2") (pintype "bidirectional"))
      (node (ref "C67") (pin "2") (pinfunction "2_2") (pintype "bidirectional"))
      (node (ref "FB9") (pin "1") (pinfunction "1_1") (pintype "bidirectional"))
      (node (ref "U22") (pin "6") (pinfunction "VCC_6") (pintype "bidirectional"))
    )
    (net (code "135") (name "Net-(U22-VCOM)") (class "Default")
      (node (ref "C60") (pin "2") (pinfunction "2_2") (pintype "bidirectional"))
      (node (ref "C61") (pin "2") (pinfunction "2_2") (pintype "bidirectional"))
      (node (ref "U22") (pin "10") (pinfunction "VCOM_10") (pintype "bidirectional"))
    )
    (net (code "136") (name "Net-(U22-VOUT_L)") (class "Default")
      (node (ref "C105") (pin "1") (pinfunction "1_1") (pintype "bidirectional"))
      (node (ref "U22") (pin "7") (pinfunction "VOUT_L_7") (pintype "bidirectional"))
    )
    (net (code "137") (name "Net-(U22-VOUT_R)") (class "Default")
      (node (ref "C106") (pin "1") (pinfunction "1_1") (pintype "bidirectional"))
      (node (ref "U22") (pin "8") (pinfunction "VOUT_R_8") (pintype "bidirectional"))
    )
    (net (code "138") (name "Net-(U23A-+)") (class "Default")
      (node (ref "C63") (pin "1") (pinfunction "1_1") (pintype "bidirectional"))
      (node (ref "R32") (pin "2") (pinfunction "2_2") (pintype "bidirectional"))
      (node (ref "U23") (pin "3") (pinfunction "+_3") (pintype "bidirectional"))
    )
    (net (code "139") (name "Net-(U23B-+)") (class "Default")
      (node (ref "C65") (pin "1") (pinfunction "1_1") (pintype "bidirectional"))
      (node (ref "R34") (pin "2") (pinfunction "2_2") (pintype "bidirectional"))
      (node (ref "U23") (pin "5") (pinfunction "+_5") (pintype "bidirectional"))
    )
    (net (code "140") (name "Net-(U24-VA+)") (class "Default")
      (node (ref "C108") (pin "2") (pinfunction "2_2") (pintype "bidirectional"))
      (node (ref "C115") (pin "2") (pinfunction "2_2") (pintype "bidirectional"))
      (node (ref "FB11") (pin "2") (pinfunction "2_2") (pintype "bidirectional"))
      (node (ref "U24") (pin "12") (pinfunction "VA+_12") (pintype "bidirectional"))
    )
    (net (code "141") (name "Net-(U24-VA-)") (class "Default")
      (node (ref "C107") (pin "2") (pinfunction "2_2") (pintype "bidirectional"))
      (node (ref "C114") (pin "2") (pinfunction "2_2") (pintype "bidirectional"))
      (node (ref "FB10") (pin "2") (pinfunction "2_2") (pintype "bidirectional"))
      (node (ref "U24") (pin "13") (pinfunction "VA-_13") (pintype "bidirectional"))
    )
    (net (code "142") (name "Net-(U24-VD+)") (class "Default")
      (node (ref "C109") (pin "2") (pinfunction "2_2") (pintype "bidirectional"))
      (node (ref "FB12") (pin "1") (pinfunction "1_1") (pintype "bidirectional"))
      (node (ref "U24") (pin "4") (pinfunction "VD+_4") (pintype "bidirectional"))
    )
    (net (code "143") (name "Net-(U24-VINL)") (class "Default")
      (node (ref "C126") (pin "1") (pinfunction "1_1") (pintype "bidirectional"))
      (node (ref "U24") (pin "16") (pinfunction "VINL_16") (pintype "bidirectional"))
      (node (ref "U28") (pin "1") (pinfunction "OUT_1") (pintype "bidirectional"))
      (node (ref "U28") (pin "2") (pinfunction "-_2") (pintype "bidirectional"))
    )
    (net (code "144") (name "Net-(U24-VINR)") (class "Default")
      (node (ref "C128") (pin "1") (pinfunction "1_1") (pintype "bidirectional"))
      (node (ref "U24") (pin "9") (pinfunction "VINR_9") (pintype "bidirectional"))
      (node (ref "U28") (pin "6") (pinfunction "-_6") (pintype "bidirectional"))
      (node (ref "U28") (pin "7") (pinfunction "OUT_7") (pintype "bidirectional"))
    )
    (net (code "145") (name "Net-(U24-VOUTL)") (class "Default")
      (node (ref "U24") (pin "14") (pinfunction "VOUTL_14") (pintype "bidirectional"))
      (node (ref "U25") (pin "3") (pinfunction "+_3") (pintype "bidirectional"))
    )
    (net (code "146") (name "Net-(U24-VOUTR)") (class "Default")
      (node (ref "U24") (pin "11") (pinfunction "VOUTR_11") (pintype "bidirectional"))
      (node (ref "U26") (pin "3") (pinfunction "+_3") (pintype "bidirectional"))
    )
    (net (code "147") (name "Net-(U25A--)") (class "Default")
      (node (ref "C132") (pin "1") (pinfunction "1_1") (pintype "bidirectional"))
      (node (ref "R78") (pin "1") (pinfunction "1_1") (pintype "bidirectional"))
      (node (ref "U25") (pin "1") (pinfunction "OUT_1") (pintype "bidirectional"))
      (node (ref "U25") (pin "2") (pinfunction "-_2") (pintype "bidirectional"))
    )
    (net (code "148") (name "Net-(U25B--)") (class "Default")
      (node (ref "R78") (pin "2") (pinfunction "2_2") (pintype "bidirectional"))
      (node (ref "R79") (pin "1") (pinfunction "1_1") (pintype "bidirectional"))
      (node (ref "U25") (pin "6") (pinfunction "-_6") (pintype "bidirectional"))
    )
    (net (code "149") (name "Net-(U25B-OUT)") (class "Default")
      (node (ref "C133") (pin "1") (pinfunction "1_1") (pintype "bidirectional"))
      (node (ref "R79") (pin "2") (pinfunction "2_2") (pintype "bidirectional"))
      (node (ref "U25") (pin "7") (pinfunction "OUT_7") (pintype "bidirectional"))
    )
    (net (code "150") (name "Net-(U26A--)") (class "Default")
      (node (ref "C134") (pin "1") (pinfunction "1_1") (pintype "bidirectional"))
      (node (ref "R80") (pin "1") (pinfunction "1_1") (pintype "bidirectional"))
      (node (ref "U26") (pin "1") (pinfunction "OUT_1") (pintype "bidirectional"))
      (node (ref "U26") (pin "2") (pinfunction "-_2") (pintype "bidirectional"))
    )
    (net (code "151") (name "Net-(U26B--)") (class "Default")
      (node (ref "R80") (pin "2") (pinfunction "2_2") (pintype "bidirectional"))
      (node (ref "R81") (pin "1") (pinfunction "1_1") (pintype "bidirectional"))
      (node (ref "U26") (pin "6") (pinfunction "-_6") (pintype "bidirectional"))
    )
    (net (code "152") (name "Net-(U26B-OUT)") (class "Default")
      (node (ref "C135") (pin "1") (pinfunction "1_1") (pintype "bidirectional"))
      (node (ref "R81") (pin "2") (pinfunction "2_2") (pintype "bidirectional"))
      (node (ref "U26") (pin "7") (pinfunction "OUT_7") (pintype "bidirectional"))
    )
    (net (code "153") (name "Net-(U27-VCC)") (class "Default")
      (node (ref "C121") (pin "2") (pinfunction "2_2") (pintype "bidirectional"))
      (node (ref "C122") (pin "2") (pinfunction "2_2") (pintype "bidirectional"))
      (node (ref "C129") (pin "2") (pinfunction "2_2") (pintype "bidirectional"))
      (node (ref "FB13") (pin "1") (pinfunction "1_1") (pintype "bidirectional"))
      (node (ref "U27") (pin "6") (pinfunction "VCC_6") (pintype "bidirectional"))
    )
    (net (code "154") (name "Net-(U27-VCOM)") (class "Default")
      (node (ref "C123") (pin "2") (pinfunction "2_2") (pintype "bidirectional"))
      (node (ref "C124") (pin "2") (pinfunction "2_2") (pintype "bidirectional"))
      (node (ref "U27") (pin "10") (pinfunction "VCOM_10") (pintype "bidirectional"))
    )
    (net (code "155") (name "Net-(U27-VOUT_L)") (class "Default")
      (node (ref "C136") (pin "1") (pinfunction "1_1") (pintype "bidirectional"))
      (node (ref "U27") (pin "7") (pinfunction "VOUT_L_7") (pintype "bidirectional"))
    )
    (net (code "156") (name "Net-(U27-VOUT_R)") (class "Default")
      (node (ref "C137") (pin "1") (pinfunction "1_1") (pintype "bidirectional"))
      (node (ref "U27") (pin "8") (pinfunction "VOUT_R_8") (pintype "bidirectional"))
    )
    (net (code "157") (name "Net-(U28A-+)") (class "Default")
      (node (ref "C125") (pin "1") (pinfunction "1_1") (pintype "bidirectional"))
      (node (ref "R67") (pin "2") (pinfunction "2_2") (pintype "bidirectional"))
      (node (ref "U28") (pin "3") (pinfunction "+_3") (pintype "bidirectional"))
    )
    (net (code "158") (name "Net-(U28B-+)") (class "Default")
      (node (ref "C127") (pin "1") (pinfunction "1_1") (pintype "bidirectional"))
      (node (ref "R69") (pin "2") (pinfunction "2_2") (pintype "bidirectional"))
      (node (ref "U28") (pin "5") (pinfunction "+_5") (pintype "bidirectional"))
    )
    (net (code "159") (name "PGA0_~{CS}") (class "Default")
      (node (ref "U6") (pin "2") (pinfunction "~{CS}_2") (pintype "bidirectional"))
      (node (ref "U9") (pin "42") (pinfunction "IO18_42") (pintype "bidirectional"))
    )
    (net (code "160") (name "PGA1_~{CS}") (class "Default")
      (node (ref "U18") (pin "2") (pinfunction "~{CS}_2") (pintype "bidirectional"))
      (node (ref "U9") (pin "52") (pinfunction "IO25_52") (pintype "bidirectional"))
    )
    (net (code "161") (name "PGA2_~{CS}") (class "Default")
      (node (ref "U24") (pin "2") (pinfunction "~{CS}_2") (pintype "bidirectional"))
      (node (ref "U9") (pin "68") (pinfunction "IO36_68") (pintype "bidirectional"))
    )
    (net (code "162") (name "PGA_SCLK") (class "Default")
      (node (ref "U18") (pin "6") (pinfunction "SCLK_6") (pintype "bidirectional"))
      (node (ref "U24") (pin "6") (pinfunction "SCLK_6") (pintype "bidirectional"))
      (node (ref "U6") (pin "6") (pinfunction "SCLK_6") (pintype "bidirectional"))
      (node (ref "U9") (pin "39") (pinfunction "IO17_39") (pintype "bidirectional"))
    )
    (net (code "163") (name "PGA_SDI") (class "Default")
      (node (ref "U18") (pin "3") (pinfunction "SDI_3") (pintype "bidirectional"))
      (node (ref "U24") (pin "3") (pinfunction "SDI_3") (pintype "bidirectional"))
      (node (ref "U6") (pin "3") (pinfunction "SDI_3") (pintype "bidirectional"))
      (node (ref "U9") (pin "43") (pinfunction "IO19_43") (pintype "bidirectional"))
    )
    (net (code "164") (name "PGA_~{MUTE}") (class "Default")
      (node (ref "U18") (pin "8") (pinfunction "~{MUTE}_8") (pintype "bidirectional"))
      (node (ref "U24") (pin "8") (pinfunction "~{MUTE}_8") (pintype "bidirectional"))
      (node (ref "U6") (pin "8") (pinfunction "~{MUTE}_8") (pintype "bidirectional"))
      (node (ref "U9") (pin "38") (pinfunction "IO16_38") (pintype "bidirectional"))
    )
    (net (code "165") (name "RL_MAINS_ON") (class "Default")
      (node (ref "CN12") (pin "2") (pinfunction "2_2") (pintype "bidirectional"))
      (node (ref "U9") (pin "28") (pinfunction "IO10_28") (pintype "bidirectional"))
    )
    (net (code "166") (name "STM_NRST") (class "Default")
      (node (ref "CN11") (pin "3") (pinfunction "3_3") (pintype "bidirectional"))
      (node (ref "R84") (pin "2") (pinfunction "2_2") (pintype "bidirectional"))
      (node (ref "U29") (pin "4") (pinfunction "NRST_4") (pintype "bidirectional"))
    )
    (net (code "167") (name "STM_SPI_MISO") (class "Default")
      (node (ref "U29") (pin "12") (pinfunction "PA6_12") (pintype "bidirectional"))
      (node (ref "U30") (pin "2") (pinfunction "SO/IO1_2") (pintype "bidirectional"))
    )
    (net (code "168") (name "STM_SPI_MOSI") (class "Default")
      (node (ref "U29") (pin "13") (pinfunction "PA7_13") (pintype "bidirectional"))
      (node (ref "U30") (pin "5") (pinfunction "SI/IO0_5") (pintype "bidirectional"))
      (node (ref "U9") (pin "84") (pinfunction "IO48_84") (pintype "bidirectional"))
    )
    (net (code "169") (name "STM_SPI_SCLK") (class "Default")
      (node (ref "U29") (pin "11") (pinfunction "PA5_11") (pintype "bidirectional"))
      (node (ref "U30") (pin "6") (pinfunction "SCK_6") (pintype "bidirectional"))
      (node (ref "U9") (pin "83") (pinfunction "IO47_83") (pintype "bidirectional"))
    )
    (net (code "170") (name "STM_SWCLK") (class "Default")
      (node (ref "CN11") (pin "4") (pinfunction "4_4") (pintype "bidirectional"))
      (node (ref "U29") (pin "20") (pinfunction "PA14_20") (pintype "bidirectional"))
    )
    (net (code "171") (name "STM_SWDIO") (class "Default")
      (node (ref "CN11") (pin "5") (pinfunction "5_5") (pintype "bidirectional"))
      (node (ref "U29") (pin "19") (pinfunction "PA13_19") (pintype "bidirectional"))
    )
    (net (code "172") (name "STM_UART_RX") (class "Default")
      (node (ref "U16") (pin "1") (pinfunction "TXD_1") (pintype "bidirectional"))
      (node (ref "U29") (pin "9") (pinfunction "PA3_9") (pintype "bidirectional"))
    )
    (net (code "173") (name "STM_UART_TX") (class "Default")
      (node (ref "U16") (pin "4") (pinfunction "RXD_4") (pintype "bidirectional"))
      (node (ref "U29") (pin "8") (pinfunction "PA2_8") (pintype "bidirectional"))
    )
    (net (code "174") (name "TCLK") (class "Default")
      (node (ref "CN3") (pin "1") (pinfunction "1_1") (pintype "bidirectional"))
      (node (ref "R45") (pin "2") (pinfunction "2_2") (pintype "bidirectional"))
      (node (ref "U9") (pin "16") (pinfunction "TCLK_16") (pintype "bidirectional"))
    )
    (net (code "175") (name "TDI") (class "Default")
      (node (ref "CN3") (pin "5") (pinfunction "5_5") (pintype "bidirectional"))
      (node (ref "R43") (pin "1") (pinfunction "1_1") (pintype "bidirectional"))
      (node (ref "U9") (pin "15") (pinfunction "TDI_15") (pintype "bidirectional"))
    )
    (net (code "176") (name "TDO") (class "Default")
      (node (ref "CN3") (pin "2") (pinfunction "2_2") (pintype "bidirectional"))
      (node (ref "U9") (pin "20") (pinfunction "TDO_20") (pintype "bidirectional"))
    )
    (net (code "177") (name "TMS") (class "Default")
      (node (ref "CN3") (pin "3") (pinfunction "3_3") (pintype "bidirectional"))
      (node (ref "R44") (pin "1") (pinfunction "1_1") (pintype "bidirectional"))
      (node (ref "U9") (pin "18") (pinfunction "TMS_18") (pintype "bidirectional"))
    )
    (net (code "178") (name "V+") (class "Default")
      (node (ref "C24") (pin "2") (pinfunction "2_2") (pintype "bidirectional"))
      (node (ref "C36") (pin "2") (pinfunction "2_2") (pintype "bidirectional"))
      (node (ref "C38") (pin "2") (pinfunction "2_2") (pintype "bidirectional"))
      (node (ref "C48") (pin "2") (pinfunction "2_2") (pintype "bidirectional"))
      (node (ref "CN12") (pin "1") (pinfunction "1_1") (pintype "bidirectional"))
      (node (ref "CN6") (pin "1") (pinfunction "1_1") (pintype "bidirectional"))
      (node (ref "CN6") (pin "2") (pinfunction "1_2") (pintype "bidirectional"))
      (node (ref "FB19") (pin "1") (pinfunction "1_1") (pintype "bidirectional"))
      (node (ref "FB2") (pin "1") (pinfunction "1_1") (pintype "bidirectional"))
      (node (ref "U4") (pin "3") (pinfunction "VIN_3") (pintype "bidirectional"))
      (node (ref "U5") (pin "3") (pinfunction "VIN_3") (pintype "bidirectional"))
    )
    (net (code "179") (name "V-") (class "Default")
      (node (ref "CN8") (pin "1") (pinfunction "1_1") (pintype "bidirectional"))
      (node (ref "CN8") (pin "2") (pinfunction "1_2") (pintype "bidirectional"))
      (node (ref "FB18") (pin "1") (pinfunction "1_1") (pintype "bidirectional"))
    )
    (net (code "180") (name "WM_CLKOUT") (class "Default")
      (node (ref "U1") (pin "9") (pinfunction "CLKOUT_9") (pintype "bidirectional"))
      (node (ref "U9") (pin "91") (pinfunction "CLK4_91") (pintype "bidirectional"))
    )
    (net (code "181") (name "WM_GPO0") (class "Default")
      (node (ref "R56") (pin "1") (pinfunction "1_1") (pintype "bidirectional"))
      (node (ref "U1") (pin "2") (pinfunction "GPO0/SFTMODE_2") (pintype "bidirectional"))
      (node (ref "U9") (pin "114") (pinfunction "IO64_114") (pintype "bidirectional"))
    )
    (net (code "182") (name "WM_I2S_BCLK") (class "Default")
      (node (ref "U1") (pin "14") (pinfunction "BCLK_14") (pintype "bidirectional"))
      (node (ref "U9") (pin "89") (pinfunction "CLK6_89") (pintype "bidirectional"))
    )
    (net (code "183") (name "WM_I2S_DATA") (class "Default")
      (node (ref "U1") (pin "12") (pinfunction "DOUT_12") (pintype "bidirectional"))
      (node (ref "U9") (pin "87") (pinfunction "IO51_87") (pintype "bidirectional"))
    )
    (net (code "184") (name "WM_I2S_LRCLK") (class "Default")
      (node (ref "U1") (pin "15") (pinfunction "LRCLK_15") (pintype "bidirectional"))
      (node (ref "U9") (pin "88") (pinfunction "CLK7_88") (pintype "bidirectional"))
    )
    (net (code "185") (name "WM_I2S_SCLK") (class "Default")
      (node (ref "U1") (pin "16") (pinfunction "MCLK_16") (pintype "bidirectional"))
      (node (ref "U9") (pin "90") (pinfunction "CLK5_90") (pintype "bidirectional"))
    )
    (net (code "186") (name "WM_RST") (class "Default")
      (node (ref "U1") (pin "6") (pinfunction "RESET_6") (pintype "bidirectional"))
      (node (ref "U9") (pin "110") (pinfunction "IO60_110") (pintype "bidirectional"))
    )
    (net (code "187") (name "WM_SPI_CSB") (class "Default")
      (node (ref "R55") (pin "1") (pinfunction "1_1") (pintype "bidirectional"))
      (node (ref "U1") (pin "5") (pinfunction "CSB/GP01_5") (pintype "bidirectional"))
      (node (ref "U9") (pin "111") (pinfunction "IO61_111") (pintype "bidirectional"))
    )
    (net (code "188") (name "WM_SPI_SCLK") (class "Default")
      (node (ref "R54") (pin "1") (pinfunction "1_1") (pintype "bidirectional"))
      (node (ref "U1") (pin "1") (pinfunction "SCLK_1") (pintype "bidirectional"))
      (node (ref "U9") (pin "100") (pinfunction "IO54_100") (pintype "bidirectional"))
    )
    (net (code "189") (name "WM_SPI_SDIN") (class "Default")
      (node (ref "R57") (pin "1") (pinfunction "1_1") (pintype "bidirectional"))
      (node (ref "U1") (pin "3") (pinfunction "SDIN/HWMODE_3") (pintype "bidirectional"))
      (node (ref "U9") (pin "113") (pinfunction "IO63_113") (pintype "bidirectional"))
    )
    (net (code "190") (name "WM_SPI_SDOUT") (class "Default")
      (node (ref "R53") (pin "1") (pinfunction "1_1") (pintype "bidirectional"))
      (node (ref "U1") (pin "4") (pinfunction "SDOUT/GPO2_4") (pintype "bidirectional"))
      (node (ref "U9") (pin "112") (pinfunction "IO62_112") (pintype "bidirectional"))
    )
    (net (code "191") (name "unconnected-(CN3-Pad4)") (class "Default")
      (node (ref "CN3") (pin "4") (pinfunction "4_4") (pintype "bidirectional"))
    )
    (net (code "192") (name "unconnected-(CN3-Pad7)") (class "Default")
      (node (ref "CN3") (pin "7") (pinfunction "7_7") (pintype "bidirectional"))
    )
    (net (code "193") (name "unconnected-(CN11-Pad2)") (class "Default")
      (node (ref "CN11") (pin "2") (pinfunction "2_2") (pintype "bidirectional"))
    )
    (net (code "194") (name "unconnected-(CN15-5V-PadVCC)") (class "Default")
      (node (ref "CN15") (pin "VCC") (pinfunction "5V_VCC") (pintype "bidirectional"))
    )
    (net (code "195") (name "unconnected-(U2-ZEROA-Pad11)") (class "Default")
      (node (ref "U2") (pin "11") (pinfunction "ZEROA_11") (pintype "bidirectional"))
    )
    (net (code "196") (name "unconnected-(U6-SDO-Pad7)") (class "Default")
      (node (ref "U6") (pin "7") (pinfunction "SDO_7") (pintype "bidirectional"))
    )
    (net (code "197") (name "unconnected-(U9B-CLK1-Pad23)") (class "Default")
      (node (ref "U9") (pin "23") (pinfunction "CLK1_23") (pintype "bidirectional"))
    )
    (net (code "198") (name "unconnected-(U9B-IO1-Pad1)") (class "Default")
      (node (ref "U9") (pin "1") (pinfunction "IO1_1") (pintype "bidirectional"))
    )
    (net (code "199") (name "unconnected-(U9B-IO2-Pad2)") (class "Default")
      (node (ref "U9") (pin "2") (pinfunction "IO2_2") (pintype "bidirectional"))
    )
    (net (code "200") (name "unconnected-(U9B-IO3-Pad3)") (class "Default")
      (node (ref "U9") (pin "3") (pinfunction "IO3_3") (pintype "bidirectional"))
    )
    (net (code "201") (name "unconnected-(U9B-IO5-Pad7)") (class "Default")
      (node (ref "U9") (pin "7") (pinfunction "IO5_7") (pintype "bidirectional"))
    )
    (net (code "202") (name "unconnected-(U9B-IO7-Pad10)") (class "Default")
      (node (ref "U9") (pin "10") (pinfunction "IO7_10") (pintype "bidirectional"))
    )
    (net (code "203") (name "unconnected-(U9B-IO8-Pad11)") (class "Default")
      (node (ref "U9") (pin "11") (pinfunction "IO8_11") (pintype "bidirectional"))
    )
    (net (code "204") (name "unconnected-(U9C-IO11-Pad30)") (class "Default")
      (node (ref "U9") (pin "30") (pinfunction "IO11_30") (pintype "bidirectional"))
    )
    (net (code "205") (name "unconnected-(U9C-IO12-Pad31)") (class "Default")
      (node (ref "U9") (pin "31") (pinfunction "IO12_31") (pintype "bidirectional"))
    )
    (net (code "206") (name "unconnected-(U9C-IO13-Pad32)") (class "Default")
      (node (ref "U9") (pin "32") (pinfunction "IO13_32") (pintype "bidirectional"))
    )
    (net (code "207") (name "unconnected-(U9C-IO14-Pad33)") (class "Default")
      (node (ref "U9") (pin "33") (pinfunction "IO14_33") (pintype "bidirectional"))
    )
    (net (code "208") (name "unconnected-(U9C-IO15-Pad34)") (class "Default")
      (node (ref "U9") (pin "34") (pinfunction "IO15_34") (pintype "bidirectional"))
    )
    (net (code "209") (name "unconnected-(U9E-IO30-Pad59)") (class "Default")
      (node (ref "U9") (pin "59") (pinfunction "IO30_59") (pintype "bidirectional"))
    )
    (net (code "210") (name "unconnected-(U9E-IO31-Pad60)") (class "Default")
      (node (ref "U9") (pin "60") (pinfunction "IO31_60") (pintype "bidirectional"))
    )
    (net (code "211") (name "unconnected-(U9E-IO32-Pad64)") (class "Default")
      (node (ref "U9") (pin "64") (pinfunction "IO32_64") (pintype "bidirectional"))
    )
    (net (code "212") (name "unconnected-(U9E-IO33-Pad65)") (class "Default")
      (node (ref "U9") (pin "65") (pinfunction "IO33_65") (pintype "bidirectional"))
    )
    (net (code "213") (name "unconnected-(U9E-IO34-Pad66)") (class "Default")
      (node (ref "U9") (pin "66") (pinfunction "IO34_66") (pintype "bidirectional"))
    )
    (net (code "214") (name "unconnected-(U9E-IO35-Pad67)") (class "Default")
      (node (ref "U9") (pin "67") (pinfunction "IO35_67") (pintype "bidirectional"))
    )
    (net (code "215") (name "unconnected-(U9G-IO53-Pad99)") (class "Default")
      (node (ref "U9") (pin "99") (pinfunction "IO53_99") (pintype "bidirectional"))
    )
    (net (code "216") (name "unconnected-(U9G-IO55-Pad101)") (class "Default")
      (node (ref "U9") (pin "101") (pinfunction "IO55_101") (pintype "bidirectional"))
    )
    (net (code "217") (name "unconnected-(U9G-IO56-Pad103)") (class "Default")
      (node (ref "U9") (pin "103") (pinfunction "IO56_103") (pintype "bidirectional"))
    )
    (net (code "218") (name "unconnected-(U9G-IO57-Pad104)") (class "Default")
      (node (ref "U9") (pin "104") (pinfunction "IO57_104") (pintype "bidirectional"))
    )
    (net (code "219") (name "unconnected-(U9G-IO58-Pad105)") (class "Default")
      (node (ref "U9") (pin "105") (pinfunction "IO58_105") (pintype "bidirectional"))
    )
    (net (code "220") (name "unconnected-(U9G-IO59-Pad106)") (class "Default")
      (node (ref "U9") (pin "106") (pinfunction "IO59_106") (pintype "bidirectional"))
    )
    (net (code "221") (name "unconnected-(U9H-IO65-Pad115)") (class "Default")
      (node (ref "U9") (pin "115") (pinfunction "IO65_115") (pintype "bidirectional"))
    )
    (net (code "222") (name "unconnected-(U9H-IO66-Pad119)") (class "Default")
      (node (ref "U9") (pin "119") (pinfunction "IO66_119") (pintype "bidirectional"))
    )
    (net (code "223") (name "unconnected-(U9H-IO67-Pad120)") (class "Default")
      (node (ref "U9") (pin "120") (pinfunction "IO67_120") (pintype "bidirectional"))
    )
    (net (code "224") (name "unconnected-(U9H-IO68-Pad121)") (class "Default")
      (node (ref "U9") (pin "121") (pinfunction "IO68_121") (pintype "bidirectional"))
    )
    (net (code "225") (name "unconnected-(U9H-IO69-Pad124)") (class "Default")
      (node (ref "U9") (pin "124") (pinfunction "IO69_124") (pintype "bidirectional"))
    )
    (net (code "226") (name "unconnected-(U9H-IO70-Pad125)") (class "Default")
      (node (ref "U9") (pin "125") (pinfunction "IO70_125") (pintype "bidirectional"))
    )
    (net (code "227") (name "unconnected-(U9H-IO71-Pad126)") (class "Default")
      (node (ref "U9") (pin "126") (pinfunction "IO71_126") (pintype "bidirectional"))
    )
    (net (code "228") (name "unconnected-(U9H-IO72-Pad127)") (class "Default")
      (node (ref "U9") (pin "127") (pinfunction "IO72_127") (pintype "bidirectional"))
    )
    (net (code "229") (name "unconnected-(U9I-IO73-Pad128)") (class "Default")
      (node (ref "U9") (pin "128") (pinfunction "IO73_128") (pintype "bidirectional"))
    )
    (net (code "230") (name "unconnected-(U9I-IO74-Pad129)") (class "Default")
      (node (ref "U9") (pin "129") (pinfunction "IO74_129") (pintype "bidirectional"))
    )
    (net (code "231") (name "unconnected-(U9I-IO75-Pad132)") (class "Default")
      (node (ref "U9") (pin "132") (pinfunction "IO75_132") (pintype "bidirectional"))
    )
    (net (code "232") (name "unconnected-(U9I-IO76-Pad133)") (class "Default")
      (node (ref "U9") (pin "133") (pinfunction "IO76_133") (pintype "bidirectional"))
    )
    (net (code "233") (name "unconnected-(U9I-IO77-Pad135)") (class "Default")
      (node (ref "U9") (pin "135") (pinfunction "IO77_135") (pintype "bidirectional"))
    )
    (net (code "234") (name "unconnected-(U9I-IO78-Pad136)") (class "Default")
      (node (ref "U9") (pin "136") (pinfunction "IO78_136") (pintype "bidirectional"))
    )
    (net (code "235") (name "unconnected-(U9I-IO79-Pad137)") (class "Default")
      (node (ref "U9") (pin "137") (pinfunction "IO79_137") (pintype "bidirectional"))
    )
    (net (code "236") (name "unconnected-(U9I-IO80-Pad138)") (class "Default")
      (node (ref "U9") (pin "138") (pinfunction "IO80_138") (pintype "bidirectional"))
    )
    (net (code "237") (name "unconnected-(U9I-IO81-Pad141)") (class "Default")
      (node (ref "U9") (pin "141") (pinfunction "IO81_141") (pintype "bidirectional"))
    )
    (net (code "238") (name "unconnected-(U9I-IO82-Pad142)") (class "Default")
      (node (ref "U9") (pin "142") (pinfunction "IO82_142") (pintype "bidirectional"))
    )
    (net (code "239") (name "unconnected-(U9I-IO83-Pad143)") (class "Default")
      (node (ref "U9") (pin "143") (pinfunction "IO83_143") (pintype "bidirectional"))
    )
    (net (code "240") (name "unconnected-(U9I-IO84-Pad144)") (class "Default")
      (node (ref "U9") (pin "144") (pinfunction "IO84_144") (pintype "bidirectional"))
    )
    (net (code "241") (name "unconnected-(U15-VBUS-Pad5)") (class "Default")
      (node (ref "U15") (pin "5") (pinfunction "VBUS_5") (pintype "bidirectional"))
    )
    (net (code "242") (name "unconnected-(U16-CBUS0-Pad15)") (class "Default")
      (node (ref "U16") (pin "15") (pinfunction "CBUS0_15") (pintype "bidirectional"))
    )
    (net (code "243") (name "unconnected-(U16-CBUS1-Pad14)") (class "Default")
      (node (ref "U16") (pin "14") (pinfunction "CBUS1_14") (pintype "bidirectional"))
    )
    (net (code "244") (name "unconnected-(U16-CBUS2-Pad7)") (class "Default")
      (node (ref "U16") (pin "7") (pinfunction "CBUS2_7") (pintype "bidirectional"))
    )
    (net (code "245") (name "unconnected-(U16-CBUS3-Pad16)") (class "Default")
      (node (ref "U16") (pin "16") (pinfunction "CBUS3_16") (pintype "bidirectional"))
    )
    (net (code "246") (name "unconnected-(U16-~{RTS}-Pad2)") (class "Default")
      (node (ref "U16") (pin "2") (pinfunction "~{RTS}_2") (pintype "bidirectional"))
    )
    (net (code "247") (name "unconnected-(U18-SDO-Pad7)") (class "Default")
      (node (ref "U18") (pin "7") (pinfunction "SDO_7") (pintype "bidirectional"))
    )
    (net (code "248") (name "unconnected-(U22-ZEROA-Pad11)") (class "Default")
      (node (ref "U22") (pin "11") (pinfunction "ZEROA_11") (pintype "bidirectional"))
    )
    (net (code "249") (name "unconnected-(U24-SDO-Pad7)") (class "Default")
      (node (ref "U24") (pin "7") (pinfunction "SDO_7") (pintype "bidirectional"))
    )
    (net (code "250") (name "unconnected-(U27-ZEROA-Pad11)") (class "Default")
      (node (ref "U27") (pin "11") (pinfunction "ZEROA_11") (pintype "bidirectional"))
    )
    (net (code "251") (name "unconnected-(U29-BOOT0-Pad1)") (class "Default")
      (node (ref "U29") (pin "1") (pinfunction "BOOT0_1") (pintype "bidirectional"))
    )
    (net (code "252") (name "unconnected-(U29-PA0-Pad6)") (class "Default")
      (node (ref "U29") (pin "6") (pinfunction "PA0_6") (pintype "bidirectional"))
    )
    (net (code "253") (name "unconnected-(U29-PA1-Pad7)") (class "Default")
      (node (ref "U29") (pin "7") (pinfunction "PA1_7") (pintype "bidirectional"))
    )
    (net (code "254") (name "unconnected-(U29-PA4-Pad10)") (class "Default")
      (node (ref "U29") (pin "10") (pinfunction "PA4_10") (pintype "bidirectional"))
    )
    (net (code "255") (name "unconnected-(U29-PF0-Pad2)") (class "Default")
      (node (ref "U29") (pin "2") (pinfunction "PF0_2") (pintype "bidirectional"))
    )
    (net (code "256") (name "unconnected-(U29-PF1-Pad3)") (class "Default")
      (node (ref "U29") (pin "3") (pinfunction "PF1_3") (pintype "bidirectional"))
    )
  )
)
